# SCH_ReA4091_Rev3_20220620.net
KiCad netlist of a schematic drawn in EasyEDA
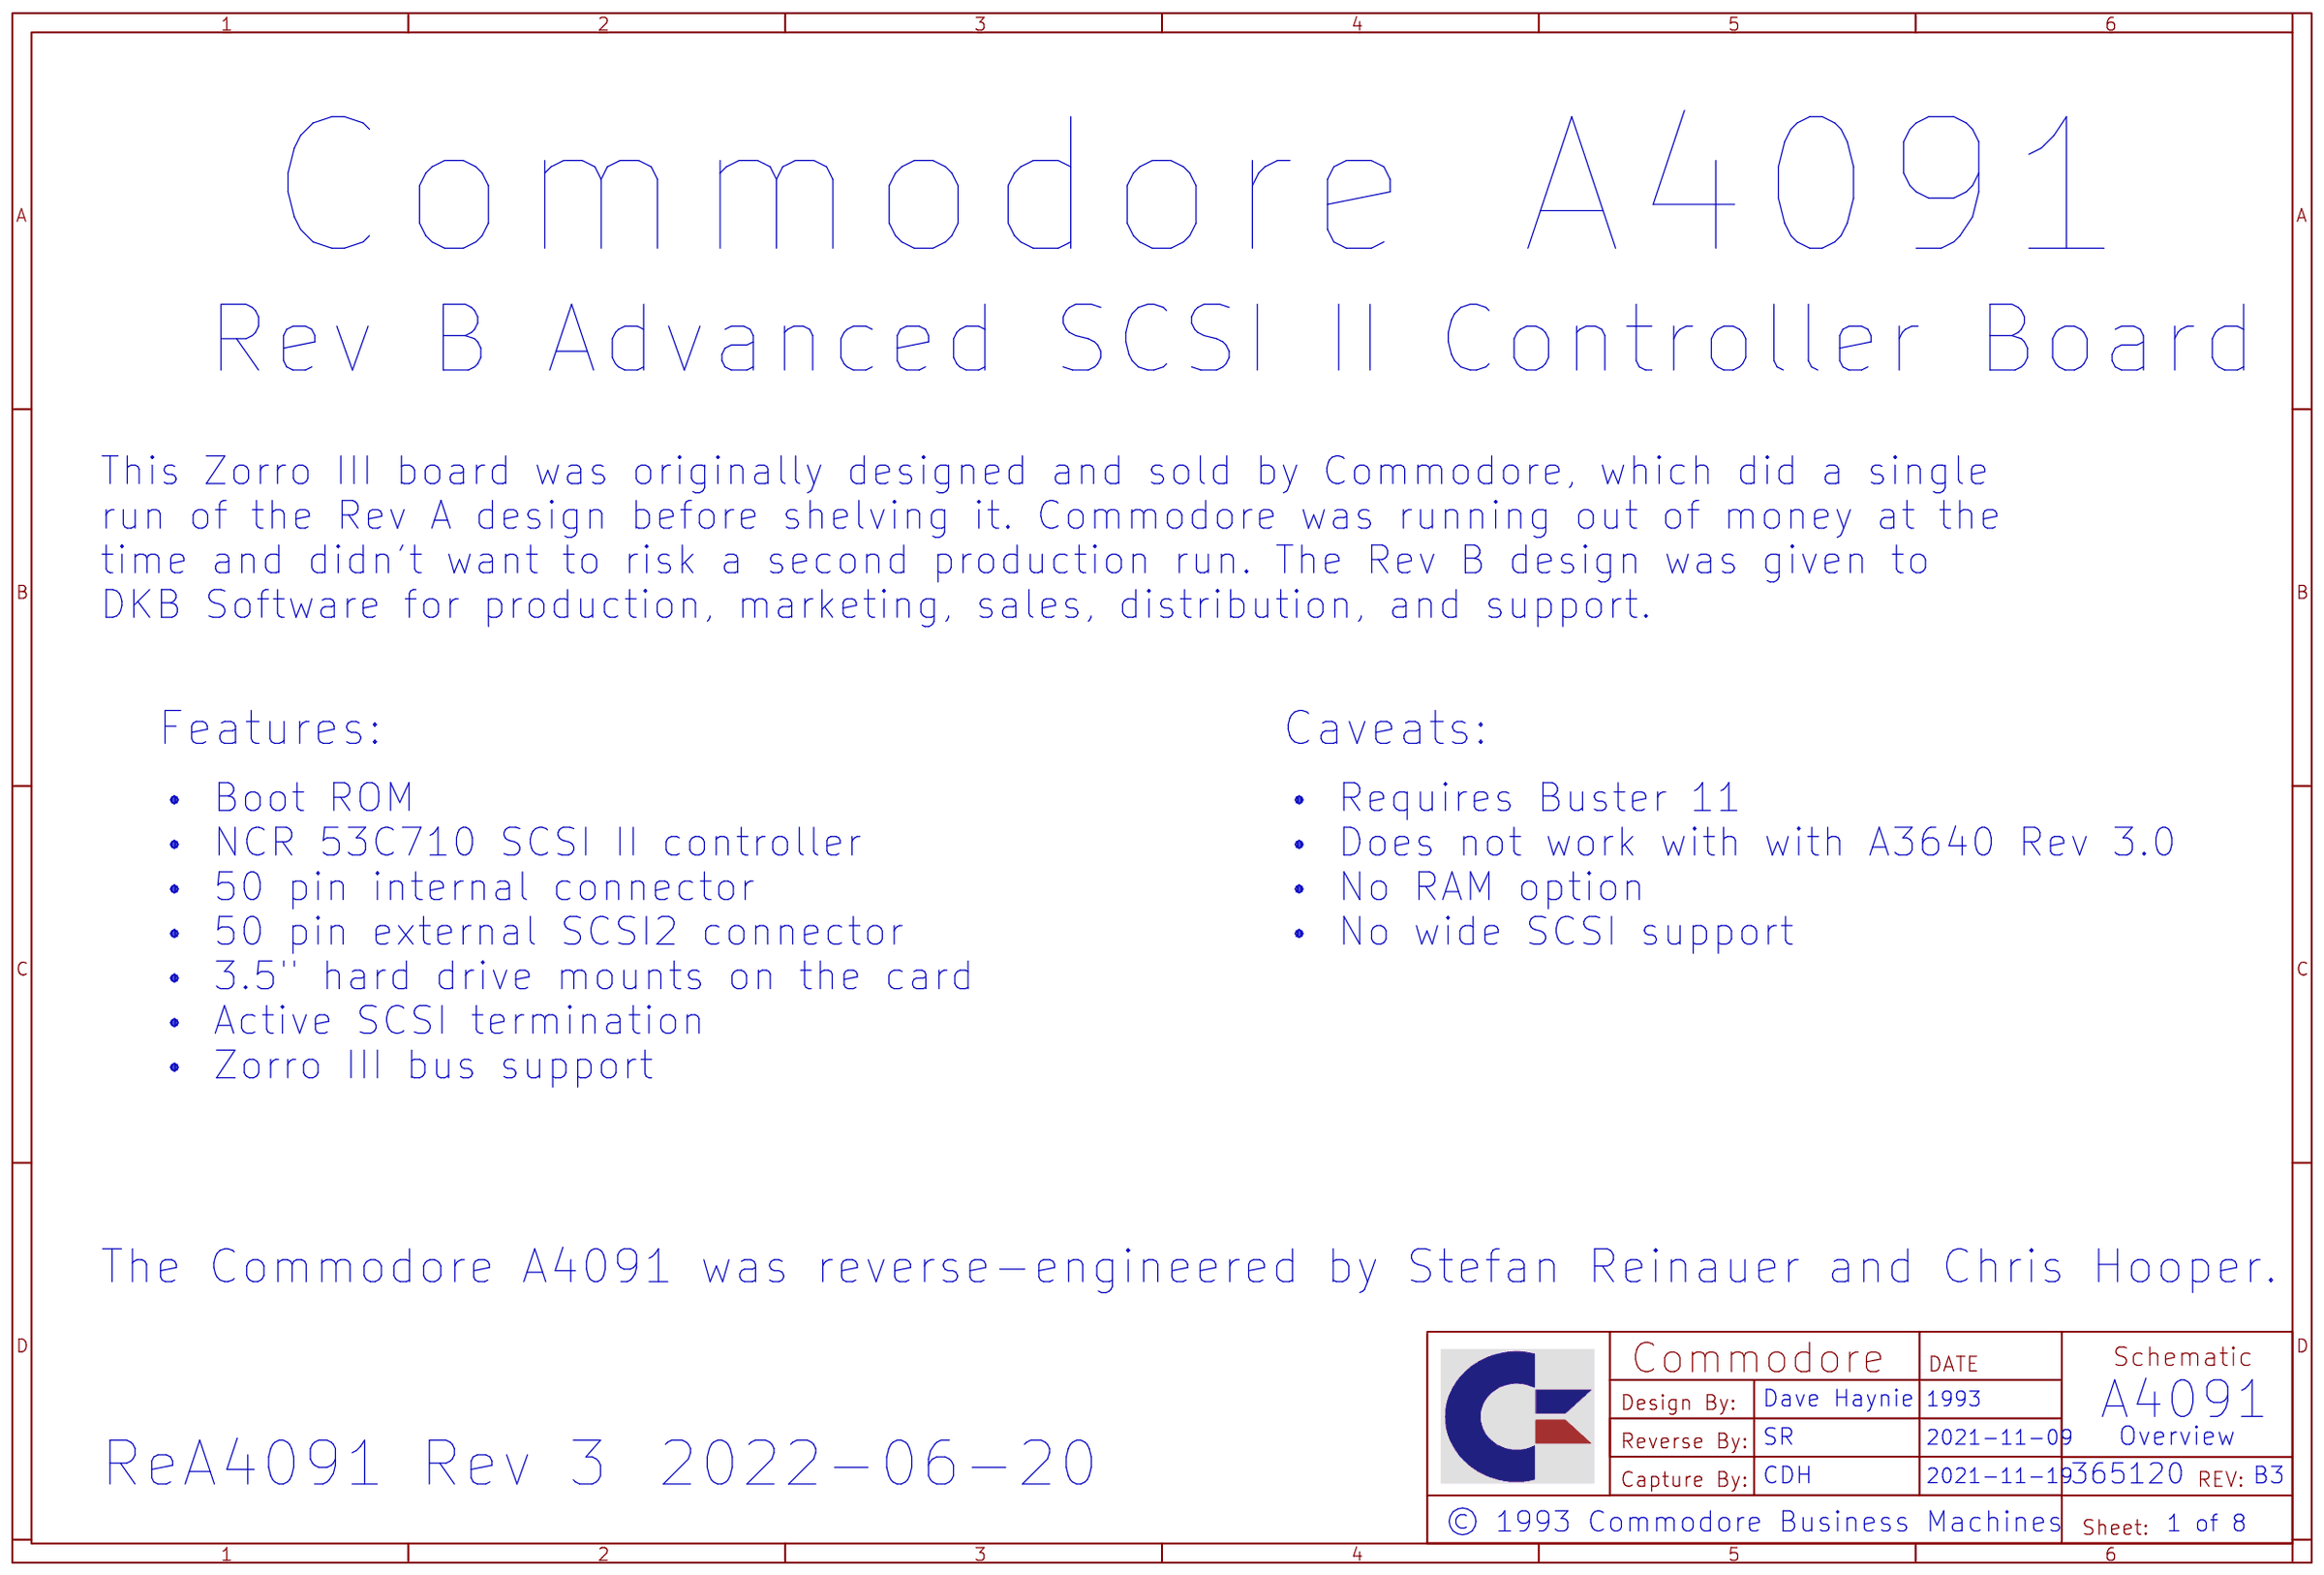
[diagram p0: Overview]
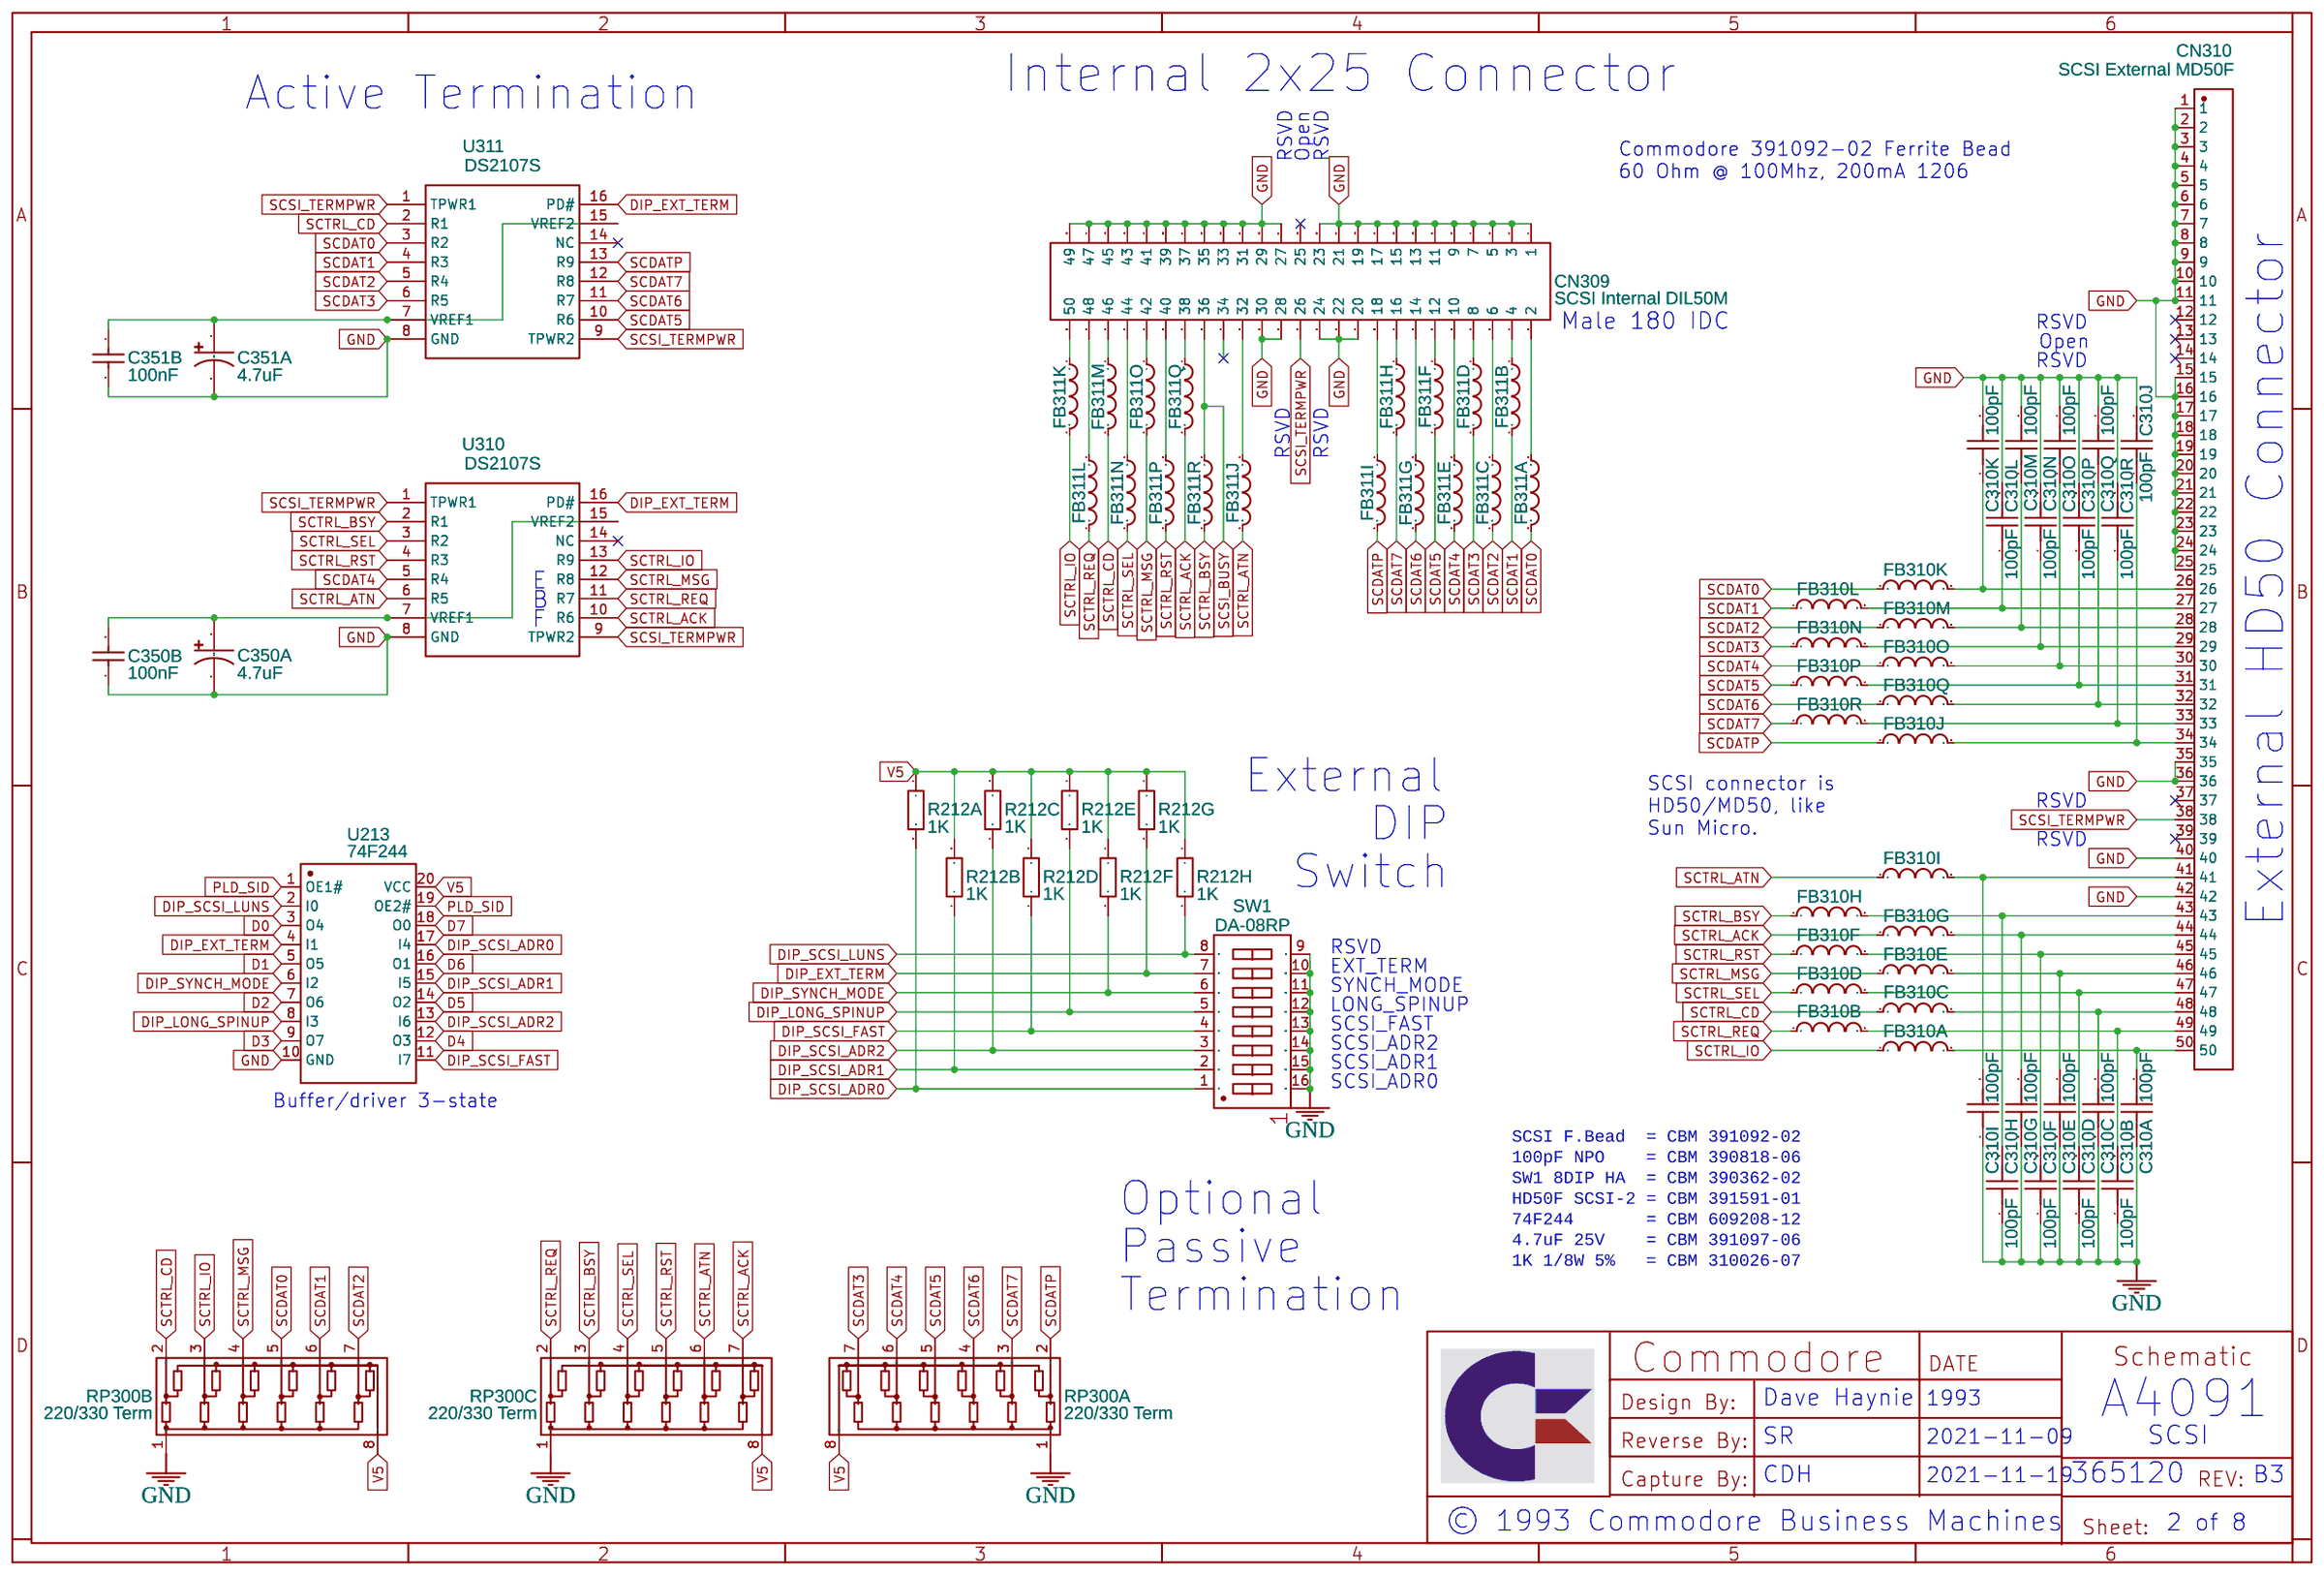
[diagram p1: SCSI]
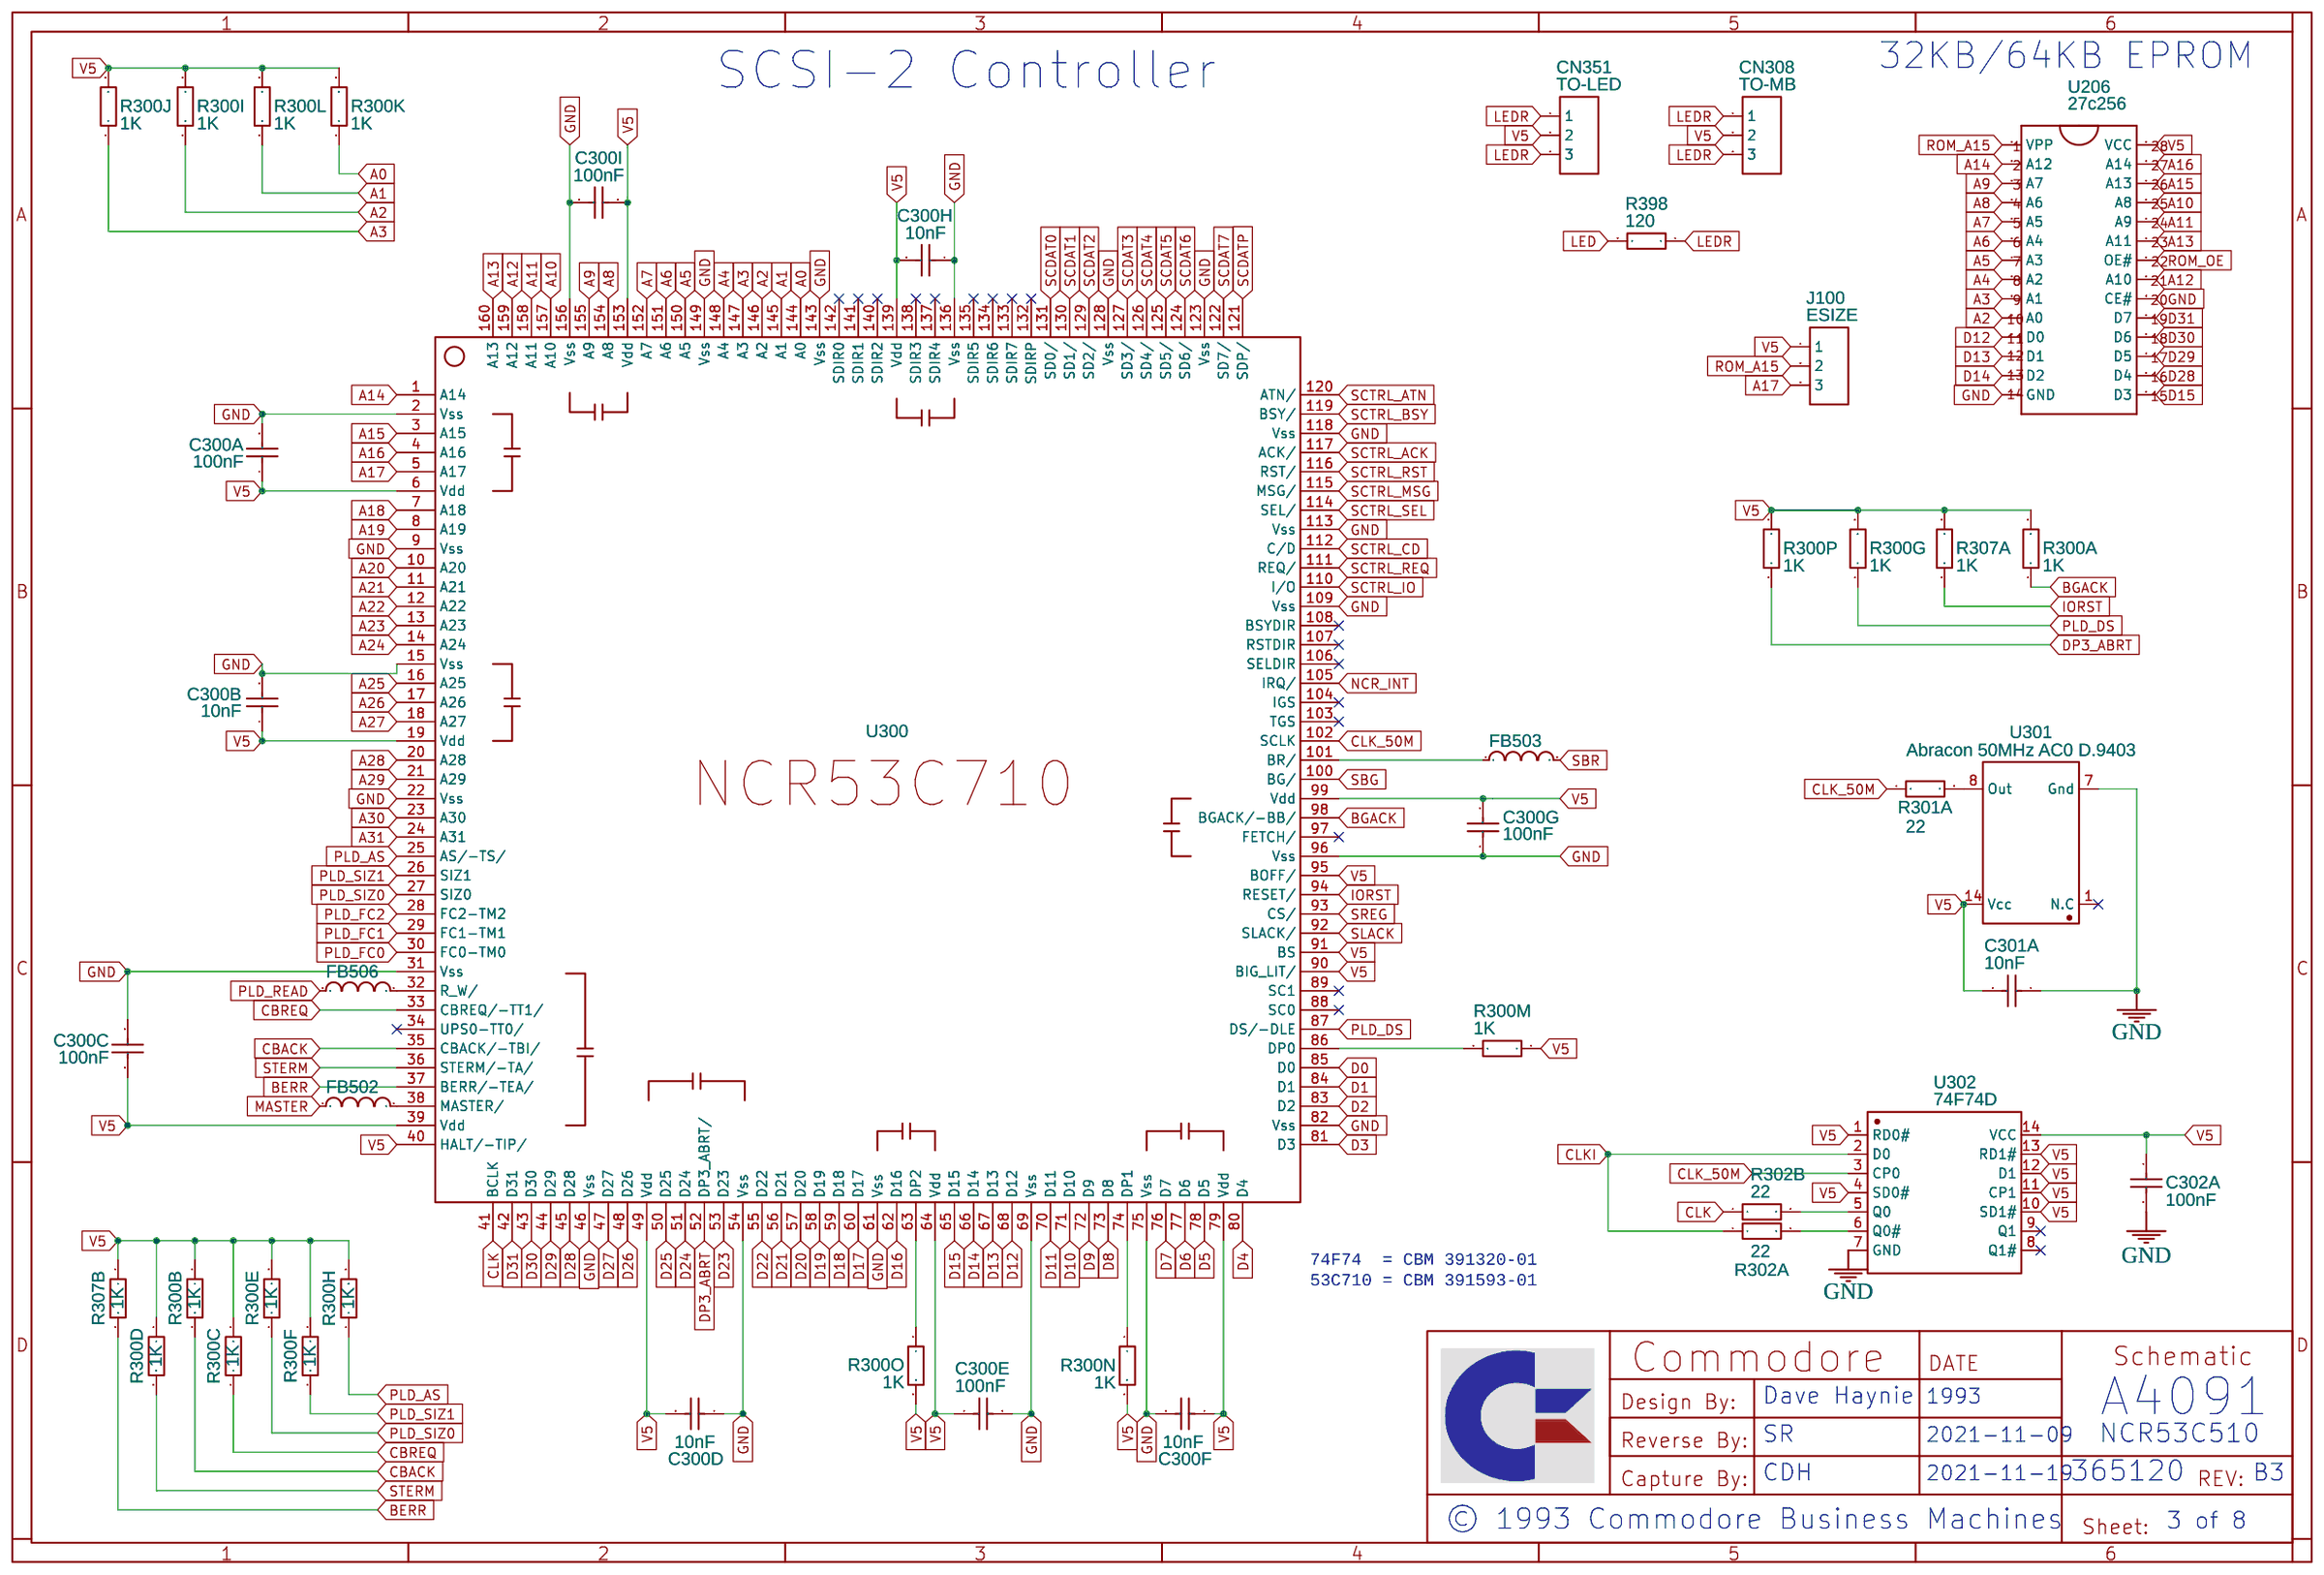
[diagram p2: NCR53C710]
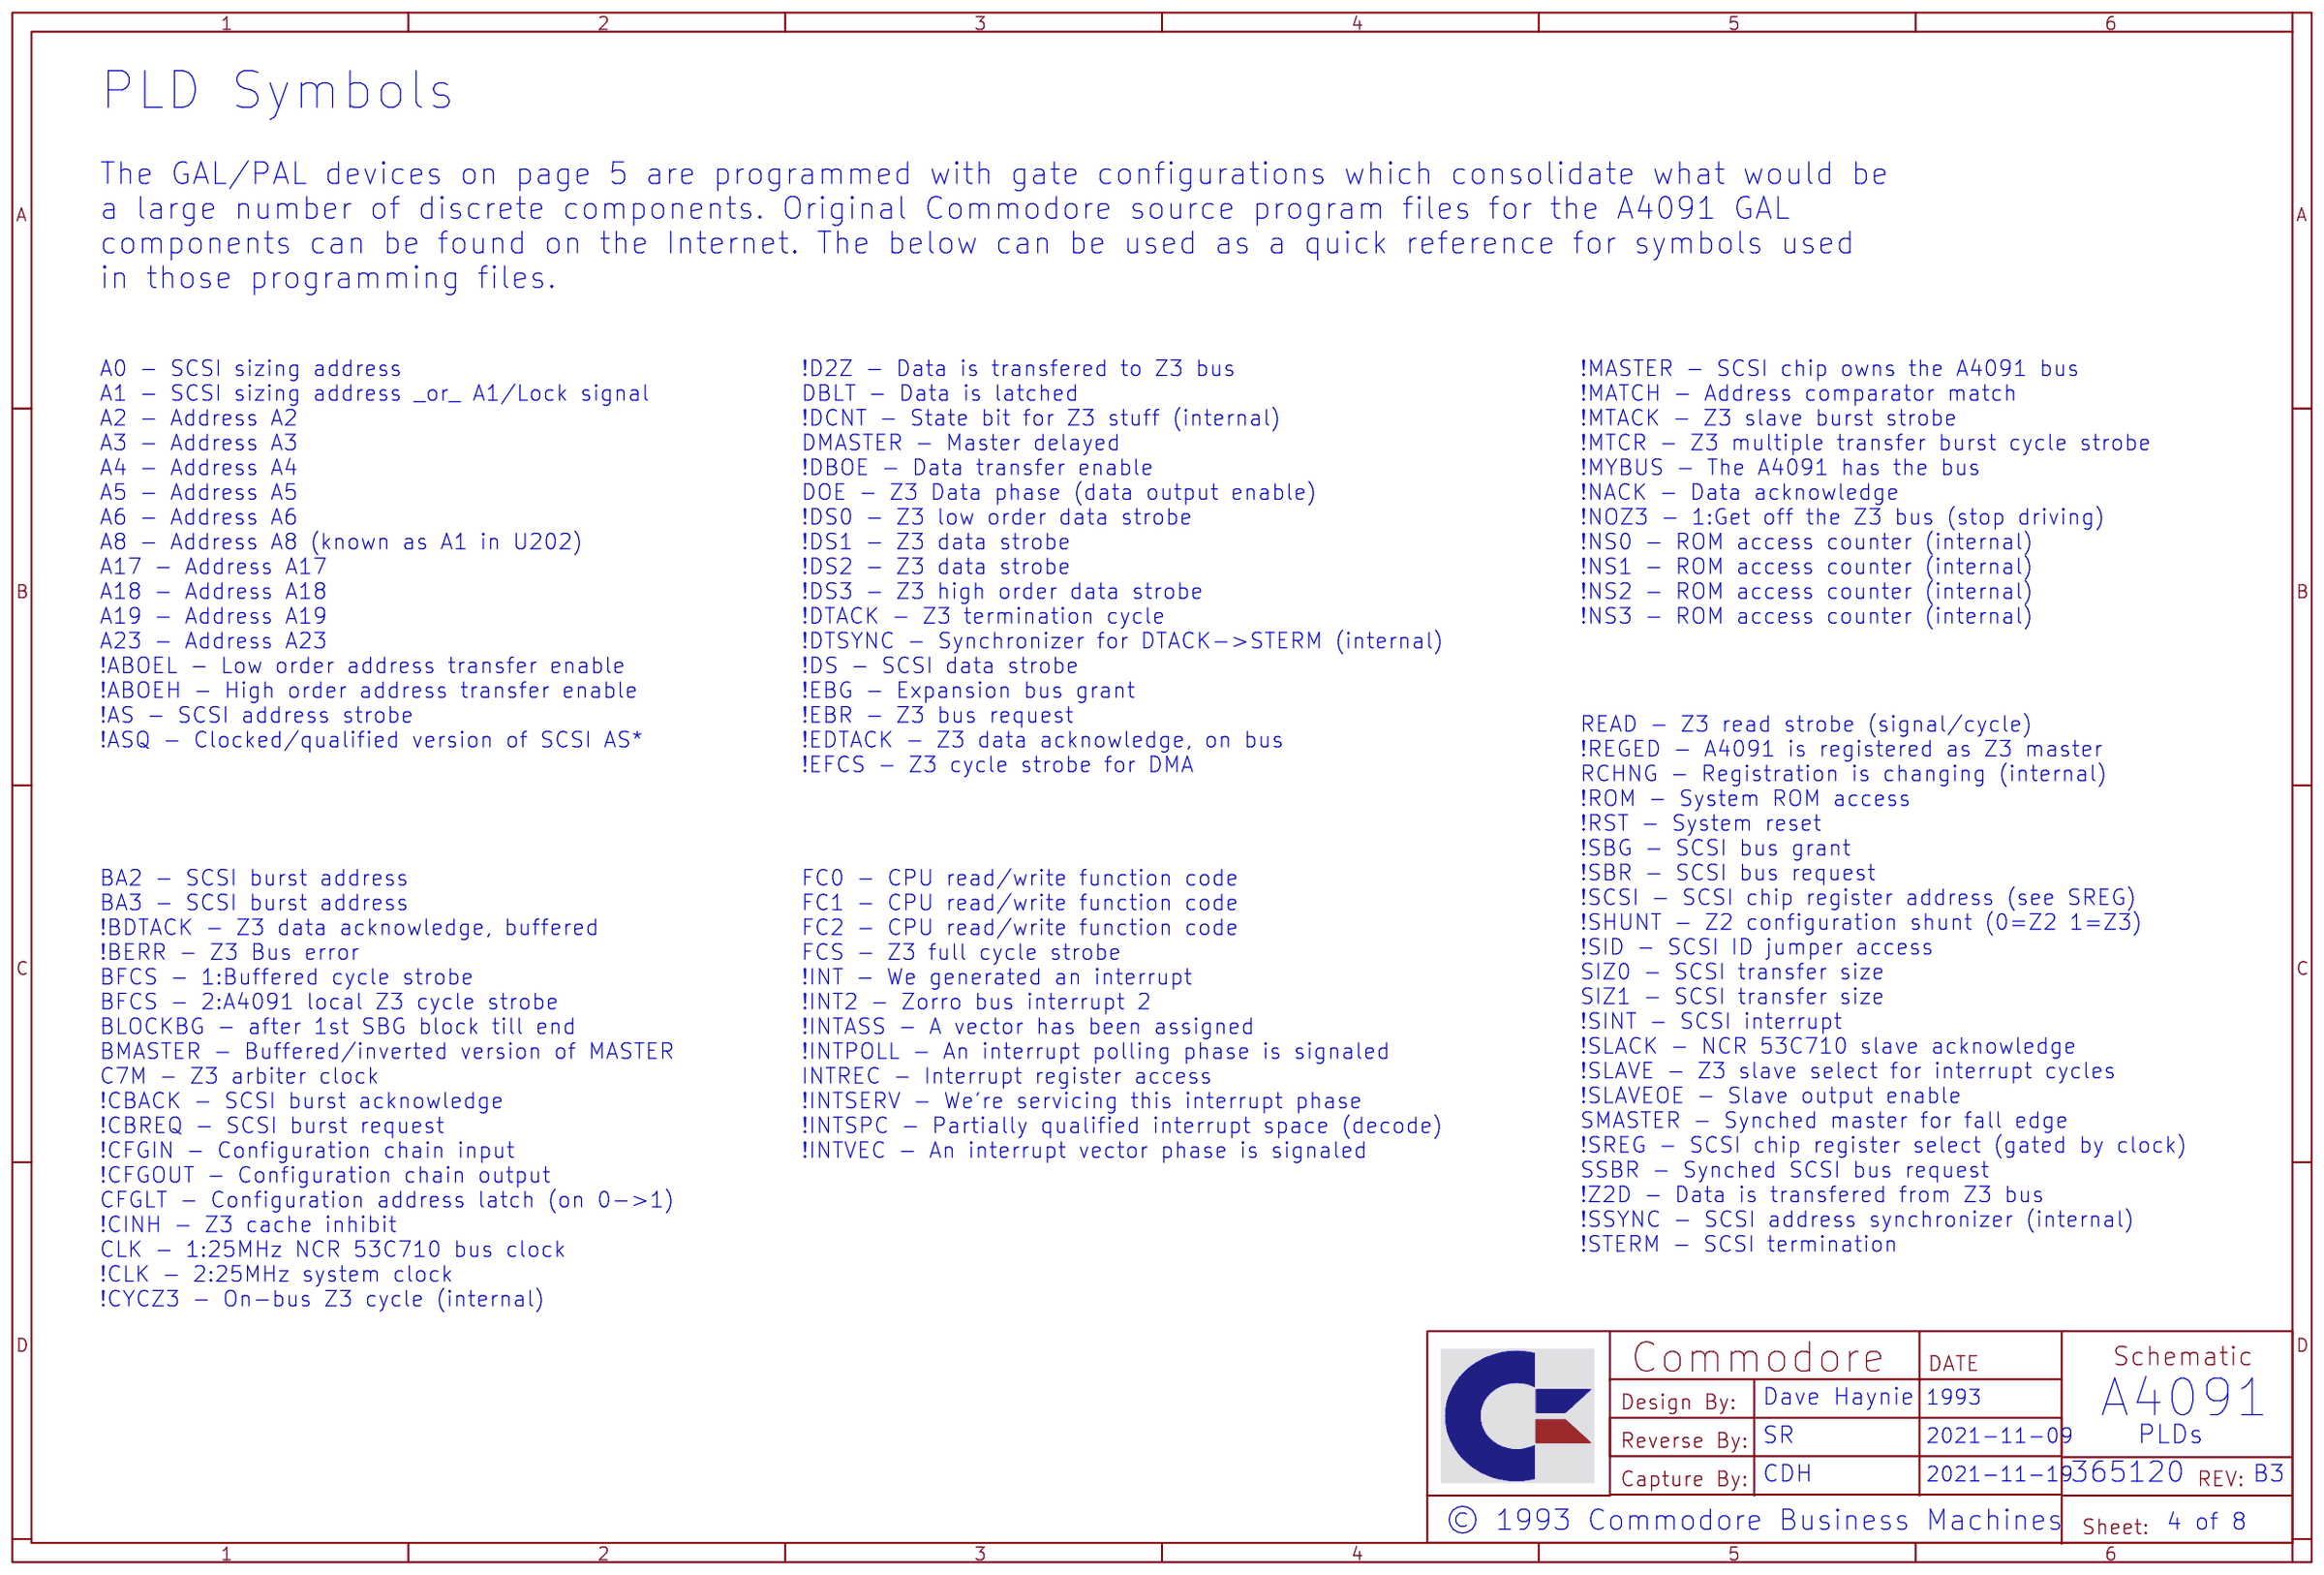
[diagram p3: PLD Symbols]
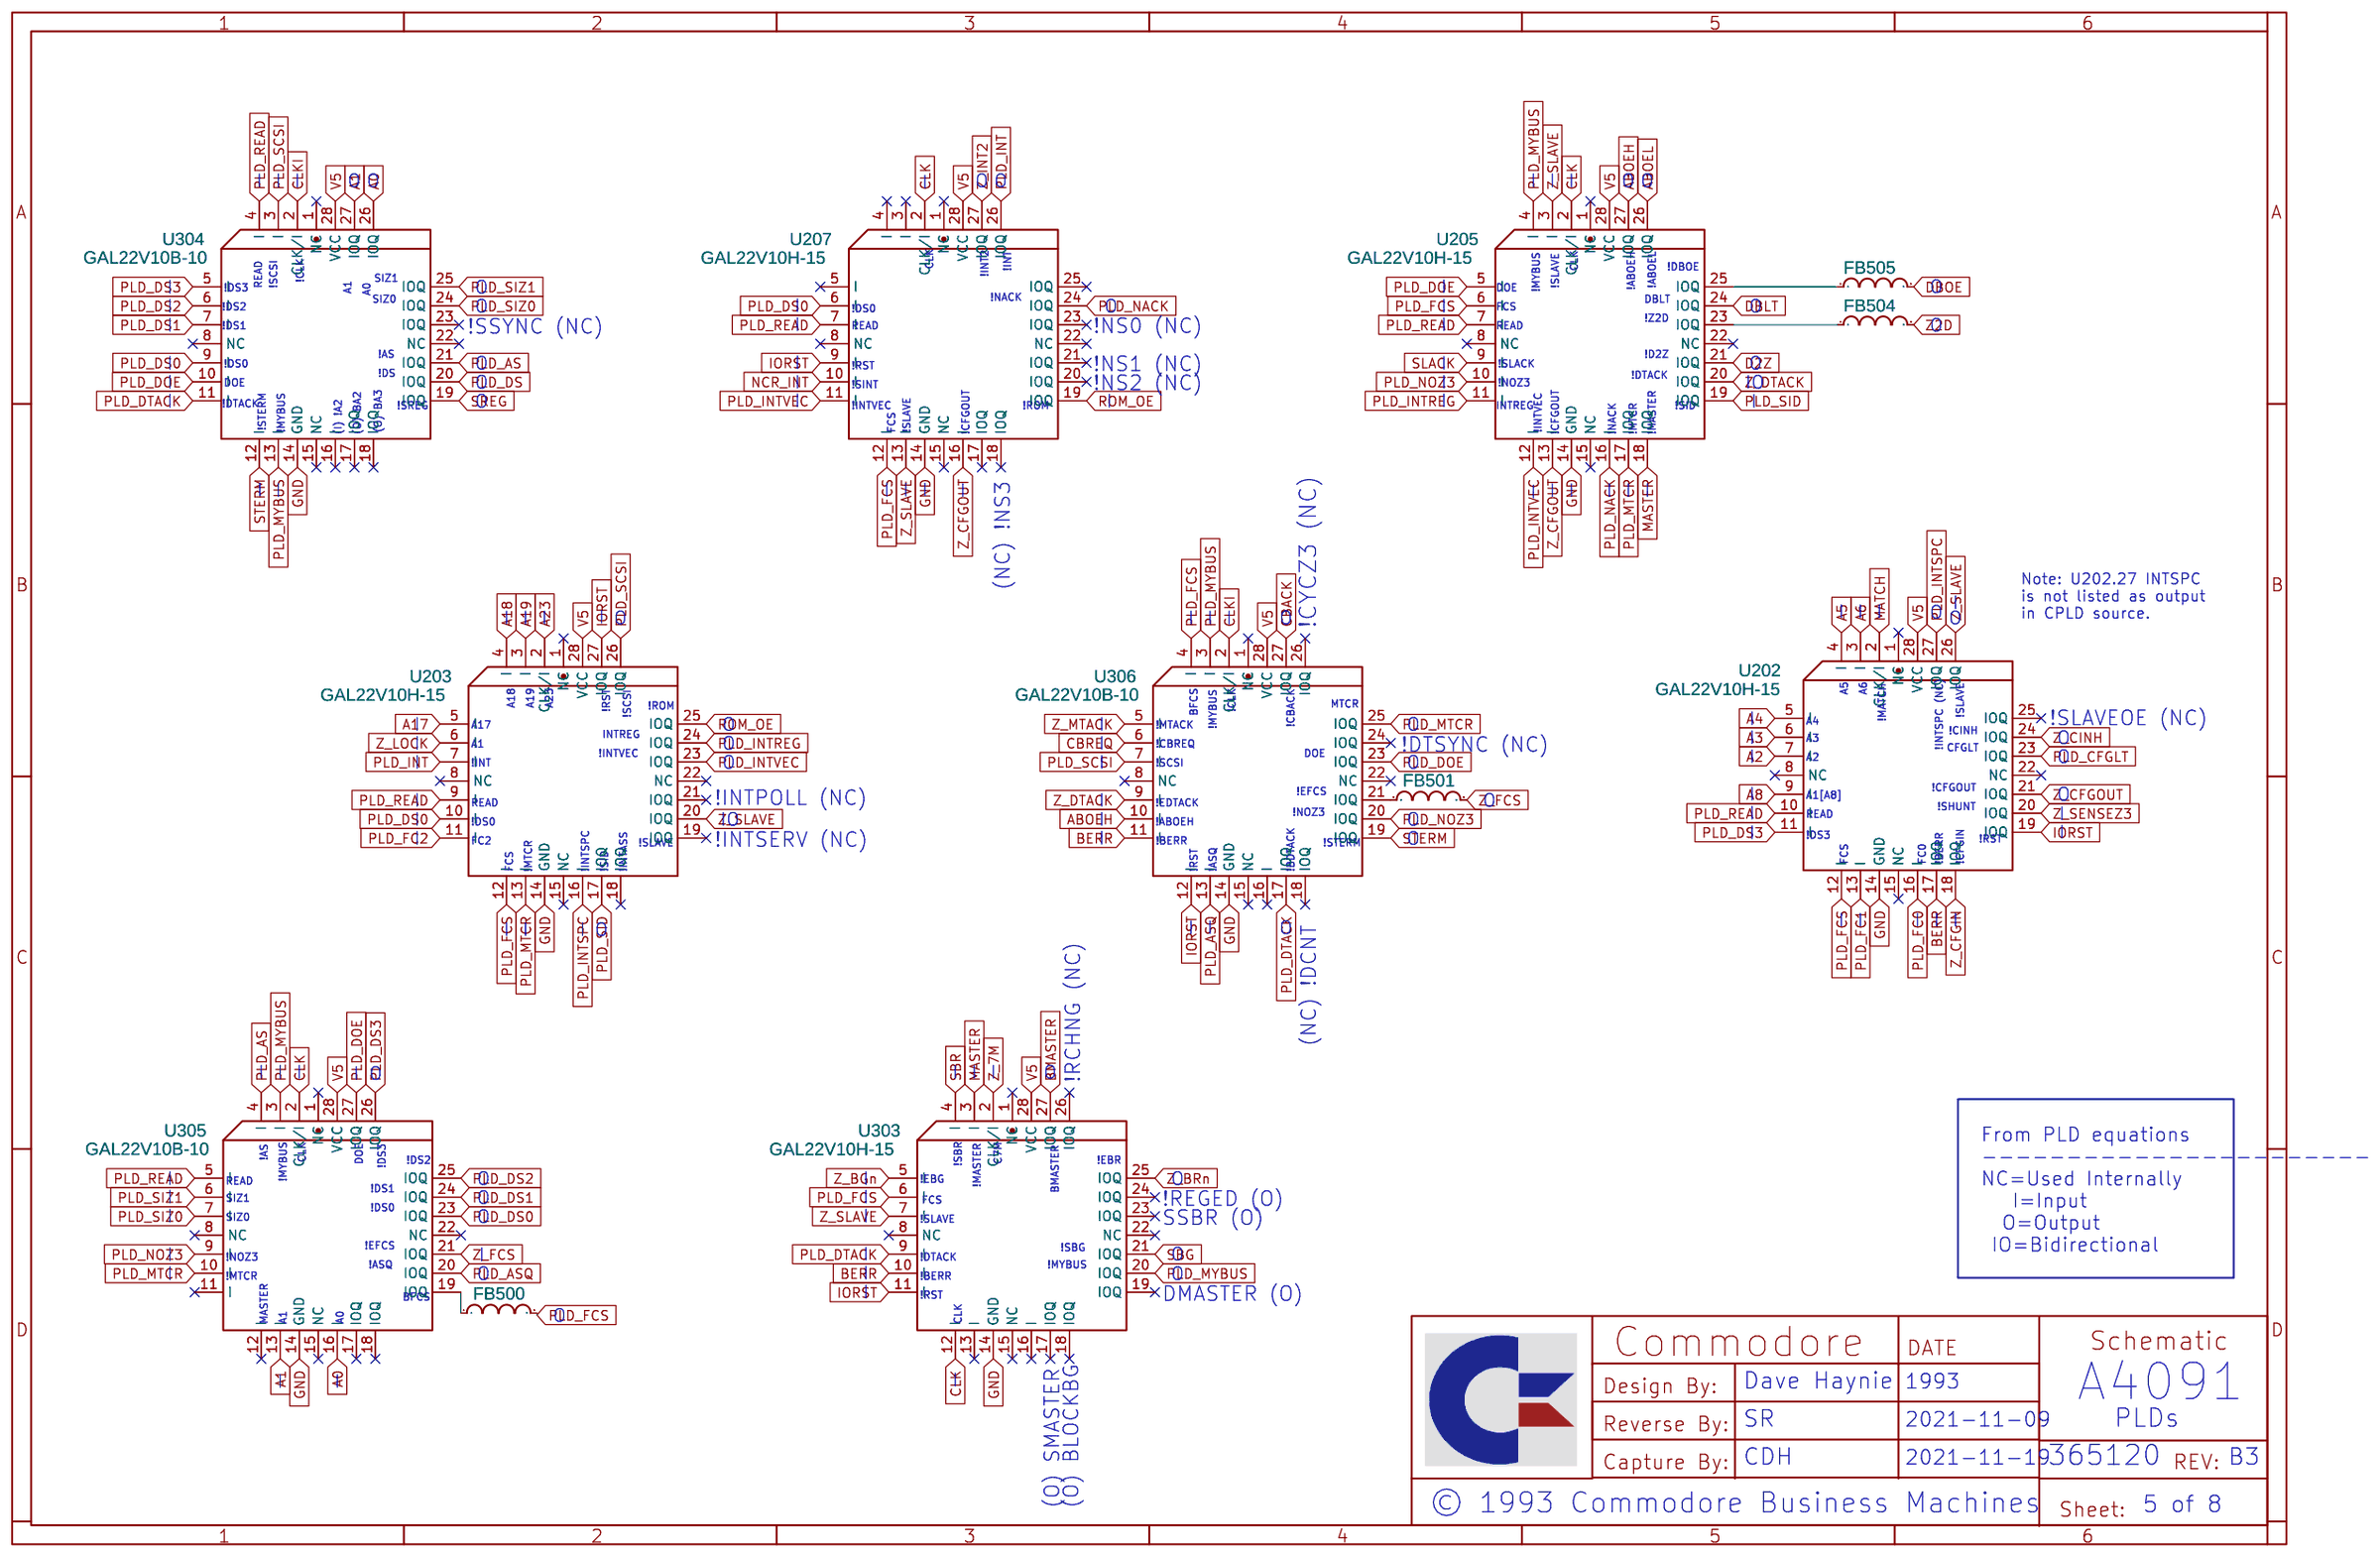
[diagram p4: PLDs]
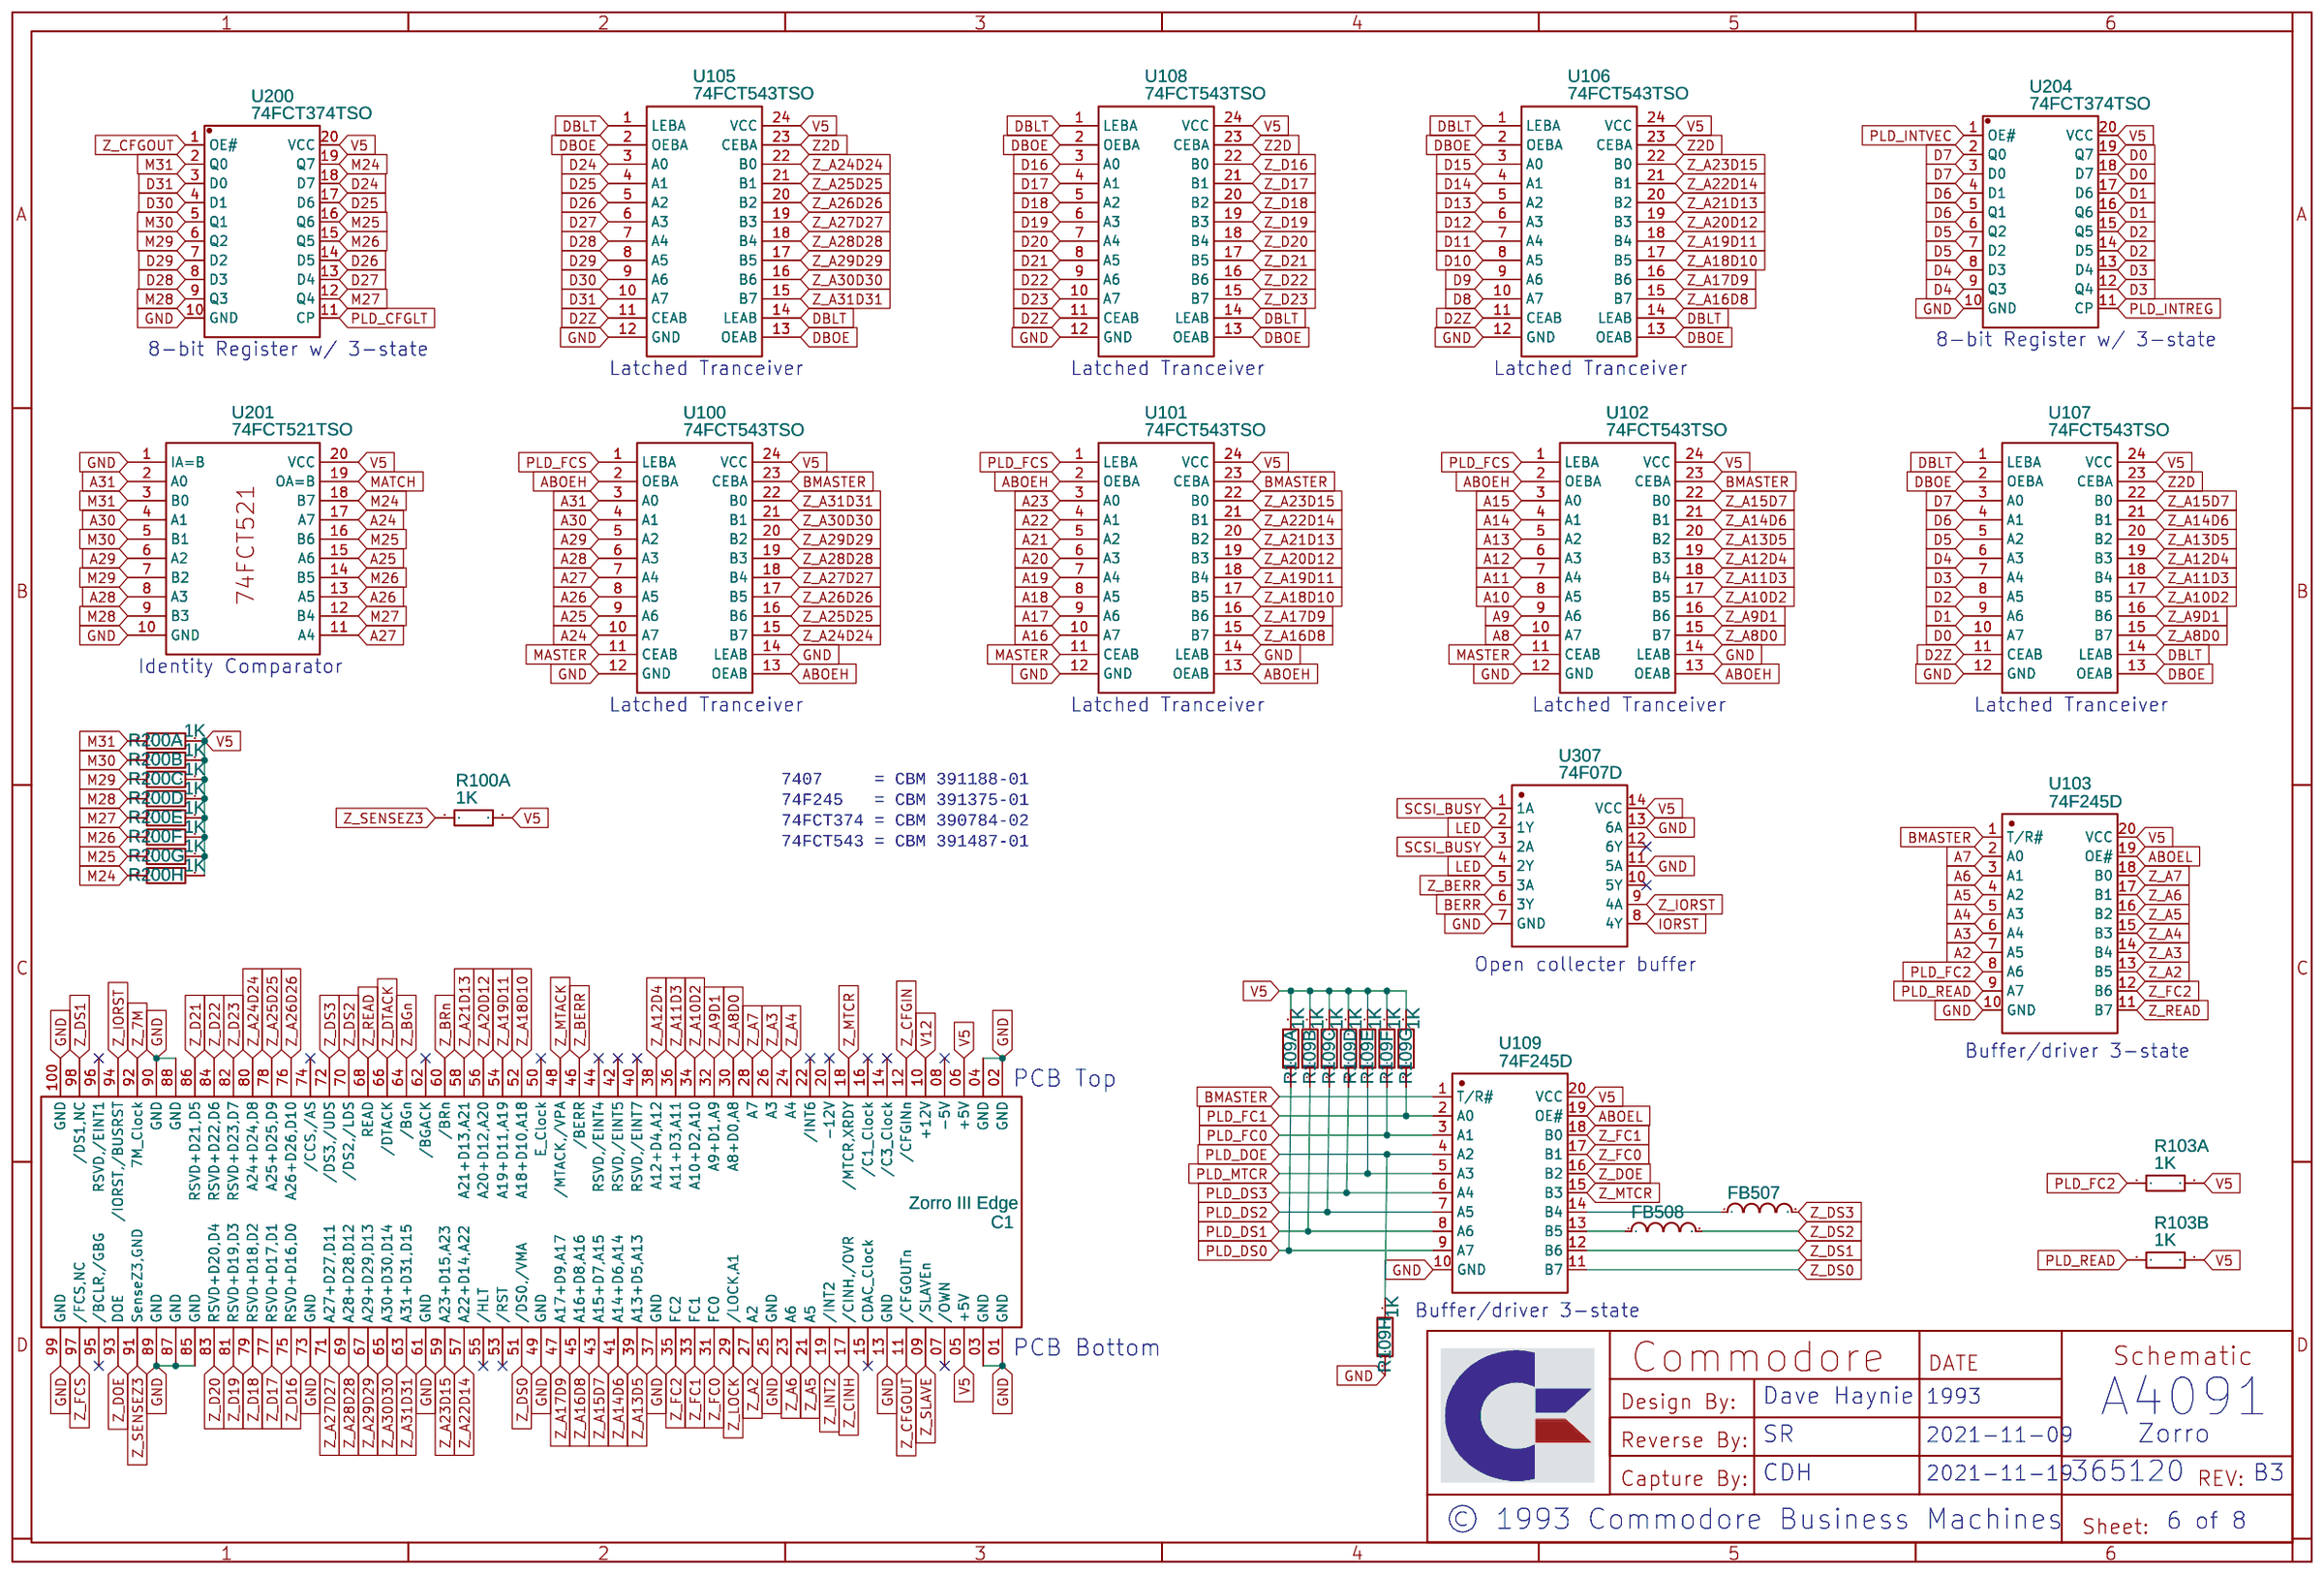
[diagram p5: Zorro]
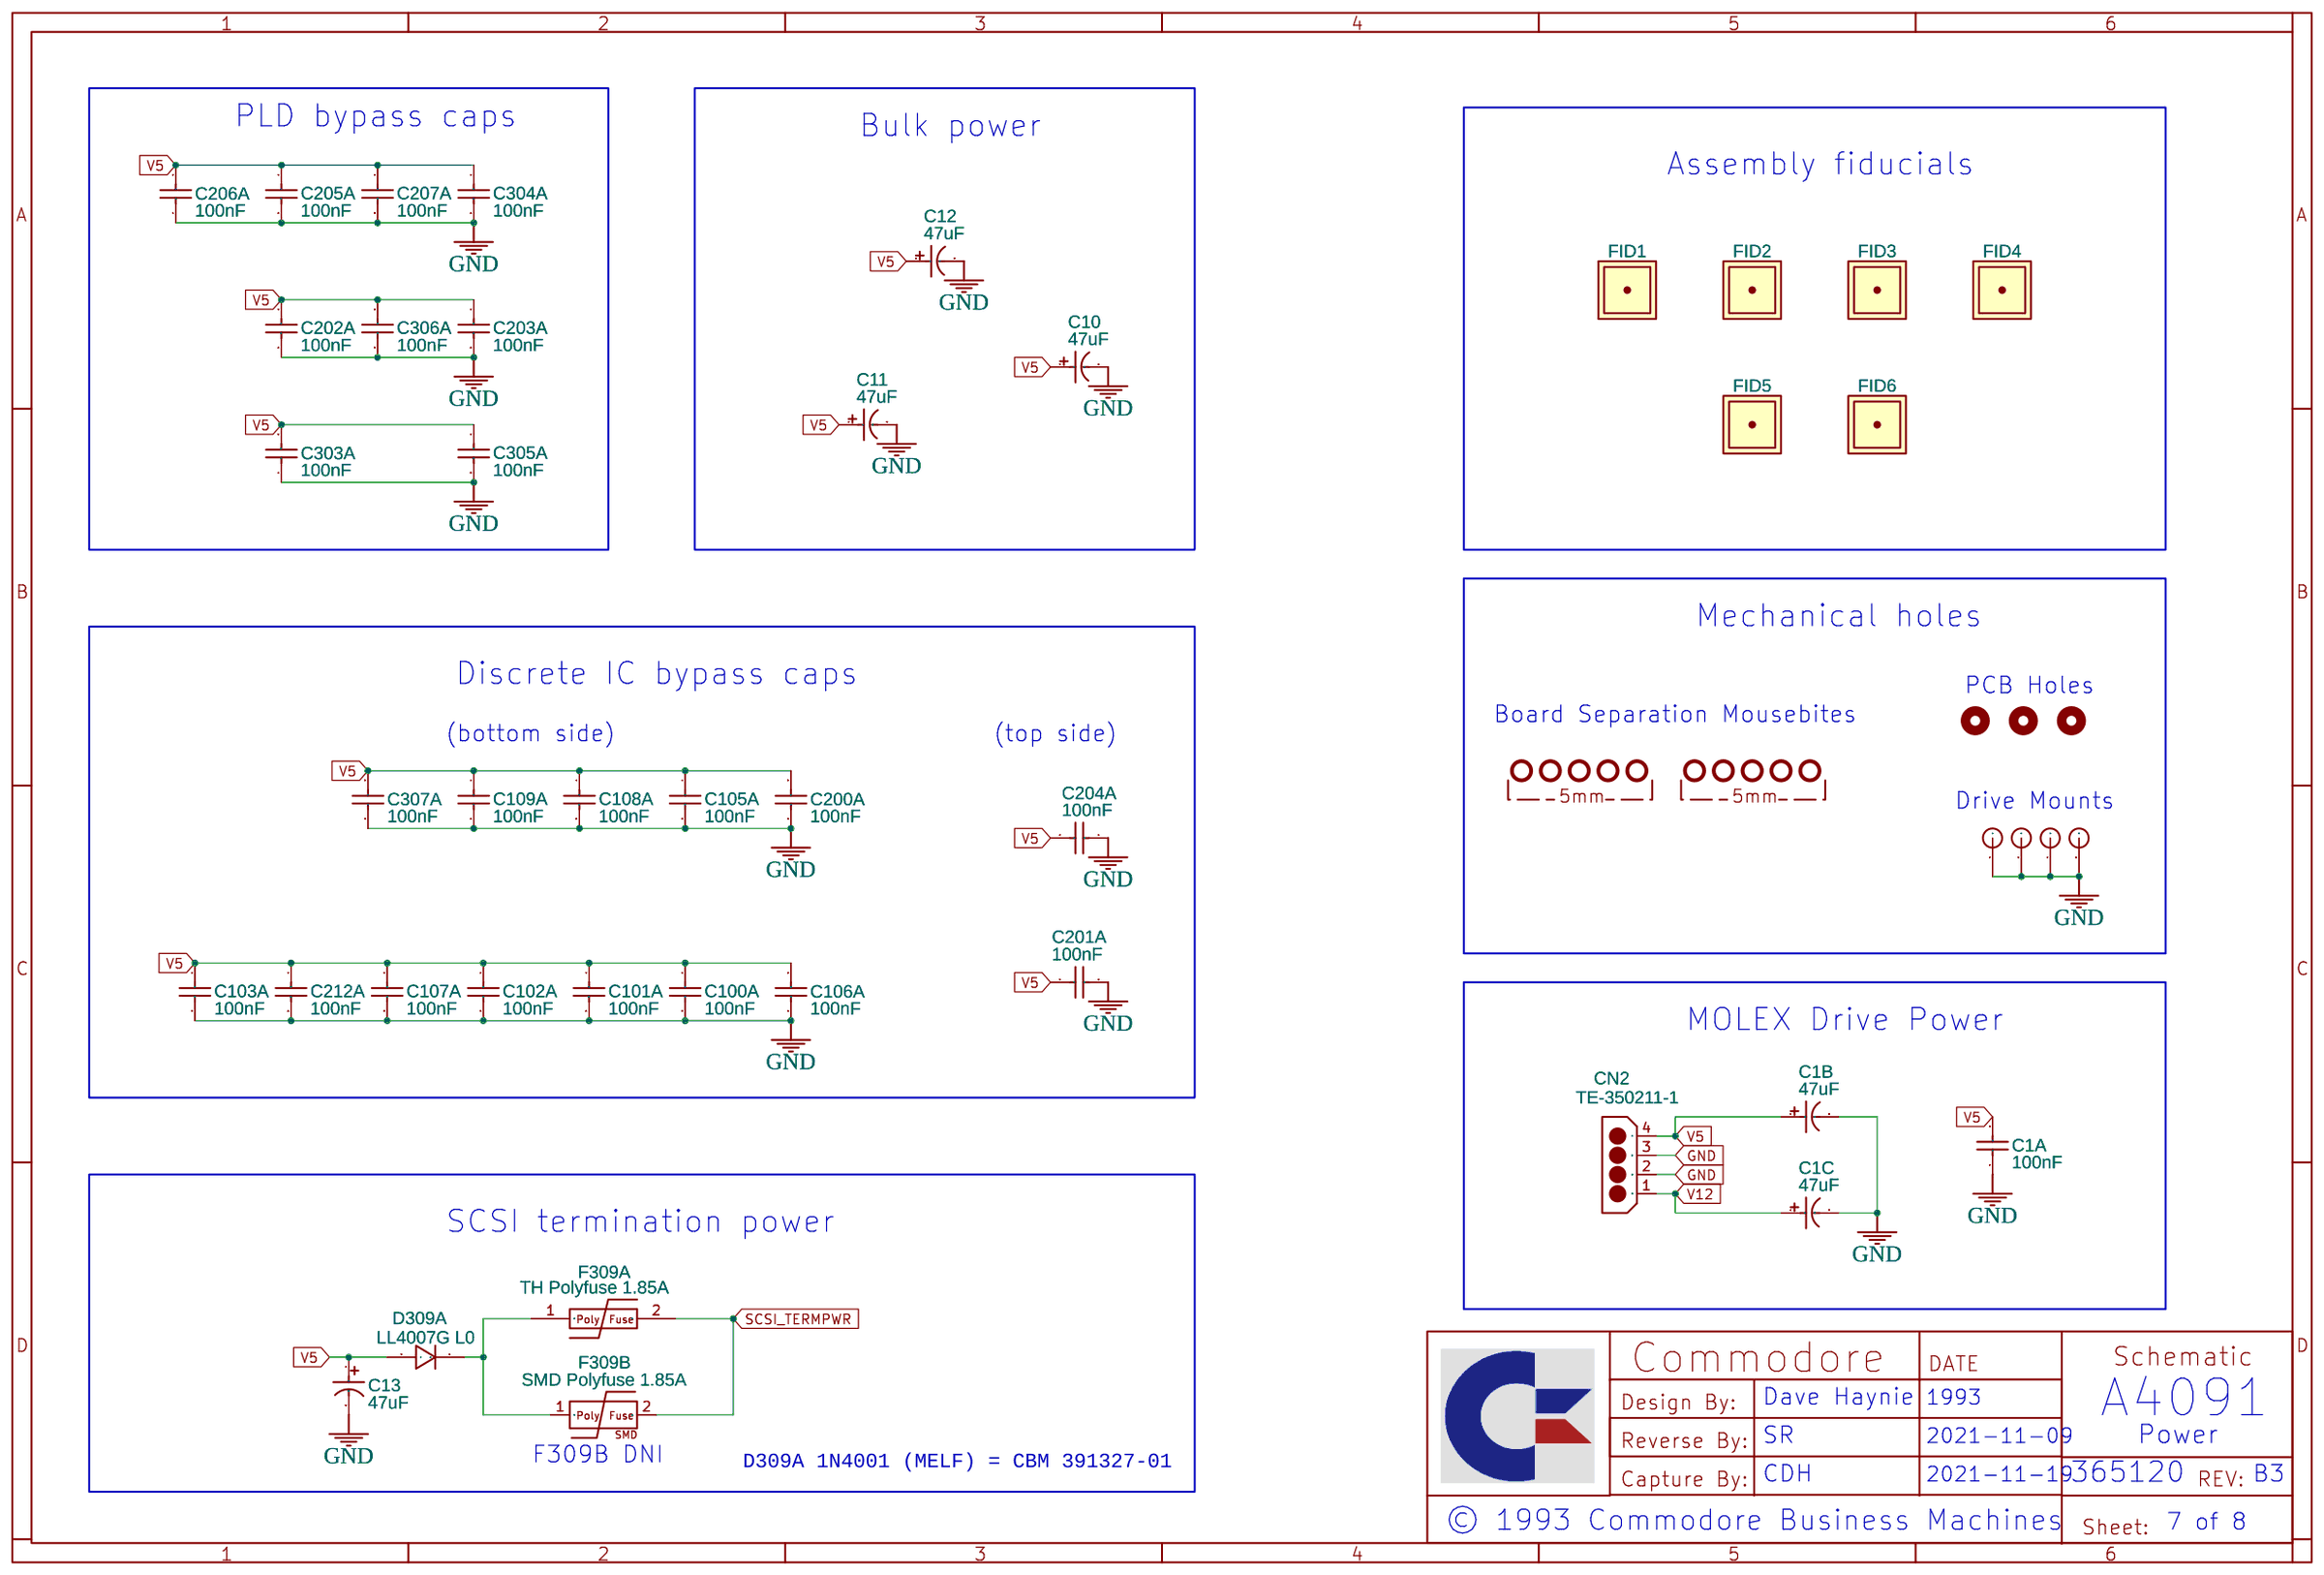
[diagram p6: Power]
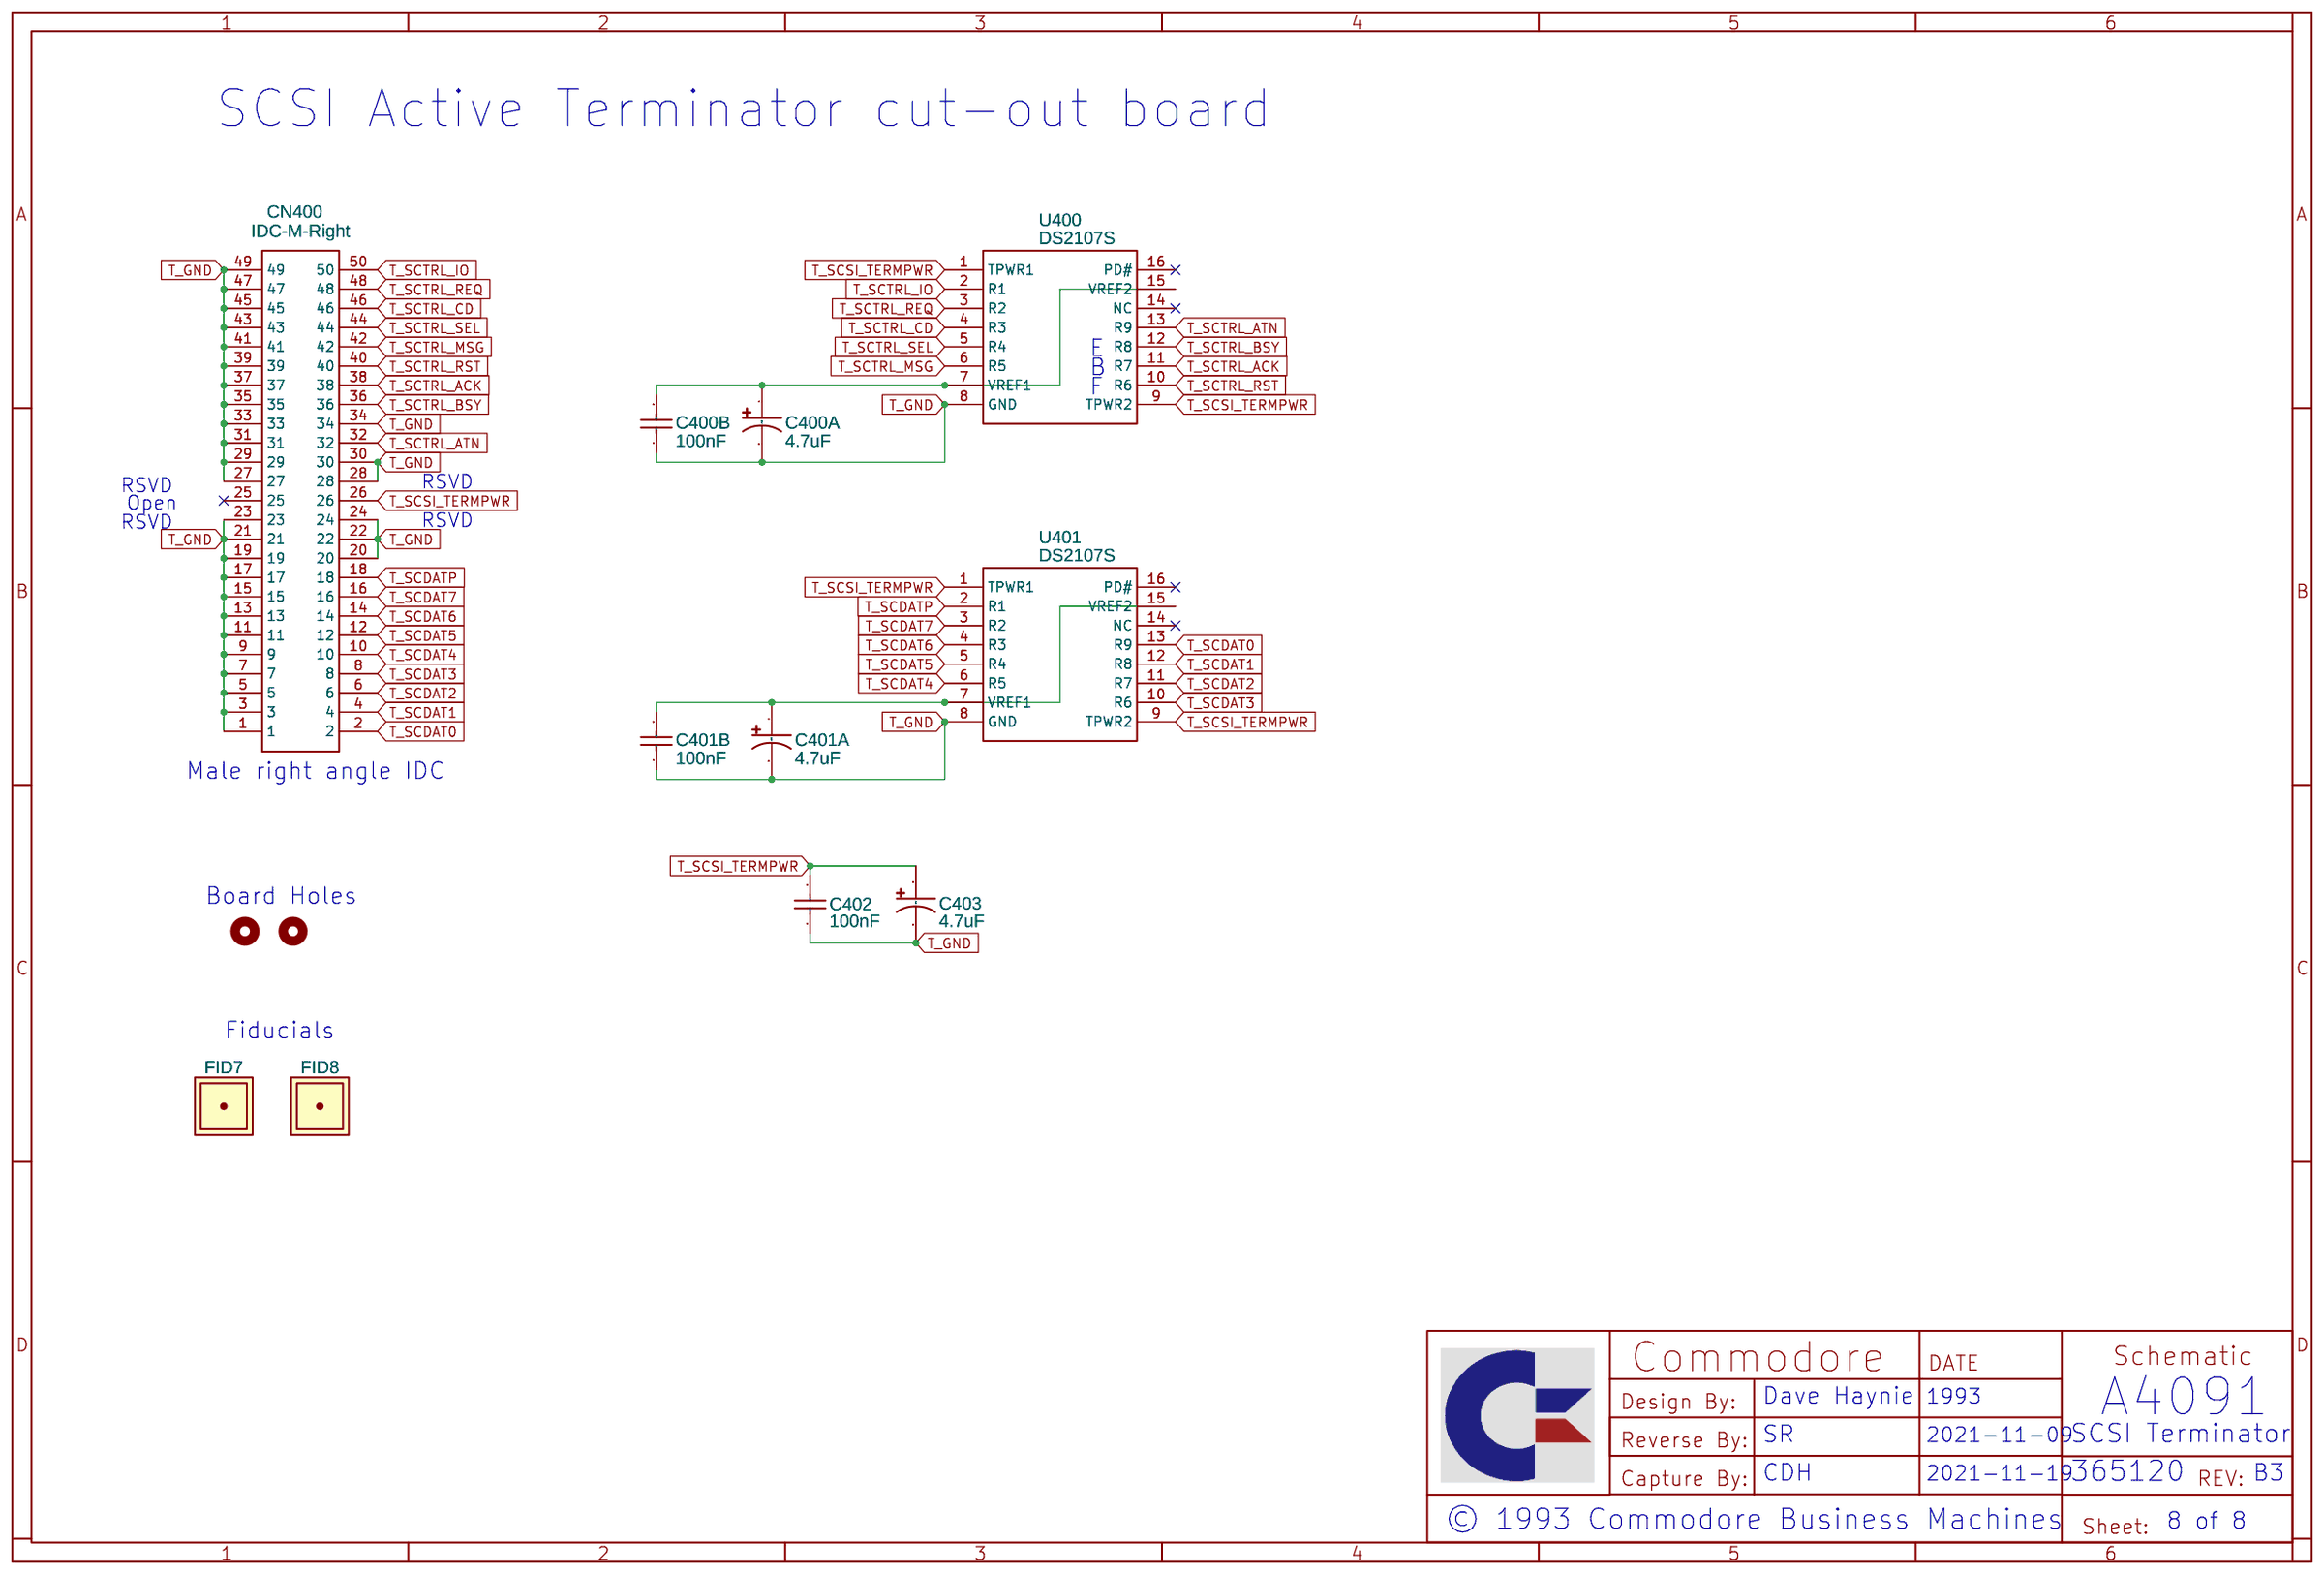
[diagram p7: SCSI Term]

(export (version "E")
  (design (tool "Eeschema 10.0.6"))
  (components
    (comp (ref "C310A")
      (value "100pF")
      (fields
        (field (name "BOM_Manufacturer Part") "CL31C101JHFNNNE")
        (field (name "BOM_Supplier Part") "C307580")
      )
      (libsource (lib "") (part "CL31C101JHFNNNE_2"))
    )
    (comp (ref "C310B")
      (value "100pF")
      (fields
        (field (name "BOM_Manufacturer Part") "CL31C101JHFNNNE")
        (field (name "BOM_Supplier Part") "C307580")
      )
      (libsource (lib "") (part "CL31C101JHFNNNE_14"))
    )
    (comp (ref "C310C")
      (value "100pF")
      (fields
        (field (name "BOM_Manufacturer Part") "CL31C101JHFNNNE")
        (field (name "BOM_Supplier Part") "C307580")
      )
      (libsource (lib "") (part "CL31C101JHFNNNE_6"))
    )
    (comp (ref "C310D")
      (value "100pF")
      (fields
        (field (name "BOM_Manufacturer Part") "CL31C101JHFNNNE")
        (field (name "BOM_Supplier Part") "C307580")
      )
      (libsource (lib "") (part "CL31C101JHFNNNE_7"))
    )
    (comp (ref "C310E")
      (value "100pF")
      (fields
        (field (name "BOM_Manufacturer Part") "CL31C101JHFNNNE")
        (field (name "BOM_Supplier Part") "C307580")
      )
      (libsource (lib "") (part "CL31C101JHFNNNE_11"))
    )
    (comp (ref "C310F")
      (value "100pF")
      (fields
        (field (name "BOM_Manufacturer Part") "CL31C101JHFNNNE")
        (field (name "BOM_Supplier Part") "C307580")
      )
      (libsource (lib "") (part "CL31C101JHFNNNE"))
    )
    (comp (ref "C310G")
      (value "100pF")
      (fields
        (field (name "BOM_Manufacturer Part") "CL31C101JHFNNNE")
        (field (name "BOM_Supplier Part") "C307580")
      )
      (libsource (lib "") (part "CL31C101JHFNNNE_4"))
    )
    (comp (ref "C310H")
      (value "100pF")
      (fields
        (field (name "BOM_Manufacturer Part") "CL31C101JHFNNNE")
        (field (name "BOM_Supplier Part") "C307580")
      )
      (libsource (lib "") (part "CL31C101JHFNNNE_12"))
    )
    (comp (ref "C310I")
      (value "100pF")
      (fields
        (field (name "BOM_Manufacturer Part") "CL31C101JHFNNNE")
        (field (name "BOM_Supplier Part") "C307580")
      )
      (libsource (lib "") (part "CL31C101JHFNNNE_13"))
    )
    (comp (ref "C310J")
      (value "100pF")
      (fields
        (field (name "BOM_Manufacturer Part") "CL31C101JHFNNNE")
        (field (name "BOM_Supplier Part") "C307580")
      )
      (libsource (lib "") (part "CL31C101JHFNNNE_3"))
    )
    (comp (ref "C310K")
      (value "100pF")
      (fields
        (field (name "BOM_Manufacturer Part") "CL31C101JHFNNNE")
        (field (name "BOM_Supplier Part") "C307580")
      )
      (libsource (lib "") (part "CL31C101JHFNNNE_9"))
    )
    (comp (ref "C310L")
      (value "100pF")
      (fields
        (field (name "BOM_Manufacturer Part") "CL31C101JHFNNNE")
        (field (name "BOM_Supplier Part") "C307580")
      )
      (libsource (lib "") (part "CL31C101JHFNNNE_16"))
    )
    (comp (ref "C310M")
      (value "100pF")
      (fields
        (field (name "BOM_Manufacturer Part") "CL31C101JHFNNNE")
        (field (name "BOM_Supplier Part") "C307580")
      )
      (libsource (lib "") (part "CL31C101JHFNNNE_10"))
    )
    (comp (ref "C310N")
      (value "100pF")
      (fields
        (field (name "BOM_Manufacturer Part") "CL31C101JHFNNNE")
        (field (name "BOM_Supplier Part") "C307580")
      )
      (libsource (lib "") (part "CL31C101JHFNNNE_15"))
    )
    (comp (ref "C310O")
      (value "100pF")
      (fields
        (field (name "BOM_Manufacturer Part") "CL31C101JHFNNNE")
        (field (name "BOM_Supplier Part") "C307580")
      )
      (libsource (lib "") (part "CL31C101JHFNNNE_17"))
    )
    (comp (ref "C310P")
      (value "100pF")
      (fields
        (field (name "BOM_Manufacturer Part") "CL31C101JHFNNNE")
        (field (name "BOM_Supplier Part") "C307580")
      )
      (libsource (lib "") (part "CL31C101JHFNNNE_5"))
    )
    (comp (ref "C310Q")
      (value "100pF")
      (fields
        (field (name "BOM_Manufacturer Part") "CL31C101JHFNNNE")
        (field (name "BOM_Supplier Part") "C307580")
      )
      (libsource (lib "") (part "CL31C101JHFNNNE_8"))
    )
    (comp (ref "C310R")
      (value "100pF")
      (fields
        (field (name "BOM_Manufacturer Part") "CL31C101JHFNNNE")
        (field (name "BOM_Supplier Part") "C307580")
      )
      (libsource (lib "") (part "CL31C101JHFNNNE_1"))
    )
    (comp (ref "C350A")
      (value "4.7uF")
      (fields
        (field (name "BOM_Manufacturer Part") "VZH4R7M1HTR-0406")
        (field (name "BOM_Supplier Part") "C164079")
      )
      (libsource (lib "") (part "VZH4R7M1HTR-0406_1"))
    )
    (comp (ref "C350B")
      (value "100nF")
      (fields
        (field (name "BOM_Manufacturer Part") "CL31B104KBCNNNC")
        (field (name "BOM_Supplier Part") "C24497")
      )
      (libsource (lib "") (part "CL31B104KBCNNNC_1"))
    )
    (comp (ref "C351A")
      (value "4.7uF")
      (fields
        (field (name "BOM_Manufacturer Part") "VZH4R7M1HTR-0406")
        (field (name "BOM_Supplier Part") "C164079")
      )
      (libsource (lib "") (part "VZH4R7M1HTR-0406"))
    )
    (comp (ref "C351B")
      (value "100nF")
      (fields
        (field (name "BOM_Manufacturer Part") "CL31B104KBCNNNC")
        (field (name "BOM_Supplier Part") "C24497")
      )
      (libsource (lib "") (part "CL31B104KBCNNNC"))
    )
    (comp (ref "CN309")
      (value "SCSI Internal DIL50M")
      (fields
        (field (name "BOM_Manufacturer Part") "Header-Male-2.54_2x20")
        (field (name "BOM_Supplier Part") "C50980")
      )
      (libsource (lib "") (part "HEADER-MALE-2.54_2X25"))
    )
    (comp (ref "CN310") (value "SCSI External MD50F") (libsource (lib "") (part "MD50R")))
    (comp (ref "FB310A")
      (value "60Ω")
      (fields
        (field (name "BOM_Manufacturer Part") "CBG321609U600T")
        (field (name "BOM_Supplier Part") "C1020")
      )
      (libsource (lib "") (part "MLB3216-601(f)_11"))
    )
    (comp (ref "FB310B")
      (value "60Ω")
      (fields
        (field (name "BOM_Manufacturer Part") "CBG321609U600T")
        (field (name "BOM_Supplier Part") "C1020")
      )
      (libsource (lib "") (part "MLB3216-601(f)_7"))
    )
    (comp (ref "FB310C")
      (value "60Ω")
      (fields
        (field (name "BOM_Manufacturer Part") "CBG321609U600T")
        (field (name "BOM_Supplier Part") "C1020")
      )
      (libsource (lib "") (part "MLB3216-601(f)_29"))
    )
    (comp (ref "FB310D")
      (value "60Ω")
      (fields
        (field (name "BOM_Manufacturer Part") "CBG321609U600T")
        (field (name "BOM_Supplier Part") "C1020")
      )
      (libsource (lib "") (part "MLB3216-601(f)_9"))
    )
    (comp (ref "FB310E")
      (value "60Ω")
      (fields
        (field (name "BOM_Manufacturer Part") "CBG321609U600T")
        (field (name "BOM_Supplier Part") "C1020")
      )
      (libsource (lib "") (part "MLB3216-601(f)_17"))
    )
    (comp (ref "FB310F")
      (value "60Ω")
      (fields
        (field (name "BOM_Manufacturer Part") "CBG321609U600T")
        (field (name "BOM_Supplier Part") "C1020")
      )
      (libsource (lib "") (part "MLB3216-601(f)_25"))
    )
    (comp (ref "FB310G")
      (value "60Ω")
      (fields
        (field (name "BOM_Manufacturer Part") "CBG321609U600T")
        (field (name "BOM_Supplier Part") "C1020")
      )
      (libsource (lib "") (part "MLB3216-601(f)_22"))
    )
    (comp (ref "FB310H")
      (value "60Ω")
      (fields
        (field (name "BOM_Manufacturer Part") "CBG321609U600T")
        (field (name "BOM_Supplier Part") "C1020")
      )
      (libsource (lib "") (part "MLB3216-601(f)_5"))
    )
    (comp (ref "FB310I")
      (value "60Ω")
      (fields
        (field (name "BOM_Manufacturer Part") "CBG321609U600T")
        (field (name "BOM_Supplier Part") "C1020")
      )
      (libsource (lib "") (part "MLB3216-601(f)_34"))
    )
    (comp (ref "FB310J")
      (value "60Ω")
      (fields
        (field (name "BOM_Manufacturer Part") "CBG321609U600T")
        (field (name "BOM_Supplier Part") "C1020")
      )
      (libsource (lib "") (part "MLB3216-601(f)_15"))
    )
    (comp (ref "FB310K")
      (value "60Ω")
      (fields
        (field (name "BOM_Manufacturer Part") "CBG321609U600T")
        (field (name "BOM_Supplier Part") "C1020")
      )
      (libsource (lib "") (part "MLB3216-601(f)_27"))
    )
    (comp (ref "FB310L")
      (value "60Ω")
      (fields
        (field (name "BOM_Manufacturer Part") "CBG321609U600T")
        (field (name "BOM_Supplier Part") "C1020")
      )
      (libsource (lib "") (part "MLB3216-601(f)_31"))
    )
    (comp (ref "FB310M")
      (value "60Ω")
      (fields
        (field (name "BOM_Manufacturer Part") "CBG321609U600T")
        (field (name "BOM_Supplier Part") "C1020")
      )
      (libsource (lib "") (part "MLB3216-601(f)_18"))
    )
    (comp (ref "FB310N")
      (value "60Ω")
      (fields
        (field (name "BOM_Manufacturer Part") "CBG321609U600T")
        (field (name "BOM_Supplier Part") "C1020")
      )
      (libsource (lib "") (part "MLB3216-601(f)_3"))
    )
    (comp (ref "FB310O")
      (value "60Ω")
      (fields
        (field (name "BOM_Manufacturer Part") "CBG321609U600T")
        (field (name "BOM_Supplier Part") "C1020")
      )
      (libsource (lib "") (part "MLB3216-601(f)_12"))
    )
    (comp (ref "FB310P")
      (value "60Ω")
      (fields
        (field (name "BOM_Manufacturer Part") "CBG321609U600T")
        (field (name "BOM_Supplier Part") "C1020")
      )
      (libsource (lib "") (part "MLB3216-601(f)_14"))
    )
    (comp (ref "FB310Q")
      (value "60Ω")
      (fields
        (field (name "BOM_Manufacturer Part") "CBG321609U600T")
        (field (name "BOM_Supplier Part") "C1020")
      )
      (libsource (lib "") (part "MLB3216-601(f)_32"))
    )
    (comp (ref "FB310R")
      (value "60Ω")
      (fields
        (field (name "BOM_Manufacturer Part") "CBG321609U600T")
        (field (name "BOM_Supplier Part") "C1020")
      )
      (libsource (lib "") (part "MLB3216-601(f)_6"))
    )
    (comp (ref "FB311A")
      (value "60Ω")
      (fields
        (field (name "BOM_Manufacturer Part") "CBG321609U600T")
        (field (name "BOM_Supplier Part") "C1020")
      )
      (libsource (lib "") (part "MLB3216-601(f)_19"))
    )
    (comp (ref "FB311B")
      (value "60Ω")
      (fields
        (field (name "BOM_Manufacturer Part") "CBG321609U600T")
        (field (name "BOM_Supplier Part") "C1020")
      )
      (libsource (lib "") (part "MLB3216-601(f)_33"))
    )
    (comp (ref "FB311C")
      (value "60Ω")
      (fields
        (field (name "BOM_Manufacturer Part") "CBG321609U600T")
        (field (name "BOM_Supplier Part") "C1020")
      )
      (libsource (lib "") (part "MLB3216-601(f)_35"))
    )
    (comp (ref "FB311D")
      (value "60Ω")
      (fields
        (field (name "BOM_Manufacturer Part") "CBG321609U600T")
        (field (name "BOM_Supplier Part") "C1020")
      )
      (libsource (lib "") (part "MLB3216-601(f)_21"))
    )
    (comp (ref "FB311E")
      (value "60Ω")
      (fields
        (field (name "BOM_Manufacturer Part") "CBG321609U600T")
        (field (name "BOM_Supplier Part") "C1020")
      )
      (libsource (lib "") (part "MLB3216-601(f)_10"))
    )
    (comp (ref "FB311F")
      (value "60Ω")
      (fields
        (field (name "BOM_Manufacturer Part") "CBG321609U600T")
        (field (name "BOM_Supplier Part") "C1020")
      )
      (libsource (lib "") (part "MLB3216-601(f)_26"))
    )
    (comp (ref "FB311G")
      (value "60Ω")
      (fields
        (field (name "BOM_Manufacturer Part") "CBG321609U600T")
        (field (name "BOM_Supplier Part") "C1020")
      )
      (libsource (lib "") (part "MLB3216-601(f)_30"))
    )
    (comp (ref "FB311H")
      (value "60Ω")
      (fields
        (field (name "BOM_Manufacturer Part") "CBG321609U600T")
        (field (name "BOM_Supplier Part") "C1020")
      )
      (libsource (lib "") (part "MLB3216-601(f)_24"))
    )
    (comp (ref "FB311I")
      (value "60Ω")
      (fields
        (field (name "BOM_Manufacturer Part") "CBG321609U600T")
        (field (name "BOM_Supplier Part") "C1020")
      )
      (libsource (lib "") (part "MLB3216-601(f)_2"))
    )
    (comp (ref "FB311J")
      (value "60Ω")
      (fields
        (field (name "BOM_Manufacturer Part") "CBG321609U600T")
        (field (name "BOM_Supplier Part") "C1020")
      )
      (libsource (lib "") (part "MLB3216-601(f)"))
    )
    (comp (ref "FB311K")
      (value "60Ω")
      (fields
        (field (name "BOM_Manufacturer Part") "CBG321609U600T")
        (field (name "BOM_Supplier Part") "C1020")
      )
      (libsource (lib "") (part "MLB3216-601(f)_1"))
    )
    (comp (ref "FB311L")
      (value "60Ω")
      (fields
        (field (name "BOM_Manufacturer Part") "CBG321609U600T")
        (field (name "BOM_Supplier Part") "C1020")
      )
      (libsource (lib "") (part "MLB3216-601(f)_16"))
    )
    (comp (ref "FB311M")
      (value "60Ω")
      (fields
        (field (name "BOM_Manufacturer Part") "CBG321609U600T")
        (field (name "BOM_Supplier Part") "C1020")
      )
      (libsource (lib "") (part "MLB3216-601(f)_20"))
    )
    (comp (ref "FB311N")
      (value "60Ω")
      (fields
        (field (name "BOM_Manufacturer Part") "CBG321609U600T")
        (field (name "BOM_Supplier Part") "C1020")
      )
      (libsource (lib "") (part "MLB3216-601(f)_13"))
    )
    (comp (ref "FB311O")
      (value "60Ω")
      (fields
        (field (name "BOM_Manufacturer Part") "CBG321609U600T")
        (field (name "BOM_Supplier Part") "C1020")
      )
      (libsource (lib "") (part "MLB3216-601(f)_23"))
    )
    (comp (ref "FB311P")
      (value "60Ω")
      (fields
        (field (name "BOM_Manufacturer Part") "CBG321609U600T")
        (field (name "BOM_Supplier Part") "C1020")
      )
      (libsource (lib "") (part "MLB3216-601(f)_8"))
    )
    (comp (ref "FB311Q")
      (value "60Ω")
      (fields
        (field (name "BOM_Manufacturer Part") "CBG321609U600T")
        (field (name "BOM_Supplier Part") "C1020")
      )
      (libsource (lib "") (part "MLB3216-601(f)_4"))
    )
    (comp (ref "FB311R")
      (value "60Ω")
      (fields
        (field (name "BOM_Manufacturer Part") "CBG321609U600T")
        (field (name "BOM_Supplier Part") "C1020")
      )
      (libsource (lib "") (part "MLB3216-601(f)_28"))
    )
    (comp (ref "R212A")
      (value "1K")
      (fields
        (field (name "BOM_Manufacturer Part") "1206W4F1001T5E")
        (field (name "BOM_Supplier Part") "C4410")
      )
      (libsource (lib "") (part "1206W4F1001T5E_4"))
    )
    (comp (ref "R212B")
      (value "1K")
      (fields
        (field (name "BOM_Manufacturer Part") "1206W4F1001T5E")
        (field (name "BOM_Supplier Part") "C4410")
      )
      (libsource (lib "") (part "1206W4F1001T5E_2"))
    )
    (comp (ref "R212C")
      (value "1K")
      (fields
        (field (name "BOM_Manufacturer Part") "1206W4F1001T5E")
        (field (name "BOM_Supplier Part") "C4410")
      )
      (libsource (lib "") (part "1206W4F1001T5E_6"))
    )
    (comp (ref "R212D")
      (value "1K")
      (fields
        (field (name "BOM_Manufacturer Part") "1206W4F1001T5E")
        (field (name "BOM_Supplier Part") "C4410")
      )
      (libsource (lib "") (part "1206W4F1001T5E_1"))
    )
    (comp (ref "R212E")
      (value "1K")
      (fields
        (field (name "BOM_Manufacturer Part") "1206W4F1001T5E")
        (field (name "BOM_Supplier Part") "C4410")
      )
      (libsource (lib "") (part "1206W4F1001T5E_5"))
    )
    (comp (ref "R212F")
      (value "1K")
      (fields
        (field (name "BOM_Manufacturer Part") "1206W4F1001T5E")
        (field (name "BOM_Supplier Part") "C4410")
      )
      (libsource (lib "") (part "1206W4F1001T5E_7"))
    )
    (comp (ref "R212G")
      (value "1K")
      (fields
        (field (name "BOM_Manufacturer Part") "1206W4F1001T5E")
        (field (name "BOM_Supplier Part") "C4410")
      )
      (libsource (lib "") (part "1206W4F1001T5E"))
    )
    (comp (ref "R212H")
      (value "1K")
      (fields
        (field (name "BOM_Manufacturer Part") "1206W4F1001T5E")
        (field (name "BOM_Supplier Part") "C4410")
      )
      (libsource (lib "") (part "1206W4F1001T5E_3"))
    )
    (comp (ref "RP300A")
      (value "220/330 Term")
      (fields
        (field (name "BOM_Manufacturer Part") "4608X-104-331/221L")
        (field (name "BOM_Supplier Part") "652-4608X104331/221L")
      )
      (libsource (lib "") (part "SCSI Terminator sip-8_1"))
    )
    (comp (ref "RP300B")
      (value "220/330 Term")
      (fields
        (field (name "BOM_Manufacturer Part") "4608X-104-331/221L")
        (field (name "BOM_Supplier Part") "652-4608X104331/221L")
      )
      (libsource (lib "") (part "SCSI Terminator sip-8_2"))
    )
    (comp (ref "RP300C")
      (value "220/330 Term")
      (fields
        (field (name "BOM_Manufacturer Part") "4608X-104-331/221L")
        (field (name "BOM_Supplier Part") "652-4608X104331/221L")
      )
      (libsource (lib "") (part "SCSI Terminator sip-8"))
    )
    (comp (ref "SW1")
      (value "DA-08RP")
      (fields (field (name "BOM_Supplier Part") "C129027"))
      (libsource (lib "") (part "DA-08RP"))
    )
    (comp (ref "U213")
      (value "74F244")
      (fields (field (name "BOM_Manufacturer Part") "74F244SCX") (field (name "BOM_Supplier Part") "C5555"))
      (libsource (lib "") (part "74F244SCX"))
    )
    (comp (ref "U310") (value "DS2107S") (libsource (lib "") (part "DS2107S")))
    (comp (ref "U311") (value "DS2107S") (libsource (lib "") (part "DS2107S")))
    (comp (ref "C300A")
      (value "100nF")
      (fields
        (field (name "BOM_Manufacturer Part") "CL31B104KBCNNNC")
        (field (name "BOM_Supplier Part") "C24497")
      )
      (libsource (lib "") (part "CL31B104KBCNNNC_3"))
    )
    (comp (ref "C300B")
      (value "10nF")
      (fields
        (field (name "BOM_Manufacturer Part") "1206B103K500NT")
        (field (name "BOM_Supplier Part") "C1846")
      )
      (libsource (lib "") (part "1206B103K500NT_2"))
    )
    (comp (ref "C300C")
      (value "100nF")
      (fields
        (field (name "BOM_Manufacturer Part") "CL31B104KBCNNNC")
        (field (name "BOM_Supplier Part") "C24497")
      )
      (libsource (lib "") (part "CL31B104KBCNNNC"))
    )
    (comp (ref "C300D")
      (value "10nF")
      (fields
        (field (name "BOM_Manufacturer Part") "1206B103K500NT")
        (field (name "BOM_Supplier Part") "C1846")
      )
      (libsource (lib "") (part "1206B103K500NT_1"))
    )
    (comp (ref "C300E")
      (value "100nF")
      (fields
        (field (name "BOM_Manufacturer Part") "CL31B104KBCNNNC")
        (field (name "BOM_Supplier Part") "C24497")
      )
      (libsource (lib "") (part "CL31B104KBCNNNC_5"))
    )
    (comp (ref "C300F")
      (value "10nF")
      (fields
        (field (name "BOM_Manufacturer Part") "1206B103K500NT")
        (field (name "BOM_Supplier Part") "C1846")
      )
      (libsource (lib "") (part "1206B103K500NT"))
    )
    (comp (ref "C300G")
      (value "100nF")
      (fields
        (field (name "BOM_Manufacturer Part") "CL31B104KBCNNNC")
        (field (name "BOM_Supplier Part") "C24497")
      )
      (libsource (lib "") (part "CL31B104KBCNNNC_4"))
    )
    (comp (ref "C300H")
      (value "10nF")
      (fields
        (field (name "BOM_Manufacturer Part") "1206B103K500NT")
        (field (name "BOM_Supplier Part") "C1846")
      )
      (libsource (lib "") (part "1206B103K500NT_3"))
    )
    (comp (ref "C300I")
      (value "100nF")
      (fields
        (field (name "BOM_Manufacturer Part") "CL31B104KBCNNNC")
        (field (name "BOM_Supplier Part") "C24497")
      )
      (libsource (lib "") (part "CL31B104KBCNNNC_1"))
    )
    (comp (ref "C301A")
      (value "10nF")
      (fields
        (field (name "BOM_Manufacturer Part") "1206B103K500NT")
        (field (name "BOM_Supplier Part") "C1846")
      )
      (libsource (lib "") (part "1206B103K500NT_4"))
    )
    (comp (ref "C302A")
      (value "100nF")
      (fields
        (field (name "BOM_Manufacturer Part") "CL31B104KBCNNNC")
        (field (name "BOM_Supplier Part") "C24497")
      )
      (libsource (lib "") (part "CL31B104KBCNNNC_2"))
    )
    (comp (ref "CN308")
      (value "TO-MB")
      (fields
        (field (name "BOM_Manufacturer Part") "Header2.54mm 1*3P")
        (field (name "BOM_Supplier Part") "C49257")
      )
      (libsource (lib "") (part "Header-Male-2.54_1x3"))
    )
    (comp (ref "CN351")
      (value "TO-LED")
      (fields
        (field (name "BOM_Manufacturer Part") "Header2.54mm 1*3P")
        (field (name "BOM_Supplier Part") "C49257")
      )
      (libsource (lib "") (part "Header-Male-2.54_1x3"))
    )
    (comp (ref "FB502")
      (value "60Ω")
      (fields
        (field (name "BOM_Manufacturer Part") "CBG321609U600T")
        (field (name "BOM_Supplier Part") "C1020")
      )
      (libsource (lib "") (part "MLB3216-601(f)_1"))
    )
    (comp (ref "FB503")
      (value "60Ω")
      (fields
        (field (name "BOM_Manufacturer Part") "CBG321609U600T")
        (field (name "BOM_Supplier Part") "C1020")
      )
      (libsource (lib "") (part "MLB3216-601(f)"))
    )
    (comp (ref "FB506")
      (value "60Ω")
      (fields
        (field (name "BOM_Manufacturer Part") "CBG321609U600T")
        (field (name "BOM_Supplier Part") "C1020")
      )
      (libsource (lib "") (part "MLB3216-601(f)_1"))
    )
    (comp (ref "J100")
      (value "ESIZE")
      (fields
        (field (name "BOM_Manufacturer Part") "Header2.54mm 1*3P")
        (field (name "BOM_Supplier Part") "C49257")
      )
      (libsource (lib "") (part "Header-Male-2.54_1x3_1"))
    )
    (comp (ref "R300A")
      (value "1K")
      (fields
        (field (name "BOM_Manufacturer Part") "1206W4F1001T5E")
        (field (name "BOM_Supplier Part") "C4410")
      )
      (libsource (lib "") (part "1206W4F1001T5E_7"))
    )
    (comp (ref "R300B")
      (value "1K")
      (fields
        (field (name "BOM_Manufacturer Part") "1206W4F1001T5E")
        (field (name "BOM_Supplier Part") "C4410")
      )
      (libsource (lib "") (part "1206W4F1001T5E_6"))
    )
    (comp (ref "R300C")
      (value "1K")
      (fields
        (field (name "BOM_Manufacturer Part") "1206W4F1001T5E")
        (field (name "BOM_Supplier Part") "C4410")
      )
      (libsource (lib "") (part "1206W4F1001T5E"))
    )
    (comp (ref "R300D")
      (value "1K")
      (fields
        (field (name "BOM_Manufacturer Part") "1206W4F1001T5E")
        (field (name "BOM_Supplier Part") "C4410")
      )
      (libsource (lib "") (part "1206W4F1001T5E_13"))
    )
    (comp (ref "R300E")
      (value "1K")
      (fields
        (field (name "BOM_Manufacturer Part") "1206W4F1001T5E")
        (field (name "BOM_Supplier Part") "C4410")
      )
      (libsource (lib "") (part "1206W4F1001T5E_5"))
    )
    (comp (ref "R300F")
      (value "1K")
      (fields
        (field (name "BOM_Manufacturer Part") "1206W4F1001T5E")
        (field (name "BOM_Supplier Part") "C4410")
      )
      (libsource (lib "") (part "1206W4F1001T5E_14"))
    )
    (comp (ref "R300G")
      (value "1K")
      (fields
        (field (name "BOM_Manufacturer Part") "1206W4F1001T5E")
        (field (name "BOM_Supplier Part") "C4410")
      )
      (libsource (lib "") (part "1206W4F1001T5E_4"))
    )
    (comp (ref "R300H")
      (value "1K")
      (fields
        (field (name "BOM_Manufacturer Part") "1206W4F1001T5E")
        (field (name "BOM_Supplier Part") "C4410")
      )
      (libsource (lib "") (part "1206W4F1001T5E_3"))
    )
    (comp (ref "R300I")
      (value "1K")
      (fields
        (field (name "BOM_Manufacturer Part") "1206W4F1001T5E")
        (field (name "BOM_Supplier Part") "C4410")
      )
      (libsource (lib "") (part "1206W4F1001T5E_11"))
    )
    (comp (ref "R300J")
      (value "1K")
      (fields
        (field (name "BOM_Manufacturer Part") "1206W4F1001T5E")
        (field (name "BOM_Supplier Part") "C4410")
      )
      (libsource (lib "") (part "1206W4F1001T5E_15"))
    )
    (comp (ref "R300K")
      (value "1K")
      (fields
        (field (name "BOM_Manufacturer Part") "1206W4F1001T5E")
        (field (name "BOM_Supplier Part") "C4410")
      )
      (libsource (lib "") (part "1206W4F1001T5E_10"))
    )
    (comp (ref "R300L")
      (value "1K")
      (fields
        (field (name "BOM_Manufacturer Part") "1206W4F1001T5E")
        (field (name "BOM_Supplier Part") "C4410")
      )
      (libsource (lib "") (part "1206W4F1001T5E_1"))
    )
    (comp (ref "R300M")
      (value "1K")
      (fields
        (field (name "BOM_Manufacturer Part") "1206W4F1001T5E")
        (field (name "BOM_Supplier Part") "C4410")
      )
      (libsource (lib "") (part "1206W4F1001T5E_8"))
    )
    (comp (ref "R300N")
      (value "1K")
      (fields
        (field (name "BOM_Manufacturer Part") "1206W4F1001T5E")
        (field (name "BOM_Supplier Part") "C4410")
      )
      (libsource (lib "") (part "1206W4F1001T5E_12"))
    )
    (comp (ref "R300O")
      (value "1K")
      (fields
        (field (name "BOM_Manufacturer Part") "1206W4F1001T5E")
        (field (name "BOM_Supplier Part") "C4410")
      )
      (libsource (lib "") (part "1206W4F1001T5E_2"))
    )
    (comp (ref "R300P")
      (value "1K")
      (fields
        (field (name "BOM_Manufacturer Part") "1206W4F1001T5E")
        (field (name "BOM_Supplier Part") "C4410")
      )
      (libsource (lib "") (part "1206W4F1001T5E_17"))
    )
    (comp (ref "R301A")
      (value "22")
      (fields
        (field (name "BOM_Manufacturer Part") "RS-06K22R0FT")
        (field (name "BOM_Supplier Part") "C140034")
      )
      (libsource (lib "") (part "RS-06K22R0FT_2"))
    )
    (comp (ref "R302A")
      (value "22")
      (fields
        (field (name "BOM_Manufacturer Part") "RS-06K22R0FT")
        (field (name "BOM_Supplier Part") "C140034")
      )
      (libsource (lib "") (part "RS-06K22R0FT"))
    )
    (comp (ref "R302B")
      (value "22")
      (fields
        (field (name "BOM_Manufacturer Part") "RS-06K22R0FT")
        (field (name "BOM_Supplier Part") "C140034")
      )
      (libsource (lib "") (part "RS-06K22R0FT_1"))
    )
    (comp (ref "R307A")
      (value "1K")
      (fields
        (field (name "BOM_Manufacturer Part") "1206W4F1001T5E")
        (field (name "BOM_Supplier Part") "C4410")
      )
      (libsource (lib "") (part "1206W4F1001T5E_9"))
    )
    (comp (ref "R307B")
      (value "1K")
      (fields
        (field (name "BOM_Manufacturer Part") "1206W4F1001T5E")
        (field (name "BOM_Supplier Part") "C4410")
      )
      (libsource (lib "") (part "1206W4F1001T5E_16"))
    )
    (comp (ref "R398")
      (value "120")
      (fields
        (field (name "BOM_Manufacturer Part") "RTT061200FTP")
        (field (name "BOM_Supplier Part") "C159715")
      )
      (libsource (lib "") (part "RTT061200FTP"))
    )
    (comp (ref "U206")
      (value "27c256")
      (fields (field (name "BOM_Manufacturer Part") "27C256"))
      (libsource (lib "") (part "27c256"))
    )
    (comp (ref "U300") (value "NCR53C710") (libsource (lib "") (part "NCR53C710")))
    (comp (ref "U301") (value "Abracon 50MHz AC0 D.9403") (libsource (lib "") (part "Osc")))
    (comp (ref "U302")
      (value "74F74D")
      (fields (field (name "BOM_Supplier Part") "C5573"))
      (libsource (lib "") (part "74F74D"))
    )
    (comp (ref "FB500")
      (value "60Ω")
      (fields
        (field (name "BOM_Manufacturer Part") "CBG321609U600T")
        (field (name "BOM_Supplier Part") "C1020")
      )
      (libsource (lib "") (part "MLB3216-601(f)"))
    )
    (comp (ref "FB501")
      (value "60Ω")
      (fields
        (field (name "BOM_Manufacturer Part") "CBG321609U600T")
        (field (name "BOM_Supplier Part") "C1020")
      )
      (libsource (lib "") (part "MLB3216-601(f)_1"))
    )
    (comp (ref "FB504")
      (value "60Ω")
      (fields
        (field (name "BOM_Manufacturer Part") "CBG321609U600T")
        (field (name "BOM_Supplier Part") "C1020")
      )
      (libsource (lib "") (part "MLB3216-601(f)_1"))
    )
    (comp (ref "FB505")
      (value "60Ω")
      (fields
        (field (name "BOM_Manufacturer Part") "CBG321609U600T")
        (field (name "BOM_Supplier Part") "C1020")
      )
      (libsource (lib "") (part "MLB3216-601(f)_1"))
    )
    (comp (ref "U202")
      (value "GAL22V10H-15")
      (fields (field (name "BOM_Manufacturer Part") "GAL220V10"))
      (libsource (lib "") (part "GAL22V10"))
    )
    (comp (ref "U203")
      (value "GAL22V10H-15")
      (fields (field (name "BOM_Manufacturer Part") "GAL220V10"))
      (libsource (lib "") (part "GAL22V10"))
    )
    (comp (ref "U205")
      (value "GAL22V10H-15")
      (fields (field (name "BOM_Manufacturer Part") "GAL220V10"))
      (libsource (lib "") (part "GAL22V10"))
    )
    (comp (ref "U207")
      (value "GAL22V10H-15")
      (fields (field (name "BOM_Manufacturer Part") "GAL220V10"))
      (libsource (lib "") (part "GAL22V10"))
    )
    (comp (ref "U303")
      (value "GAL22V10H-15")
      (fields (field (name "BOM_Manufacturer Part") "GAL220V10"))
      (libsource (lib "") (part "GAL22V10"))
    )
    (comp (ref "U304")
      (value "GAL22V10B-10")
      (fields (field (name "BOM_Manufacturer Part") "GAL220V10"))
      (libsource (lib "") (part "GAL22V10"))
    )
    (comp (ref "U305")
      (value "GAL22V10B-10")
      (fields (field (name "BOM_Manufacturer Part") "GAL220V10"))
      (libsource (lib "") (part "GAL22V10"))
    )
    (comp (ref "U306")
      (value "GAL22V10B-10")
      (fields (field (name "BOM_Manufacturer Part") "GAL220V10"))
      (libsource (lib "") (part "GAL22V10"))
    )
    (comp (ref "C1") (value "Zorro III Edge") (libsource (lib "") (part "Zorro III Edge")))
    (comp (ref "FB507")
      (value "60Ω")
      (fields
        (field (name "BOM_Manufacturer Part") "CBG321609U600T")
        (field (name "BOM_Supplier Part") "C1020")
      )
      (libsource (lib "") (part "MLB3216-601(f)"))
    )
    (comp (ref "FB508")
      (value "60Ω")
      (fields
        (field (name "BOM_Manufacturer Part") "CBG321609U600T")
        (field (name "BOM_Supplier Part") "C1020")
      )
      (libsource (lib "") (part "MLB3216-601(f)"))
    )
    (comp (ref "R100A")
      (value "1K")
      (fields
        (field (name "BOM_Manufacturer Part") "1206W4F1001T5E")
        (field (name "BOM_Supplier Part") "C4410")
      )
      (libsource (lib "") (part "1206W4F1001T5E_16"))
    )
    (comp (ref "R103A")
      (value "1K")
      (fields
        (field (name "BOM_Manufacturer Part") "1206W4F1001T5E")
        (field (name "BOM_Supplier Part") "C4410")
      )
      (libsource (lib "") (part "1206W4F1001T5E_13"))
    )
    (comp (ref "R103B")
      (value "1K")
      (fields
        (field (name "BOM_Manufacturer Part") "1206W4F1001T5E")
        (field (name "BOM_Supplier Part") "C4410")
      )
      (libsource (lib "") (part "1206W4F1001T5E_7"))
    )
    (comp (ref "R109A")
      (value "1K")
      (fields
        (field (name "BOM_Manufacturer Part") "1206W4F1001T5E")
        (field (name "BOM_Supplier Part") "C4410")
      )
      (libsource (lib "") (part "1206W4F1001T5E"))
    )
    (comp (ref "R109B")
      (value "1K")
      (fields
        (field (name "BOM_Manufacturer Part") "1206W4F1001T5E")
        (field (name "BOM_Supplier Part") "C4410")
      )
      (libsource (lib "") (part "1206W4F1001T5E_12"))
    )
    (comp (ref "R109C")
      (value "1K")
      (fields
        (field (name "BOM_Manufacturer Part") "1206W4F1001T5E")
        (field (name "BOM_Supplier Part") "C4410")
      )
      (libsource (lib "") (part "1206W4F1001T5E_4"))
    )
    (comp (ref "R109D")
      (value "1K")
      (fields
        (field (name "BOM_Manufacturer Part") "1206W4F1001T5E")
        (field (name "BOM_Supplier Part") "C4410")
      )
      (libsource (lib "") (part "1206W4F1001T5E_6"))
    )
    (comp (ref "R109E")
      (value "1K")
      (fields
        (field (name "BOM_Manufacturer Part") "1206W4F1001T5E")
        (field (name "BOM_Supplier Part") "C4410")
      )
      (libsource (lib "") (part "1206W4F1001T5E_10"))
    )
    (comp (ref "R109F")
      (value "1K")
      (fields
        (field (name "BOM_Manufacturer Part") "1206W4F1001T5E")
        (field (name "BOM_Supplier Part") "C4410")
      )
      (libsource (lib "") (part "1206W4F1001T5E_9"))
    )
    (comp (ref "R109G")
      (value "1K")
      (fields
        (field (name "BOM_Manufacturer Part") "1206W4F1001T5E")
        (field (name "BOM_Supplier Part") "C4410")
      )
      (libsource (lib "") (part "1206W4F1001T5E_17"))
    )
    (comp (ref "R109H")
      (value "1K")
      (fields
        (field (name "BOM_Manufacturer Part") "1206W4F1001T5E")
        (field (name "BOM_Supplier Part") "C4410")
      )
      (libsource (lib "") (part "1206W4F1001T5E_11"))
    )
    (comp (ref "R200A")
      (value "1K")
      (fields
        (field (name "BOM_Manufacturer Part") "1206W4F1001T5E")
        (field (name "BOM_Supplier Part") "C4410")
      )
      (libsource (lib "") (part "1206W4F1001T5E_2"))
    )
    (comp (ref "R200B")
      (value "1K")
      (fields
        (field (name "BOM_Manufacturer Part") "1206W4F1001T5E")
        (field (name "BOM_Supplier Part") "C4410")
      )
      (libsource (lib "") (part "1206W4F1001T5E_15"))
    )
    (comp (ref "R200C")
      (value "1K")
      (fields
        (field (name "BOM_Manufacturer Part") "1206W4F1001T5E")
        (field (name "BOM_Supplier Part") "C4410")
      )
      (libsource (lib "") (part "1206W4F1001T5E_14"))
    )
    (comp (ref "R200D")
      (value "1K")
      (fields
        (field (name "BOM_Manufacturer Part") "1206W4F1001T5E")
        (field (name "BOM_Supplier Part") "C4410")
      )
      (libsource (lib "") (part "1206W4F1001T5E_18"))
    )
    (comp (ref "R200E")
      (value "1K")
      (fields
        (field (name "BOM_Manufacturer Part") "1206W4F1001T5E")
        (field (name "BOM_Supplier Part") "C4410")
      )
      (libsource (lib "") (part "1206W4F1001T5E_1"))
    )
    (comp (ref "R200F")
      (value "1K")
      (fields
        (field (name "BOM_Manufacturer Part") "1206W4F1001T5E")
        (field (name "BOM_Supplier Part") "C4410")
      )
      (libsource (lib "") (part "1206W4F1001T5E_8"))
    )
    (comp (ref "R200G")
      (value "1K")
      (fields
        (field (name "BOM_Manufacturer Part") "1206W4F1001T5E")
        (field (name "BOM_Supplier Part") "C4410")
      )
      (libsource (lib "") (part "1206W4F1001T5E_3"))
    )
    (comp (ref "R200H")
      (value "1K")
      (fields
        (field (name "BOM_Manufacturer Part") "1206W4F1001T5E")
        (field (name "BOM_Supplier Part") "C4410")
      )
      (libsource (lib "") (part "1206W4F1001T5E_5"))
    )
    (comp (ref "U100")
      (value "74FCT543TSO")
      (fields (field (name "BOM_Manufacturer Part") "CY74FCT543TSOC"))
      (libsource (lib "") (part "74FCT543TSO"))
    )
    (comp (ref "U101")
      (value "74FCT543TSO")
      (fields (field (name "BOM_Manufacturer Part") "CY74FCT543TSOC"))
      (libsource (lib "") (part "74FCT543TSO"))
    )
    (comp (ref "U102")
      (value "74FCT543TSO")
      (fields (field (name "BOM_Manufacturer Part") "CY74FCT543TSOC"))
      (libsource (lib "") (part "74FCT543TSO"))
    )
    (comp (ref "U103")
      (value "74F245D")
      (fields (field (name "BOM_Supplier Part") "C5557"))
      (libsource (lib "") (part "74F245D"))
    )
    (comp (ref "U105")
      (value "74FCT543TSO")
      (fields (field (name "BOM_Manufacturer Part") "CY74FCT543TSOC"))
      (libsource (lib "") (part "74FCT543TSO"))
    )
    (comp (ref "U106")
      (value "74FCT543TSO")
      (fields (field (name "BOM_Manufacturer Part") "CY74FCT543TSOC"))
      (libsource (lib "") (part "74FCT543TSO"))
    )
    (comp (ref "U107")
      (value "74FCT543TSO")
      (fields (field (name "BOM_Manufacturer Part") "CY74FCT543TSOC"))
      (libsource (lib "") (part "74FCT543TSO"))
    )
    (comp (ref "U108")
      (value "74FCT543TSO")
      (fields (field (name "BOM_Manufacturer Part") "CY74FCT543TSOC"))
      (libsource (lib "") (part "74FCT543TSO"))
    )
    (comp (ref "U109")
      (value "74F245D")
      (fields (field (name "BOM_Supplier Part") "C5557"))
      (libsource (lib "") (part "74F245D"))
    )
    (comp (ref "U200")
      (value "74FCT374TSO")
      (fields (field (name "BOM_Manufacturer Part") "74F374D") (field (name "BOM_Supplier Part") "C5564"))
      (libsource (lib "") (part "74F374D"))
    )
    (comp (ref "U201")
      (value "74FCT521TSO")
      (fields
        (field (name "BOM_Manufacturer Part") "74FCT521CTSOG8")
        (field (name "BOM_Supplier Part") "972-74FCT521CTSOG8")
      )
      (libsource (lib "") (part "74FCT521TSO"))
    )
    (comp (ref "U204")
      (value "74FCT374TSO")
      (fields (field (name "BOM_Manufacturer Part") "74F374D") (field (name "BOM_Supplier Part") "C5564"))
      (libsource (lib "") (part "74F374D"))
    )
    (comp (ref "U307")
      (value "74F07D")
      (fields (field (name "BOM_Supplier Part") "C5540"))
      (libsource (lib "") (part "74F07D"))
    )
    (comp (ref "C1A")
      (value "100nF")
      (fields
        (field (name "BOM_Manufacturer Part") "CL31B104KBCNNNC")
        (field (name "BOM_Supplier Part") "C24497")
      )
      (libsource (lib "") (part "CL31B104KBCNNNC_21"))
    )
    (comp (ref "C1B")
      (value "47uF")
      (fields
        (field (name "BOM_Manufacturer Part") "RVT1V470M0605")
        (field (name "BOM_Supplier Part") "C3344")
      )
      (libsource (lib "") (part "RVT1V470M0605_2"))
    )
    (comp (ref "C1C")
      (value "47uF")
      (fields
        (field (name "BOM_Manufacturer Part") "RVT1V470M0605")
        (field (name "BOM_Supplier Part") "C3344")
      )
      (libsource (lib "") (part "RVT1V470M0605"))
    )
    (comp (ref "C10")
      (value "47uF")
      (fields
        (field (name "BOM_Manufacturer Part") "RVT1V470M0605")
        (field (name "BOM_Supplier Part") "C3344")
      )
      (libsource (lib "") (part "RVT1V470M0605_1"))
    )
    (comp (ref "C11")
      (value "47uF")
      (fields
        (field (name "BOM_Manufacturer Part") "RVT1V470M0605")
        (field (name "BOM_Supplier Part") "C3344")
      )
      (libsource (lib "") (part "RVT1V470M0605_1"))
    )
    (comp (ref "C12")
      (value "47uF")
      (fields
        (field (name "BOM_Manufacturer Part") "RVT1V470M0605")
        (field (name "BOM_Supplier Part") "C3344")
      )
      (libsource (lib "") (part "RVT1V470M0605_1"))
    )
    (comp (ref "C13")
      (value "47uF")
      (fields
        (field (name "BOM_Manufacturer Part") "RVT1V470M0605")
        (field (name "BOM_Supplier Part") "C3344")
      )
      (libsource (lib "") (part "RVT1V470M0605_3"))
    )
    (comp (ref "C100A")
      (value "100nF")
      (fields
        (field (name "BOM_Manufacturer Part") "CL31B104KBCNNNC")
        (field (name "BOM_Supplier Part") "C24497")
      )
      (libsource (lib "") (part "CL31B104KBCNNNC_22"))
    )
    (comp (ref "C101A")
      (value "100nF")
      (fields
        (field (name "BOM_Manufacturer Part") "CL31B104KBCNNNC")
        (field (name "BOM_Supplier Part") "C24497")
      )
      (libsource (lib "") (part "CL31B104KBCNNNC_3"))
    )
    (comp (ref "C102A")
      (value "100nF")
      (fields
        (field (name "BOM_Manufacturer Part") "CL31B104KBCNNNC")
        (field (name "BOM_Supplier Part") "C24497")
      )
      (libsource (lib "") (part "CL31B104KBCNNNC_17"))
    )
    (comp (ref "C103A")
      (value "100nF")
      (fields
        (field (name "BOM_Manufacturer Part") "CL31B104KBCNNNC")
        (field (name "BOM_Supplier Part") "C24497")
      )
      (libsource (lib "") (part "CL31B104KBCNNNC_15"))
    )
    (comp (ref "C105A")
      (value "100nF")
      (fields
        (field (name "BOM_Manufacturer Part") "CL31B104KBCNNNC")
        (field (name "BOM_Supplier Part") "C24497")
      )
      (libsource (lib "") (part "CL31B104KBCNNNC_8"))
    )
    (comp (ref "C106A")
      (value "100nF")
      (fields
        (field (name "BOM_Manufacturer Part") "CL31B104KBCNNNC")
        (field (name "BOM_Supplier Part") "C24497")
      )
      (libsource (lib "") (part "CL31B104KBCNNNC_10"))
    )
    (comp (ref "C107A")
      (value "100nF")
      (fields
        (field (name "BOM_Manufacturer Part") "CL31B104KBCNNNC")
        (field (name "BOM_Supplier Part") "C24497")
      )
      (libsource (lib "") (part "CL31B104KBCNNNC_9"))
    )
    (comp (ref "C108A")
      (value "100nF")
      (fields
        (field (name "BOM_Manufacturer Part") "CL31B104KBCNNNC")
        (field (name "BOM_Supplier Part") "C24497")
      )
      (libsource (lib "") (part "CL31B104KBCNNNC_13"))
    )
    (comp (ref "C109A")
      (value "100nF")
      (fields
        (field (name "BOM_Manufacturer Part") "CL31B104KBCNNNC")
        (field (name "BOM_Supplier Part") "C24497")
      )
      (libsource (lib "") (part "CL31B104KBCNNNC_18"))
    )
    (comp (ref "C200A")
      (value "100nF")
      (fields
        (field (name "BOM_Manufacturer Part") "CL31B104KBCNNNC")
        (field (name "BOM_Supplier Part") "C24497")
      )
      (libsource (lib "") (part "CL31B104KBCNNNC"))
    )
    (comp (ref "C201A")
      (value "100nF")
      (fields
        (field (name "BOM_Manufacturer Part") "CL31B104KBCNNNC")
        (field (name "BOM_Supplier Part") "C24497")
      )
      (libsource (lib "") (part "CL31B104KBCNNNC_11"))
    )
    (comp (ref "C202A")
      (value "100nF")
      (fields
        (field (name "BOM_Manufacturer Part") "CL31B104KBCNNNC")
        (field (name "BOM_Supplier Part") "C24497")
      )
      (libsource (lib "") (part "CL31B104KBCNNNC_7"))
    )
    (comp (ref "C203A")
      (value "100nF")
      (fields
        (field (name "BOM_Manufacturer Part") "CL31B104KBCNNNC")
        (field (name "BOM_Supplier Part") "C24497")
      )
      (libsource (lib "") (part "CL31B104KBCNNNC_2"))
    )
    (comp (ref "C204A")
      (value "100nF")
      (fields
        (field (name "BOM_Manufacturer Part") "CL31B104KBCNNNC")
        (field (name "BOM_Supplier Part") "C24497")
      )
      (libsource (lib "") (part "CL31B104KBCNNNC_12"))
    )
    (comp (ref "C205A")
      (value "100nF")
      (fields
        (field (name "BOM_Manufacturer Part") "CL31B104KBCNNNC")
        (field (name "BOM_Supplier Part") "C24497")
      )
      (libsource (lib "") (part "CL31B104KBCNNNC_23"))
    )
    (comp (ref "C206A")
      (value "100nF")
      (fields
        (field (name "BOM_Manufacturer Part") "CL31B104KBCNNNC")
        (field (name "BOM_Supplier Part") "C24497")
      )
      (libsource (lib "") (part "CL31B104KBCNNNC_1"))
    )
    (comp (ref "C207A")
      (value "100nF")
      (fields
        (field (name "BOM_Manufacturer Part") "CL31B104KBCNNNC")
        (field (name "BOM_Supplier Part") "C24497")
      )
      (libsource (lib "") (part "CL31B104KBCNNNC_6"))
    )
    (comp (ref "C212A")
      (value "100nF")
      (fields
        (field (name "BOM_Manufacturer Part") "CL31B104KBCNNNC")
        (field (name "BOM_Supplier Part") "C24497")
      )
      (libsource (lib "") (part "CL31B104KBCNNNC_20"))
    )
    (comp (ref "C303A")
      (value "100nF")
      (fields
        (field (name "BOM_Manufacturer Part") "CL31B104KBCNNNC")
        (field (name "BOM_Supplier Part") "C24497")
      )
      (libsource (lib "") (part "CL31B104KBCNNNC_19"))
    )
    (comp (ref "C304A")
      (value "100nF")
      (fields
        (field (name "BOM_Manufacturer Part") "CL31B104KBCNNNC")
        (field (name "BOM_Supplier Part") "C24497")
      )
      (libsource (lib "") (part "CL31B104KBCNNNC_14"))
    )
    (comp (ref "C305A")
      (value "100nF")
      (fields
        (field (name "BOM_Manufacturer Part") "CL31B104KBCNNNC")
        (field (name "BOM_Supplier Part") "C24497")
      )
      (libsource (lib "") (part "CL31B104KBCNNNC_4"))
    )
    (comp (ref "C306A")
      (value "100nF")
      (fields
        (field (name "BOM_Manufacturer Part") "CL31B104KBCNNNC")
        (field (name "BOM_Supplier Part") "C24497")
      )
      (libsource (lib "") (part "CL31B104KBCNNNC_5"))
    )
    (comp (ref "C307A")
      (value "100nF")
      (fields
        (field (name "BOM_Manufacturer Part") "CL31B104KBCNNNC")
        (field (name "BOM_Supplier Part") "C24497")
      )
      (libsource (lib "") (part "CL31B104KBCNNNC_16"))
    )
    (comp (ref "CN2")
      (value "TE-350211-1")
      (fields
        (field (name "BOM_Manufacturer Part") "350211-1")
        (field (name "BOM_Supplier Part") "AN1212-ND")
      )
      (libsource (lib "") (part "TE-350211-1-Simple"))
    )
    (comp (ref "D309A")
      (value "LL4007G L0")
      (fields (field (name "BOM_Supplier Part") "C483912"))
      (libsource (lib "") (part "LL4007G L0"))
    )
    (comp (ref "F309A")
      (value "TH Polyfuse 1.85A")
      (fields (field (name "BOM_Manufacturer Part") "A72-185") (field (name "BOM_Supplier Part") "C135432"))
      (libsource (lib "") (part "A72-185 POLYFUSE"))
    )
    (comp (ref "F309B")
      (value "SMD Polyfuse 1.85A")
      (fields (field (name "BOM_Manufacturer Part") "A72-185") (field (name "BOM_Supplier Part") "C135432"))
      (libsource (lib "") (part "A72-185-POLYFUSE-SMD"))
    )
    (comp (ref "FID1")
      (value "FIDUCIAL_SQUARE_DOT_128_100")
      (libsource (lib "") (part "FIDUCIAL_SQUARE_DOT_128_100"))
    )
    (comp (ref "FID2")
      (value "FIDUCIAL_SQUARE_DOT_128_100")
      (libsource (lib "") (part "FIDUCIAL_SQUARE_DOT_128_100"))
    )
    (comp (ref "FID3")
      (value "FIDUCIAL_SQUARE_DOT_128_100")
      (libsource (lib "") (part "FIDUCIAL_SQUARE_DOT_128_100"))
    )
    (comp (ref "FID4")
      (value "FIDUCIAL_SQUARE_DOT_128_100")
      (libsource (lib "") (part "FIDUCIAL_SQUARE_DOT_128_100"))
    )
    (comp (ref "FID5")
      (value "FIDUCIAL_SQUARE_DOT_128_100")
      (libsource (lib "") (part "FIDUCIAL_SQUARE_DOT_128_100"))
    )
    (comp (ref "FID6")
      (value "FIDUCIAL_SQUARE_DOT_128_100")
      (libsource (lib "") (part "FIDUCIAL_SQUARE_DOT_128_100"))
    )
    (comp (ref "MB1") (value "Mousebites") (libsource (lib "") (part "Mousebites")))
    (comp (ref "MB2") (value "Mousebites") (libsource (lib "") (part "Mousebites")))
    (comp (ref "MH1")
      (value "MOUNTINGHOLE_4MM")
      (fields (field (name "BOM_Manufacturer Part") "Mounting hole"))
      (libsource (lib "") (part "MOUNTINGHOLE_4MM"))
    )
    (comp (ref "MH2")
      (value "MOUNTINGHOLE_4MM")
      (fields (field (name "BOM_Manufacturer Part") "Mounting hole"))
      (libsource (lib "") (part "MOUNTINGHOLE_4MM"))
    )
    (comp (ref "MH3")
      (value "MOUNTINGHOLE_4MM")
      (fields (field (name "BOM_Manufacturer Part") "Mounting hole"))
      (libsource (lib "") (part "MOUNTINGHOLE_4MM"))
    )
    (comp (ref "MH4")
      (value "MOUNTINGHOLE_4MM")
      (fields (field (name "BOM_Manufacturer Part") "Mounting hole"))
      (libsource (lib "") (part "MOUNTINGHOLE_4MM"))
    )
    (comp (ref "MK5") (value "Mounting_Hole") (libsource (lib "") (part "Mounting_Hole")))
    (comp (ref "MK6") (value "Mounting_Hole") (libsource (lib "") (part "Mounting_Hole")))
    (comp (ref "MK7") (value "Mounting_Hole") (libsource (lib "") (part "Mounting_Hole")))
    (comp (ref "C400A")
      (value "4.7uF")
      (fields
        (field (name "BOM_Manufacturer Part") "VZH4R7M1HTR-0406")
        (field (name "BOM_Supplier Part") "C164079")
      )
      (libsource (lib "") (part "VZH4R7M1HTR-0406"))
    )
    (comp (ref "C400B")
      (value "100nF")
      (fields
        (field (name "BOM_Manufacturer Part") "CL31B104KBCNNNC")
        (field (name "BOM_Supplier Part") "C24497")
      )
      (libsource (lib "") (part "CL31B104KBCNNNC_1"))
    )
    (comp (ref "C401A")
      (value "4.7uF")
      (fields
        (field (name "BOM_Manufacturer Part") "VZH4R7M1HTR-0406")
        (field (name "BOM_Supplier Part") "C164079")
      )
      (libsource (lib "") (part "VZH4R7M1HTR-0406_1"))
    )
    (comp (ref "C401B")
      (value "100nF")
      (fields
        (field (name "BOM_Manufacturer Part") "CL31B104KBCNNNC")
        (field (name "BOM_Supplier Part") "C24497")
      )
      (libsource (lib "") (part "CL31B104KBCNNNC_2"))
    )
    (comp (ref "C402")
      (value "100nF")
      (fields
        (field (name "BOM_Manufacturer Part") "CL31B104KBCNNNC")
        (field (name "BOM_Supplier Part") "C24497")
      )
      (libsource (lib "") (part "CL31B104KBCNNNC"))
    )
    (comp (ref "C403")
      (value "4.7uF")
      (fields
        (field (name "BOM_Manufacturer Part") "VZH4R7M1HTR-0406")
        (field (name "BOM_Supplier Part") "C164079")
      )
      (libsource (lib "") (part "VZH4R7M1HTR-0406_2"))
    )
    (comp (ref "CN400")
      (value "IDC-M-Right")
      (fields
        (field (name "BOM_Manufacturer Part") "Z-231012050106")
        (field (name "BOM_Supplier Part") "C221060")
      )
      (libsource (lib "") (part "Z-231012050106"))
    )
    (comp (ref "FID7")
      (value "FIDUCIAL_SQUARE_DOT_128_100")
      (libsource (lib "") (part "FIDUCIAL_SQUARE_DOT_128_100"))
    )
    (comp (ref "FID8")
      (value "FIDUCIAL_SQUARE_DOT_128_100")
      (libsource (lib "") (part "FIDUCIAL_SQUARE_DOT_128_100"))
    )
    (comp (ref "MK1") (value "Mounting_Hole") (libsource (lib "") (part "Mounting_Hole")))
    (comp (ref "MK2") (value "Mounting_Hole") (libsource (lib "") (part "Mounting_Hole")))
    (comp (ref "U400") (value "DS2107S") (libsource (lib "") (part "DS2107S")))
    (comp (ref "U401") (value "DS2107S") (libsource (lib "") (part "DS2107S")))
  )
  (nets
    (net (code "1") (name "A0") (class "Default")
      (node (ref "R300K") (pin "1") (pinfunction "1_1") (pintype "input"))
      (node (ref "U300") (pin "144") (pinfunction "A0_144") (pintype "unspecified"))
      (node (ref "U304") (pin "26") (pinfunction "IOQ_26") (pintype "unspecified"))
      (node (ref "U305") (pin "16") (pinfunction "I_16") (pintype "unspecified"))
    )
    (net (code "2") (name "A1") (class "Default")
      (node (ref "R300L") (pin "1") (pinfunction "1_1") (pintype "input"))
      (node (ref "U300") (pin "145") (pinfunction "A1_145") (pintype "unspecified"))
      (node (ref "U304") (pin "27") (pinfunction "IOQ_27") (pintype "unspecified"))
      (node (ref "U305") (pin "13") (pinfunction "I_13") (pintype "unspecified"))
    )
    (net (code "3") (name "A2") (class "Default")
      (node (ref "R300I") (pin "1") (pinfunction "1_1") (pintype "input"))
      (node (ref "U103") (pin "7") (pinfunction "A5_7") (pintype "unspecified"))
      (node (ref "U202") (pin "7") (pinfunction "I_7") (pintype "unspecified"))
      (node (ref "U206") (pin "10") (pinfunction "A0_10") (pintype "input"))
      (node (ref "U300") (pin "146") (pinfunction "A2_146") (pintype "unspecified"))
    )
    (net (code "4") (name "A3") (class "Default")
      (node (ref "R300J") (pin "1") (pinfunction "1_1") (pintype "input"))
      (node (ref "U103") (pin "6") (pinfunction "A4_6") (pintype "unspecified"))
      (node (ref "U202") (pin "6") (pinfunction "I_6") (pintype "unspecified"))
      (node (ref "U206") (pin "9") (pinfunction "A1_9") (pintype "input"))
      (node (ref "U300") (pin "147") (pinfunction "A3_147") (pintype "unspecified"))
    )
    (net (code "5") (name "A4") (class "Default")
      (node (ref "U103") (pin "5") (pinfunction "A3_5") (pintype "unspecified"))
      (node (ref "U202") (pin "5") (pinfunction "I_5") (pintype "unspecified"))
      (node (ref "U206") (pin "8") (pinfunction "A2_8") (pintype "input"))
      (node (ref "U300") (pin "148") (pinfunction "A4_148") (pintype "unspecified"))
    )
    (net (code "6") (name "A5") (class "Default")
      (node (ref "U103") (pin "4") (pinfunction "A2_4") (pintype "unspecified"))
      (node (ref "U202") (pin "4") (pinfunction "I_4") (pintype "unspecified"))
      (node (ref "U206") (pin "7") (pinfunction "A3_7") (pintype "input"))
      (node (ref "U300") (pin "150") (pinfunction "A5_150") (pintype "unspecified"))
    )
    (net (code "7") (name "A6") (class "Default")
      (node (ref "U103") (pin "3") (pinfunction "A1_3") (pintype "unspecified"))
      (node (ref "U202") (pin "3") (pinfunction "I_3") (pintype "unspecified"))
      (node (ref "U206") (pin "6") (pinfunction "A4_6") (pintype "input"))
      (node (ref "U300") (pin "151") (pinfunction "A6_151") (pintype "unspecified"))
    )
    (net (code "8") (name "A7") (class "Default")
      (node (ref "U103") (pin "2") (pinfunction "A0_2") (pintype "unspecified"))
      (node (ref "U206") (pin "5") (pinfunction "A5_5") (pintype "input"))
      (node (ref "U300") (pin "152") (pinfunction "A7_152") (pintype "unspecified"))
    )
    (net (code "9") (name "A8") (class "Default")
      (node (ref "U102") (pin "10") (pinfunction "A7_10") (pintype "bidirectional"))
      (node (ref "U202") (pin "9") (pinfunction "I_9") (pintype "unspecified"))
      (node (ref "U206") (pin "4") (pinfunction "A6_4") (pintype "input"))
      (node (ref "U300") (pin "154") (pinfunction "A8_154") (pintype "unspecified"))
    )
    (net (code "10") (name "A9") (class "Default")
      (node (ref "U102") (pin "9") (pinfunction "A6_9") (pintype "bidirectional"))
      (node (ref "U206") (pin "3") (pinfunction "A7_3") (pintype "input"))
      (node (ref "U300") (pin "155") (pinfunction "A9_155") (pintype "unspecified"))
    )
    (net (code "11") (name "A10") (class "Default")
      (node (ref "U102") (pin "8") (pinfunction "A5_8") (pintype "bidirectional"))
      (node (ref "U206") (pin "25") (pinfunction "A8_25") (pintype "output"))
      (node (ref "U300") (pin "157") (pinfunction "A10_157") (pintype "unspecified"))
    )
    (net (code "12") (name "A11") (class "Default")
      (node (ref "U102") (pin "7") (pinfunction "A4_7") (pintype "bidirectional"))
      (node (ref "U206") (pin "24") (pinfunction "A9_24") (pintype "output"))
      (node (ref "U300") (pin "158") (pinfunction "A11_158") (pintype "unspecified"))
    )
    (net (code "13") (name "A12") (class "Default")
      (node (ref "U102") (pin "6") (pinfunction "A3_6") (pintype "bidirectional"))
      (node (ref "U206") (pin "21") (pinfunction "A10_21") (pintype "output"))
      (node (ref "U300") (pin "159") (pinfunction "A12_159") (pintype "unspecified"))
    )
    (net (code "14") (name "A13") (class "Default")
      (node (ref "U102") (pin "5") (pinfunction "A2_5") (pintype "bidirectional"))
      (node (ref "U206") (pin "23") (pinfunction "A11_23") (pintype "output"))
      (node (ref "U300") (pin "160") (pinfunction "A13_160") (pintype "unspecified"))
    )
    (net (code "15") (name "A14") (class "Default")
      (node (ref "U102") (pin "4") (pinfunction "A1_4") (pintype "bidirectional"))
      (node (ref "U206") (pin "2") (pinfunction "A12_2") (pintype "input"))
      (node (ref "U300") (pin "1") (pinfunction "A14_1") (pintype "unspecified"))
    )
    (net (code "16") (name "A15") (class "Default")
      (node (ref "U102") (pin "3") (pinfunction "A0_3") (pintype "bidirectional"))
      (node (ref "U206") (pin "26") (pinfunction "A13_26") (pintype "output"))
      (node (ref "U300") (pin "3") (pinfunction "A15_3") (pintype "unspecified"))
    )
    (net (code "17") (name "A16") (class "Default")
      (node (ref "U101") (pin "10") (pinfunction "A7_10") (pintype "bidirectional"))
      (node (ref "U206") (pin "27") (pinfunction "A14_27") (pintype "output"))
      (node (ref "U300") (pin "4") (pinfunction "A16_4") (pintype "unspecified"))
    )
    (net (code "18") (name "A17") (class "Default")
      (node (ref "J100") (pin "3") (pinfunction "3_3") (pintype "input"))
      (node (ref "U101") (pin "9") (pinfunction "A6_9") (pintype "bidirectional"))
      (node (ref "U203") (pin "5") (pinfunction "I_5") (pintype "unspecified"))
      (node (ref "U300") (pin "5") (pinfunction "A17_5") (pintype "unspecified"))
    )
    (net (code "19") (name "A18") (class "Default")
      (node (ref "U101") (pin "8") (pinfunction "A5_8") (pintype "bidirectional"))
      (node (ref "U203") (pin "4") (pinfunction "I_4") (pintype "unspecified"))
      (node (ref "U300") (pin "7") (pinfunction "A18_7") (pintype "unspecified"))
    )
    (net (code "20") (name "A19") (class "Default")
      (node (ref "U101") (pin "7") (pinfunction "A4_7") (pintype "bidirectional"))
      (node (ref "U203") (pin "3") (pinfunction "I_3") (pintype "unspecified"))
      (node (ref "U300") (pin "8") (pinfunction "A19_8") (pintype "unspecified"))
    )
    (net (code "21") (name "A20") (class "Default")
      (node (ref "U101") (pin "6") (pinfunction "A3_6") (pintype "bidirectional"))
      (node (ref "U300") (pin "10") (pinfunction "A20_10") (pintype "unspecified"))
    )
    (net (code "22") (name "A21") (class "Default")
      (node (ref "U101") (pin "5") (pinfunction "A2_5") (pintype "bidirectional"))
      (node (ref "U300") (pin "11") (pinfunction "A21_11") (pintype "unspecified"))
    )
    (net (code "23") (name "A22") (class "Default")
      (node (ref "U101") (pin "4") (pinfunction "A1_4") (pintype "bidirectional"))
      (node (ref "U300") (pin "12") (pinfunction "A22_12") (pintype "unspecified"))
    )
    (net (code "24") (name "A23") (class "Default")
      (node (ref "U101") (pin "3") (pinfunction "A0_3") (pintype "bidirectional"))
      (node (ref "U203") (pin "2") (pinfunction "CLK/I_2") (pintype "unspecified"))
      (node (ref "U300") (pin "13") (pinfunction "A23_13") (pintype "unspecified"))
    )
    (net (code "25") (name "A24") (class "Default")
      (node (ref "U100") (pin "10") (pinfunction "A7_10") (pintype "bidirectional"))
      (node (ref "U201") (pin "17") (pinfunction "A7_17") (pintype "unspecified"))
      (node (ref "U300") (pin "14") (pinfunction "A24_14") (pintype "unspecified"))
    )
    (net (code "26") (name "A25") (class "Default")
      (node (ref "U100") (pin "9") (pinfunction "A6_9") (pintype "bidirectional"))
      (node (ref "U201") (pin "15") (pinfunction "A6_15") (pintype "unspecified"))
      (node (ref "U300") (pin "16") (pinfunction "A25_16") (pintype "unspecified"))
    )
    (net (code "27") (name "A26") (class "Default")
      (node (ref "U100") (pin "8") (pinfunction "A5_8") (pintype "bidirectional"))
      (node (ref "U201") (pin "13") (pinfunction "A5_13") (pintype "unspecified"))
      (node (ref "U300") (pin "17") (pinfunction "A26_17") (pintype "unspecified"))
    )
    (net (code "28") (name "A27") (class "Default")
      (node (ref "U100") (pin "7") (pinfunction "A4_7") (pintype "bidirectional"))
      (node (ref "U201") (pin "11") (pinfunction "A4_11") (pintype "unspecified"))
      (node (ref "U300") (pin "18") (pinfunction "A27_18") (pintype "unspecified"))
    )
    (net (code "29") (name "A28") (class "Default")
      (node (ref "U100") (pin "6") (pinfunction "A3_6") (pintype "bidirectional"))
      (node (ref "U201") (pin "8") (pinfunction "A3_8") (pintype "unspecified"))
      (node (ref "U300") (pin "20") (pinfunction "A28_20") (pintype "unspecified"))
    )
    (net (code "30") (name "A29") (class "Default")
      (node (ref "U100") (pin "5") (pinfunction "A2_5") (pintype "bidirectional"))
      (node (ref "U201") (pin "6") (pinfunction "A2_6") (pintype "unspecified"))
      (node (ref "U300") (pin "21") (pinfunction "A29_21") (pintype "unspecified"))
    )
    (net (code "31") (name "A30") (class "Default")
      (node (ref "U100") (pin "4") (pinfunction "A1_4") (pintype "bidirectional"))
      (node (ref "U201") (pin "4") (pinfunction "A1_4") (pintype "unspecified"))
      (node (ref "U300") (pin "23") (pinfunction "A30_23") (pintype "unspecified"))
    )
    (net (code "32") (name "A31") (class "Default")
      (node (ref "U100") (pin "3") (pinfunction "A0_3") (pintype "bidirectional"))
      (node (ref "U201") (pin "2") (pinfunction "A0_2") (pintype "unspecified"))
      (node (ref "U300") (pin "24") (pinfunction "A31_24") (pintype "unspecified"))
    )
    (net (code "33") (name "ABOEH") (class "Default")
      (node (ref "U100") (pin "13") (pinfunction "OEAB_13") (pintype "unspecified"))
      (node (ref "U100") (pin "2") (pinfunction "OEBA_2") (pintype "unspecified"))
      (node (ref "U101") (pin "13") (pinfunction "OEAB_13") (pintype "unspecified"))
      (node (ref "U101") (pin "2") (pinfunction "OEBA_2") (pintype "unspecified"))
      (node (ref "U102") (pin "13") (pinfunction "OEAB_13") (pintype "unspecified"))
      (node (ref "U102") (pin "2") (pinfunction "OEBA_2") (pintype "unspecified"))
      (node (ref "U205") (pin "27") (pinfunction "IOQ_27") (pintype "unspecified"))
      (node (ref "U306") (pin "10") (pinfunction "I_10") (pintype "unspecified"))
    )
    (net (code "34") (name "ABOEL") (class "Default")
      (node (ref "U103") (pin "19") (pinfunction "OE#_19") (pintype "unspecified"))
      (node (ref "U109") (pin "19") (pinfunction "OE#_19") (pintype "unspecified"))
      (node (ref "U205") (pin "26") (pinfunction "IOQ_26") (pintype "unspecified"))
    )
    (net (code "35") (name "BERR") (class "Default")
      (node (ref "R307B") (pin "2") (pinfunction "2_2") (pintype "input"))
      (node (ref "U202") (pin "17") (pinfunction "IOQ_17") (pintype "unspecified"))
      (node (ref "U300") (pin "37") (pinfunction "BERR/-TEA/_37") (pintype "unspecified"))
      (node (ref "U303") (pin "10") (pinfunction "I_10") (pintype "unspecified"))
      (node (ref "U306") (pin "11") (pinfunction "I_11") (pintype "unspecified"))
      (node (ref "U307") (pin "6") (pinfunction "3Y_6") (pintype "unspecified"))
    )
    (net (code "36") (name "BGACK") (class "Default")
      (node (ref "R300A") (pin "1") (pinfunction "1_1") (pintype "input"))
      (node (ref "U300") (pin "98") (pinfunction "BGACK/-BB/_98") (pintype "unspecified"))
    )
    (net (code "37") (name "BMASTER") (class "Default")
      (node (ref "U100") (pin "23") (pinfunction "CEBA_23") (pintype "unspecified"))
      (node (ref "U101") (pin "23") (pinfunction "CEBA_23") (pintype "unspecified"))
      (node (ref "U102") (pin "23") (pinfunction "CEBA_23") (pintype "unspecified"))
      (node (ref "U103") (pin "1") (pinfunction "T/R#_1") (pintype "unspecified"))
      (node (ref "U109") (pin "1") (pinfunction "T/R#_1") (pintype "unspecified"))
      (node (ref "U303") (pin "27") (pinfunction "IOQ_27") (pintype "unspecified"))
    )
    (net (code "38") (name "CBACK") (class "Default")
      (node (ref "R300B") (pin "2") (pinfunction "2_2") (pintype "input"))
      (node (ref "U300") (pin "35") (pinfunction "CBACK/-TBI/_35") (pintype "unspecified"))
      (node (ref "U306") (pin "27") (pinfunction "IOQ_27") (pintype "unspecified"))
    )
    (net (code "39") (name "CBREQ") (class "Default")
      (node (ref "R300C") (pin "1") (pinfunction "1_1") (pintype "input"))
      (node (ref "U300") (pin "33") (pinfunction "CBREQ/-TT1/_33") (pintype "unspecified"))
      (node (ref "U306") (pin "6") (pinfunction "I_6") (pintype "unspecified"))
    )
    (net (code "40") (name "CLK") (class "Default")
      (node (ref "R302B") (pin "1") (pinfunction "1_1") (pintype "input"))
      (node (ref "U205") (pin "2") (pinfunction "CLK/I_2") (pintype "unspecified"))
      (node (ref "U207") (pin "2") (pinfunction "CLK/I_2") (pintype "unspecified"))
      (node (ref "U300") (pin "41") (pinfunction "BCLK_41") (pintype "unspecified"))
      (node (ref "U303") (pin "12") (pinfunction "I_12") (pintype "unspecified"))
      (node (ref "U305") (pin "2") (pinfunction "CLK/I_2") (pintype "unspecified"))
    )
    (net (code "41") (name "CLKI") (class "Default")
      (node (ref "R302A") (pin "1") (pinfunction "1_1") (pintype "input"))
      (node (ref "U302") (pin "2") (pinfunction "D0_2") (pintype "unspecified"))
      (node (ref "U304") (pin "2") (pinfunction "CLK/I_2") (pintype "unspecified"))
      (node (ref "U306") (pin "2") (pinfunction "CLK/I_2") (pintype "unspecified"))
    )
    (net (code "42") (name "CLK_50M") (class "Default")
      (node (ref "R301A") (pin "1") (pinfunction "1_1") (pintype "input"))
      (node (ref "U300") (pin "102") (pinfunction "SCLK_102") (pintype "unspecified"))
      (node (ref "U302") (pin "3") (pinfunction "CP0_3") (pintype "unspecified"))
    )
    (net (code "43") (name "D0") (class "Default")
      (node (ref "U107") (pin "10") (pinfunction "A7_10") (pintype "bidirectional"))
      (node (ref "U204") (pin "18") (pinfunction "D7_18") (pintype "unspecified"))
      (node (ref "U204") (pin "19") (pinfunction "Q7_19") (pintype "unspecified"))
      (node (ref "U213") (pin "3") (pinfunction "O4_3") (pintype "unspecified"))
      (node (ref "U300") (pin "85") (pinfunction "D0_85") (pintype "unspecified"))
    )
    (net (code "44") (name "D1") (class "Default")
      (node (ref "U107") (pin "9") (pinfunction "A6_9") (pintype "bidirectional"))
      (node (ref "U204") (pin "16") (pinfunction "Q6_16") (pintype "unspecified"))
      (node (ref "U204") (pin "17") (pinfunction "D6_17") (pintype "unspecified"))
      (node (ref "U213") (pin "5") (pinfunction "O5_5") (pintype "unspecified"))
      (node (ref "U300") (pin "84") (pinfunction "D1_84") (pintype "unspecified"))
    )
    (net (code "45") (name "D2") (class "Default")
      (node (ref "U107") (pin "8") (pinfunction "A5_8") (pintype "bidirectional"))
      (node (ref "U204") (pin "14") (pinfunction "D5_14") (pintype "unspecified"))
      (node (ref "U204") (pin "15") (pinfunction "Q5_15") (pintype "unspecified"))
      (node (ref "U213") (pin "7") (pinfunction "O6_7") (pintype "unspecified"))
      (node (ref "U300") (pin "83") (pinfunction "D2_83") (pintype "unspecified"))
    )
    (net (code "46") (name "D2Z") (class "Default")
      (node (ref "U105") (pin "11") (pinfunction "CEAB_11") (pintype "unspecified"))
      (node (ref "U106") (pin "11") (pinfunction "CEAB_11") (pintype "unspecified"))
      (node (ref "U107") (pin "11") (pinfunction "CEAB_11") (pintype "unspecified"))
      (node (ref "U108") (pin "11") (pinfunction "CEAB_11") (pintype "unspecified"))
      (node (ref "U205") (pin "21") (pinfunction "IOQ_21") (pintype "unspecified"))
    )
    (net (code "47") (name "D3") (class "Default")
      (node (ref "U107") (pin "7") (pinfunction "A4_7") (pintype "bidirectional"))
      (node (ref "U204") (pin "12") (pinfunction "Q4_12") (pintype "unspecified"))
      (node (ref "U204") (pin "13") (pinfunction "D4_13") (pintype "unspecified"))
      (node (ref "U213") (pin "9") (pinfunction "O7_9") (pintype "unspecified"))
      (node (ref "U300") (pin "81") (pinfunction "D3_81") (pintype "unspecified"))
    )
    (net (code "48") (name "D4") (class "Default")
      (node (ref "U107") (pin "6") (pinfunction "A3_6") (pintype "bidirectional"))
      (node (ref "U204") (pin "8") (pinfunction "D3_8") (pintype "unspecified"))
      (node (ref "U204") (pin "9") (pinfunction "Q3_9") (pintype "unspecified"))
      (node (ref "U213") (pin "12") (pinfunction "O3_12") (pintype "unspecified"))
      (node (ref "U300") (pin "80") (pinfunction "D4_80") (pintype "unspecified"))
    )
    (net (code "49") (name "D5") (class "Default")
      (node (ref "U107") (pin "5") (pinfunction "A2_5") (pintype "bidirectional"))
      (node (ref "U204") (pin "6") (pinfunction "Q2_6") (pintype "unspecified"))
      (node (ref "U204") (pin "7") (pinfunction "D2_7") (pintype "unspecified"))
      (node (ref "U213") (pin "14") (pinfunction "O2_14") (pintype "unspecified"))
      (node (ref "U300") (pin "78") (pinfunction "D5_78") (pintype "unspecified"))
    )
    (net (code "50") (name "D6") (class "Default")
      (node (ref "U107") (pin "4") (pinfunction "A1_4") (pintype "bidirectional"))
      (node (ref "U204") (pin "4") (pinfunction "D1_4") (pintype "unspecified"))
      (node (ref "U204") (pin "5") (pinfunction "Q1_5") (pintype "unspecified"))
      (node (ref "U213") (pin "16") (pinfunction "O1_16") (pintype "unspecified"))
      (node (ref "U300") (pin "77") (pinfunction "D6_77") (pintype "unspecified"))
    )
    (net (code "51") (name "D7") (class "Default")
      (node (ref "U107") (pin "3") (pinfunction "A0_3") (pintype "bidirectional"))
      (node (ref "U204") (pin "2") (pinfunction "Q0_2") (pintype "unspecified"))
      (node (ref "U204") (pin "3") (pinfunction "D0_3") (pintype "unspecified"))
      (node (ref "U213") (pin "18") (pinfunction "O0_18") (pintype "unspecified"))
      (node (ref "U300") (pin "76") (pinfunction "D7_76") (pintype "unspecified"))
    )
    (net (code "52") (name "D8") (class "Default")
      (node (ref "U106") (pin "10") (pinfunction "A7_10") (pintype "bidirectional"))
      (node (ref "U300") (pin "73") (pinfunction "D8_73") (pintype "unspecified"))
    )
    (net (code "53") (name "D9") (class "Default")
      (node (ref "U106") (pin "9") (pinfunction "A6_9") (pintype "bidirectional"))
      (node (ref "U300") (pin "72") (pinfunction "D9_72") (pintype "unspecified"))
    )
    (net (code "54") (name "D10") (class "Default")
      (node (ref "U106") (pin "8") (pinfunction "A5_8") (pintype "bidirectional"))
      (node (ref "U300") (pin "71") (pinfunction "D10_71") (pintype "unspecified"))
    )
    (net (code "55") (name "D11") (class "Default")
      (node (ref "U106") (pin "7") (pinfunction "A4_7") (pintype "bidirectional"))
      (node (ref "U300") (pin "70") (pinfunction "D11_70") (pintype "unspecified"))
    )
    (net (code "56") (name "D12") (class "Default")
      (node (ref "U106") (pin "6") (pinfunction "A3_6") (pintype "bidirectional"))
      (node (ref "U206") (pin "11") (pinfunction "D0_11") (pintype "input"))
      (node (ref "U300") (pin "68") (pinfunction "D12_68") (pintype "unspecified"))
    )
    (net (code "57") (name "D13") (class "Default")
      (node (ref "U106") (pin "5") (pinfunction "A2_5") (pintype "bidirectional"))
      (node (ref "U206") (pin "12") (pinfunction "D1_12") (pintype "passive"))
      (node (ref "U300") (pin "67") (pinfunction "D13_67") (pintype "unspecified"))
    )
    (net (code "58") (name "D14") (class "Default")
      (node (ref "U106") (pin "4") (pinfunction "A1_4") (pintype "bidirectional"))
      (node (ref "U206") (pin "13") (pinfunction "D2_13") (pintype "input"))
      (node (ref "U300") (pin "66") (pinfunction "D14_66") (pintype "unspecified"))
    )
    (net (code "59") (name "D15") (class "Default")
      (node (ref "U106") (pin "3") (pinfunction "A0_3") (pintype "bidirectional"))
      (node (ref "U206") (pin "15") (pinfunction "D3_15") (pintype "output"))
      (node (ref "U300") (pin "65") (pinfunction "D15_65") (pintype "unspecified"))
    )
    (net (code "60") (name "D16") (class "Default")
      (node (ref "U108") (pin "3") (pinfunction "A0_3") (pintype "bidirectional"))
      (node (ref "U300") (pin "62") (pinfunction "D16_62") (pintype "unspecified"))
    )
    (net (code "61") (name "D17") (class "Default")
      (node (ref "U108") (pin "4") (pinfunction "A1_4") (pintype "bidirectional"))
      (node (ref "U300") (pin "60") (pinfunction "D17_60") (pintype "unspecified"))
    )
    (net (code "62") (name "D18") (class "Default")
      (node (ref "U108") (pin "5") (pinfunction "A2_5") (pintype "bidirectional"))
      (node (ref "U300") (pin "59") (pinfunction "D18_59") (pintype "unspecified"))
    )
    (net (code "63") (name "D19") (class "Default")
      (node (ref "U108") (pin "6") (pinfunction "A3_6") (pintype "bidirectional"))
      (node (ref "U300") (pin "58") (pinfunction "D19_58") (pintype "unspecified"))
    )
    (net (code "64") (name "D20") (class "Default")
      (node (ref "U108") (pin "7") (pinfunction "A4_7") (pintype "bidirectional"))
      (node (ref "U300") (pin "57") (pinfunction "D20_57") (pintype "unspecified"))
    )
    (net (code "65") (name "D21") (class "Default")
      (node (ref "U108") (pin "8") (pinfunction "A5_8") (pintype "bidirectional"))
      (node (ref "U300") (pin "56") (pinfunction "D21_56") (pintype "unspecified"))
    )
    (net (code "66") (name "D22") (class "Default")
      (node (ref "U108") (pin "9") (pinfunction "A6_9") (pintype "bidirectional"))
      (node (ref "U300") (pin "55") (pinfunction "D22_55") (pintype "unspecified"))
    )
    (net (code "67") (name "D23") (class "Default")
      (node (ref "U108") (pin "10") (pinfunction "A7_10") (pintype "bidirectional"))
      (node (ref "U300") (pin "53") (pinfunction "D23_53") (pintype "unspecified"))
    )
    (net (code "68") (name "D24") (class "Default")
      (node (ref "U105") (pin "3") (pinfunction "A0_3") (pintype "bidirectional"))
      (node (ref "U200") (pin "18") (pinfunction "D7_18") (pintype "unspecified"))
      (node (ref "U300") (pin "51") (pinfunction "D24_51") (pintype "unspecified"))
    )
    (net (code "69") (name "D25") (class "Default")
      (node (ref "U105") (pin "4") (pinfunction "A1_4") (pintype "bidirectional"))
      (node (ref "U200") (pin "17") (pinfunction "D6_17") (pintype "unspecified"))
      (node (ref "U300") (pin "50") (pinfunction "D25_50") (pintype "unspecified"))
    )
    (net (code "70") (name "D26") (class "Default")
      (node (ref "U105") (pin "5") (pinfunction "A2_5") (pintype "bidirectional"))
      (node (ref "U200") (pin "14") (pinfunction "D5_14") (pintype "unspecified"))
      (node (ref "U300") (pin "48") (pinfunction "D26_48") (pintype "unspecified"))
    )
    (net (code "71") (name "D27") (class "Default")
      (node (ref "U105") (pin "6") (pinfunction "A3_6") (pintype "bidirectional"))
      (node (ref "U200") (pin "13") (pinfunction "D4_13") (pintype "unspecified"))
      (node (ref "U300") (pin "47") (pinfunction "D27_47") (pintype "unspecified"))
    )
    (net (code "72") (name "D28") (class "Default")
      (node (ref "U105") (pin "7") (pinfunction "A4_7") (pintype "bidirectional"))
      (node (ref "U200") (pin "8") (pinfunction "D3_8") (pintype "unspecified"))
      (node (ref "U206") (pin "16") (pinfunction "D4_16") (pintype "output"))
      (node (ref "U300") (pin "45") (pinfunction "D28_45") (pintype "unspecified"))
    )
    (net (code "73") (name "D29") (class "Default")
      (node (ref "U105") (pin "8") (pinfunction "A5_8") (pintype "bidirectional"))
      (node (ref "U200") (pin "7") (pinfunction "D2_7") (pintype "unspecified"))
      (node (ref "U206") (pin "17") (pinfunction "D5_17") (pintype "output"))
      (node (ref "U300") (pin "44") (pinfunction "D29_44") (pintype "unspecified"))
    )
    (net (code "74") (name "D30") (class "Default")
      (node (ref "U105") (pin "9") (pinfunction "A6_9") (pintype "bidirectional"))
      (node (ref "U200") (pin "4") (pinfunction "D1_4") (pintype "unspecified"))
      (node (ref "U206") (pin "18") (pinfunction "D6_18") (pintype "output"))
      (node (ref "U300") (pin "43") (pinfunction "D30_43") (pintype "unspecified"))
    )
    (net (code "75") (name "D31") (class "Default")
      (node (ref "U105") (pin "10") (pinfunction "A7_10") (pintype "bidirectional"))
      (node (ref "U200") (pin "3") (pinfunction "D0_3") (pintype "unspecified"))
      (node (ref "U206") (pin "19") (pinfunction "D7_19") (pintype "output"))
      (node (ref "U300") (pin "42") (pinfunction "D31_42") (pintype "unspecified"))
    )
    (net (code "76") (name "DBLT") (class "Default")
      (node (ref "U105") (pin "1") (pinfunction "LEBA_1") (pintype "unspecified"))
      (node (ref "U105") (pin "14") (pinfunction "LEAB_14") (pintype "unspecified"))
      (node (ref "U106") (pin "1") (pinfunction "LEBA_1") (pintype "unspecified"))
      (node (ref "U106") (pin "14") (pinfunction "LEAB_14") (pintype "unspecified"))
      (node (ref "U107") (pin "1") (pinfunction "LEBA_1") (pintype "unspecified"))
      (node (ref "U107") (pin "14") (pinfunction "LEAB_14") (pintype "unspecified"))
      (node (ref "U108") (pin "1") (pinfunction "LEBA_1") (pintype "unspecified"))
      (node (ref "U108") (pin "14") (pinfunction "LEAB_14") (pintype "unspecified"))
      (node (ref "U205") (pin "24") (pinfunction "IOQ_24") (pintype "unspecified"))
    )
    (net (code "77") (name "DBOE") (class "Default")
      (node (ref "FB505") (pin "2") (pinfunction "2_2") (pintype "unspecified"))
      (node (ref "U105") (pin "13") (pinfunction "OEAB_13") (pintype "unspecified"))
      (node (ref "U105") (pin "2") (pinfunction "OEBA_2") (pintype "unspecified"))
      (node (ref "U106") (pin "13") (pinfunction "OEAB_13") (pintype "unspecified"))
      (node (ref "U106") (pin "2") (pinfunction "OEBA_2") (pintype "unspecified"))
      (node (ref "U107") (pin "13") (pinfunction "OEAB_13") (pintype "unspecified"))
      (node (ref "U107") (pin "2") (pinfunction "OEBA_2") (pintype "unspecified"))
      (node (ref "U108") (pin "13") (pinfunction "OEAB_13") (pintype "unspecified"))
      (node (ref "U108") (pin "2") (pinfunction "OEBA_2") (pintype "unspecified"))
    )
    (net (code "78") (name "DIP_EXT_TERM") (class "Default")
      (node (ref "R212G") (pin "2") (pinfunction "2_2") (pintype "input"))
      (node (ref "SW1") (pin "7") (pinfunction "PIN7_7") (pintype "unspecified"))
      (node (ref "U213") (pin "4") (pinfunction "I1_4") (pintype "unspecified"))
      (node (ref "U310") (pin "16") (pinfunction "PD#_16") (pintype "unspecified"))
      (node (ref "U311") (pin "16") (pinfunction "PD#_16") (pintype "unspecified"))
    )
    (net (code "79") (name "DIP_LONG_SPINUP") (class "Default")
      (node (ref "R212E") (pin "2") (pinfunction "2_2") (pintype "input"))
      (node (ref "SW1") (pin "5") (pinfunction "PIN5_5") (pintype "unspecified"))
      (node (ref "U213") (pin "8") (pinfunction "I3_8") (pintype "unspecified"))
    )
    (net (code "80") (name "DIP_SCSI_ADR0") (class "Default")
      (node (ref "R212A") (pin "2") (pinfunction "2_2") (pintype "input"))
      (node (ref "SW1") (pin "1") (pinfunction "PIN1_1") (pintype "unspecified"))
      (node (ref "U213") (pin "17") (pinfunction "I4_17") (pintype "unspecified"))
    )
    (net (code "81") (name "DIP_SCSI_ADR1") (class "Default")
      (node (ref "R212B") (pin "1") (pinfunction "1_1") (pintype "input"))
      (node (ref "SW1") (pin "2") (pinfunction "PIN2_2") (pintype "unspecified"))
      (node (ref "U213") (pin "15") (pinfunction "I5_15") (pintype "unspecified"))
    )
    (net (code "82") (name "DIP_SCSI_ADR2") (class "Default")
      (node (ref "R212C") (pin "1") (pinfunction "1_1") (pintype "input"))
      (node (ref "SW1") (pin "3") (pinfunction "PIN3_3") (pintype "unspecified"))
      (node (ref "U213") (pin "13") (pinfunction "I6_13") (pintype "unspecified"))
    )
    (net (code "83") (name "DIP_SCSI_FAST") (class "Default")
      (node (ref "R212D") (pin "1") (pinfunction "1_1") (pintype "input"))
      (node (ref "SW1") (pin "4") (pinfunction "PIN4_4") (pintype "unspecified"))
      (node (ref "U213") (pin "11") (pinfunction "I7_11") (pintype "unspecified"))
    )
    (net (code "84") (name "DIP_SCSI_LUNS") (class "Default")
      (node (ref "R212H") (pin "2") (pinfunction "2_2") (pintype "input"))
      (node (ref "SW1") (pin "8") (pinfunction "PIN8_8") (pintype "unspecified"))
      (node (ref "U213") (pin "2") (pinfunction "I0_2") (pintype "unspecified"))
    )
    (net (code "85") (name "DIP_SYNCH_MODE") (class "Default")
      (node (ref "R212F") (pin "2") (pinfunction "2_2") (pintype "input"))
      (node (ref "SW1") (pin "6") (pinfunction "PIN6_6") (pintype "unspecified"))
      (node (ref "U213") (pin "6") (pinfunction "I2_6") (pintype "unspecified"))
    )
    (net (code "86") (name "DP3_ABRT") (class "Default")
      (node (ref "R300P") (pin "1") (pinfunction "1_1") (pintype "input"))
      (node (ref "U300") (pin "52") (pinfunction "DP3_ABRT/_52") (pintype "unspecified"))
    )
    (net (code "87") (name "GND") (class "Default")
      (node (ref "C1") (pin "01") (pinfunction "GND_01") (pintype "bidirectional"))
      (node (ref "C1") (pin "02") (pinfunction "GND_02") (pintype "unspecified"))
      (node (ref "C1") (pin "03") (pinfunction "GND_03") (pintype "output"))
      (node (ref "C1") (pin "04") (pinfunction "GND_04") (pintype "bidirectional"))
      (node (ref "C1") (pin "100") (pinfunction "GND_100") (pintype "bidirectional"))
      (node (ref "C1") (pin "13") (pinfunction "GND_13") (pintype "bidirectional"))
      (node (ref "C1") (pin "25") (pinfunction "GND_25") (pintype "output"))
      (node (ref "C1") (pin "37") (pinfunction "GND_37") (pintype "unspecified"))
      (node (ref "C1") (pin "49") (pinfunction "GND_49") (pintype "unspecified"))
      (node (ref "C1") (pin "61") (pinfunction "GND_61") (pintype "bidirectional"))
      (node (ref "C1") (pin "73") (pinfunction "GND_73") (pintype "unspecified"))
      (node (ref "C1") (pin "85") (pinfunction "GND_85") (pintype "unspecified"))
      (node (ref "C1") (pin "87") (pinfunction "GND_87") (pintype "output"))
      (node (ref "C1") (pin "88") (pinfunction "GND_88") (pintype "bidirectional"))
      (node (ref "C1") (pin "89") (pinfunction "GND_89") (pintype "unspecified"))
      (node (ref "C1") (pin "90") (pinfunction "GND_90") (pintype "bidirectional"))
      (node (ref "C1") (pin "99") (pinfunction "GND_99") (pintype "bidirectional"))
      (node (ref "C10") (pin "2") (pinfunction "2_2") (pintype "input"))
      (node (ref "C100A") (pin "2") (pinfunction "2_2") (pintype "input"))
      (node (ref "C101A") (pin "2") (pinfunction "2_2") (pintype "input"))
      (node (ref "C102A") (pin "2") (pinfunction "2_2") (pintype "input"))
      (node (ref "C103A") (pin "2") (pinfunction "2_2") (pintype "input"))
      (node (ref "C105A") (pin "2") (pinfunction "2_2") (pintype "input"))
      (node (ref "C106A") (pin "1") (pinfunction "1_1") (pintype "input"))
      (node (ref "C107A") (pin "2") (pinfunction "2_2") (pintype "input"))
      (node (ref "C108A") (pin "2") (pinfunction "2_2") (pintype "input"))
      (node (ref "C109A") (pin "2") (pinfunction "2_2") (pintype "input"))
      (node (ref "C11") (pin "2") (pinfunction "2_2") (pintype "input"))
      (node (ref "C12") (pin "2") (pinfunction "2_2") (pintype "input"))
      (node (ref "C13") (pin "2") (pinfunction "2_2") (pintype "input"))
      (node (ref "C1A") (pin "1") (pinfunction "1_1") (pintype "input"))
      (node (ref "C1B") (pin "2") (pinfunction "2_2") (pintype "input"))
      (node (ref "C1C") (pin "2") (pinfunction "2_2") (pintype "input"))
      (node (ref "C200A") (pin "1") (pinfunction "1_1") (pintype "input"))
      (node (ref "C201A") (pin "2") (pinfunction "2_2") (pintype "input"))
      (node (ref "C202A") (pin "2") (pinfunction "2_2") (pintype "input"))
      (node (ref "C203A") (pin "2") (pinfunction "2_2") (pintype "input"))
      (node (ref "C204A") (pin "1") (pinfunction "1_1") (pintype "input"))
      (node (ref "C205A") (pin "2") (pinfunction "2_2") (pintype "input"))
      (node (ref "C206A") (pin "1") (pinfunction "1_1") (pintype "input"))
      (node (ref "C207A") (pin "2") (pinfunction "2_2") (pintype "input"))
      (node (ref "C212A") (pin "2") (pinfunction "2_2") (pintype "input"))
      (node (ref "C300A") (pin "2") (pinfunction "2_2") (pintype "input"))
      (node (ref "C300B") (pin "2") (pinfunction "2_2") (pintype "input"))
      (node (ref "C300C") (pin "2") (pinfunction "2_2") (pintype "input"))
      (node (ref "C300D") (pin "1") (pinfunction "1_1") (pintype "input"))
      (node (ref "C300E") (pin "2") (pinfunction "2_2") (pintype "input"))
      (node (ref "C300F") (pin "2") (pinfunction "2_2") (pintype "input"))
      (node (ref "C300G") (pin "2") (pinfunction "2_2") (pintype "input"))
      (node (ref "C300H") (pin "1") (pinfunction "1_1") (pintype "input"))
      (node (ref "C300I") (pin "2") (pinfunction "2_2") (pintype "input"))
      (node (ref "C301A") (pin "1") (pinfunction "1_1") (pintype "input"))
      (node (ref "C302A") (pin "2") (pinfunction "2_2") (pintype "input"))
      (node (ref "C303A") (pin "1") (pinfunction "1_1") (pintype "input"))
      (node (ref "C304A") (pin "2") (pinfunction "2_2") (pintype "input"))
      (node (ref "C305A") (pin "2") (pinfunction "2_2") (pintype "input"))
      (node (ref "C306A") (pin "2") (pinfunction "2_2") (pintype "input"))
      (node (ref "C307A") (pin "1") (pinfunction "1_1") (pintype "input"))
      (node (ref "C310A") (pin "1") (pinfunction "1_1") (pintype "unspecified"))
      (node (ref "C310B") (pin "1") (pinfunction "1_1") (pintype "unspecified"))
      (node (ref "C310C") (pin "1") (pinfunction "1_1") (pintype "unspecified"))
      (node (ref "C310D") (pin "1") (pinfunction "1_1") (pintype "unspecified"))
      (node (ref "C310E") (pin "1") (pinfunction "1_1") (pintype "unspecified"))
      (node (ref "C310F") (pin "1") (pinfunction "1_1") (pintype "unspecified"))
      (node (ref "C310G") (pin "1") (pinfunction "1_1") (pintype "unspecified"))
      (node (ref "C310H") (pin "1") (pinfunction "1_1") (pintype "unspecified"))
      (node (ref "C310I") (pin "1") (pinfunction "1_1") (pintype "unspecified"))
      (node (ref "C310J") (pin "2") (pinfunction "2_2") (pintype "unspecified"))
      (node (ref "C310K") (pin "2") (pinfunction "2_2") (pintype "unspecified"))
      (node (ref "C310L") (pin "2") (pinfunction "2_2") (pintype "unspecified"))
      (node (ref "C310M") (pin "2") (pinfunction "2_2") (pintype "unspecified"))
      (node (ref "C310N") (pin "2") (pinfunction "2_2") (pintype "unspecified"))
      (node (ref "C310O") (pin "2") (pinfunction "2_2") (pintype "unspecified"))
      (node (ref "C310P") (pin "2") (pinfunction "2_2") (pintype "unspecified"))
      (node (ref "C310Q") (pin "2") (pinfunction "2_2") (pintype "unspecified"))
      (node (ref "C310R") (pin "2") (pinfunction "2_2") (pintype "unspecified"))
      (node (ref "C350A") (pin "2") (pinfunction "2_2") (pintype "unspecified"))
      (node (ref "C350B") (pin "1") (pinfunction "1_1") (pintype "input"))
      (node (ref "C351A") (pin "2") (pinfunction "2_2") (pintype "unspecified"))
      (node (ref "C351B") (pin "2") (pinfunction "2_2") (pintype "input"))
      (node (ref "CN2") (pin "2") (pinfunction "2_2") (pintype "unspecified"))
      (node (ref "CN2") (pin "3") (pinfunction "3_3") (pintype "unspecified"))
      (node (ref "CN309") (pin "1") (pinfunction "1_1") (pintype "input"))
      (node (ref "CN309") (pin "11") (pinfunction "11_11") (pintype "input"))
      (node (ref "CN309") (pin "13") (pinfunction "13_13") (pintype "input"))
      (node (ref "CN309") (pin "15") (pinfunction "15_15") (pintype "input"))
      (node (ref "CN309") (pin "17") (pinfunction "17_17") (pintype "input"))
      (node (ref "CN309") (pin "19") (pinfunction "19_19") (pintype "input"))
      (node (ref "CN309") (pin "20") (pinfunction "20_20") (pintype "input"))
      (node (ref "CN309") (pin "21") (pinfunction "21_21") (pintype "input"))
      (node (ref "CN309") (pin "22") (pinfunction "22_22") (pintype "input"))
      (node (ref "CN309") (pin "23") (pinfunction "23_23") (pintype "input"))
      (node (ref "CN309") (pin "24") (pinfunction "24_24") (pintype "input"))
      (node (ref "CN309") (pin "27") (pinfunction "27_27") (pintype "input"))
      (node (ref "CN309") (pin "28") (pinfunction "28_28") (pintype "input"))
      (node (ref "CN309") (pin "29") (pinfunction "29_29") (pintype "input"))
      (node (ref "CN309") (pin "3") (pinfunction "3_3") (pintype "input"))
      (node (ref "CN309") (pin "30") (pinfunction "30_30") (pintype "input"))
      (node (ref "CN309") (pin "31") (pinfunction "31_31") (pintype "input"))
      (node (ref "CN309") (pin "33") (pinfunction "33_33") (pintype "input"))
      (node (ref "CN309") (pin "35") (pinfunction "35_35") (pintype "input"))
      (node (ref "CN309") (pin "37") (pinfunction "37_37") (pintype "input"))
      (node (ref "CN309") (pin "39") (pinfunction "39_39") (pintype "input"))
      (node (ref "CN309") (pin "41") (pinfunction "41_41") (pintype "input"))
      (node (ref "CN309") (pin "43") (pinfunction "43_43") (pintype "input"))
      (node (ref "CN309") (pin "45") (pinfunction "45_45") (pintype "input"))
      (node (ref "CN309") (pin "47") (pinfunction "47_47") (pintype "input"))
      (node (ref "CN309") (pin "49") (pinfunction "49_49") (pintype "input"))
      (node (ref "CN309") (pin "5") (pinfunction "5_5") (pintype "input"))
      (node (ref "CN309") (pin "7") (pinfunction "7_7") (pintype "input"))
      (node (ref "CN309") (pin "9") (pinfunction "9_9") (pintype "input"))
      (node (ref "CN310") (pin "1") (pinfunction "1_1") (pintype "unspecified"))
      (node (ref "CN310") (pin "10") (pinfunction "10_10") (pintype "unspecified"))
      (node (ref "CN310") (pin "11") (pinfunction "11_11") (pintype "unspecified"))
      (node (ref "CN310") (pin "15") (pinfunction "15_15") (pintype "unspecified"))
      (node (ref "CN310") (pin "16") (pinfunction "16_16") (pintype "unspecified"))
      (node (ref "CN310") (pin "17") (pinfunction "17_17") (pintype "unspecified"))
      (node (ref "CN310") (pin "18") (pinfunction "18_18") (pintype "unspecified"))
      (node (ref "CN310") (pin "19") (pinfunction "19_19") (pintype "unspecified"))
      (node (ref "CN310") (pin "2") (pinfunction "2_2") (pintype "unspecified"))
      (node (ref "CN310") (pin "20") (pinfunction "20_20") (pintype "unspecified"))
      (node (ref "CN310") (pin "21") (pinfunction "21_21") (pintype "unspecified"))
      (node (ref "CN310") (pin "22") (pinfunction "22_22") (pintype "unspecified"))
      (node (ref "CN310") (pin "23") (pinfunction "23_23") (pintype "unspecified"))
      (node (ref "CN310") (pin "24") (pinfunction "24_24") (pintype "unspecified"))
      (node (ref "CN310") (pin "25") (pinfunction "25_25") (pintype "unspecified"))
      (node (ref "CN310") (pin "3") (pinfunction "3_3") (pintype "unspecified"))
      (node (ref "CN310") (pin "35") (pinfunction "35_35") (pintype "unspecified"))
      (node (ref "CN310") (pin "36") (pinfunction "36_36") (pintype "unspecified"))
      (node (ref "CN310") (pin "4") (pinfunction "4_4") (pintype "unspecified"))
      (node (ref "CN310") (pin "40") (pinfunction "40_40") (pintype "unspecified"))
      (node (ref "CN310") (pin "42") (pinfunction "42_42") (pintype "unspecified"))
      (node (ref "CN310") (pin "5") (pinfunction "5_5") (pintype "unspecified"))
      (node (ref "CN310") (pin "6") (pinfunction "6_6") (pintype "unspecified"))
      (node (ref "CN310") (pin "7") (pinfunction "7_7") (pintype "unspecified"))
      (node (ref "CN310") (pin "8") (pinfunction "8_8") (pintype "unspecified"))
      (node (ref "CN310") (pin "9") (pinfunction "9_9") (pintype "unspecified"))
      (node (ref "MH1") (pin "1") (pinfunction "1_1") (pintype "unspecified"))
      (node (ref "MH2") (pin "1") (pinfunction "1_1") (pintype "unspecified"))
      (node (ref "MH3") (pin "1") (pinfunction "1_1") (pintype "unspecified"))
      (node (ref "MH4") (pin "1") (pinfunction "1_1") (pintype "unspecified"))
      (node (ref "R109H") (pin "1") (pinfunction "1_1") (pintype "input"))
      (node (ref "RP300A") (pin "1") (pinfunction "COM1_1") (pintype "unspecified"))
      (node (ref "RP300B") (pin "1") (pinfunction "COM1_1") (pintype "unspecified"))
      (node (ref "RP300C") (pin "1") (pinfunction "COM1_1") (pintype "unspecified"))
      (node (ref "SW1") (pin "10") (pinfunction "PIN10_10") (pintype "unspecified"))
      (node (ref "SW1") (pin "11") (pinfunction "PIN11_11") (pintype "unspecified"))
      (node (ref "SW1") (pin "12") (pinfunction "PIN12_12") (pintype "unspecified"))
      (node (ref "SW1") (pin "13") (pinfunction "PIN13_13") (pintype "unspecified"))
      (node (ref "SW1") (pin "14") (pinfunction "PIN14_14") (pintype "unspecified"))
      (node (ref "SW1") (pin "15") (pinfunction "PIN15_15") (pintype "unspecified"))
      (node (ref "SW1") (pin "16") (pinfunction "PIN16_16") (pintype "unspecified"))
      (node (ref "SW1") (pin "9") (pinfunction "PIN9_9") (pintype "unspecified"))
      (node (ref "U100") (pin "12") (pinfunction "GND_12") (pintype "passive"))
      (node (ref "U100") (pin "14") (pinfunction "LEAB_14") (pintype "unspecified"))
      (node (ref "U101") (pin "12") (pinfunction "GND_12") (pintype "passive"))
      (node (ref "U101") (pin "14") (pinfunction "LEAB_14") (pintype "unspecified"))
      (node (ref "U102") (pin "12") (pinfunction "GND_12") (pintype "passive"))
      (node (ref "U102") (pin "14") (pinfunction "LEAB_14") (pintype "unspecified"))
      (node (ref "U103") (pin "10") (pinfunction "GND_10") (pintype "unspecified"))
      (node (ref "U105") (pin "12") (pinfunction "GND_12") (pintype "passive"))
      (node (ref "U106") (pin "12") (pinfunction "GND_12") (pintype "passive"))
      (node (ref "U107") (pin "12") (pinfunction "GND_12") (pintype "passive"))
      (node (ref "U108") (pin "12") (pinfunction "GND_12") (pintype "passive"))
      (node (ref "U109") (pin "10") (pinfunction "GND_10") (pintype "unspecified"))
      (node (ref "U200") (pin "10") (pinfunction "GND_10") (pintype "unspecified"))
      (node (ref "U201") (pin "1") (pinfunction "IA=B_1") (pintype "unspecified"))
      (node (ref "U201") (pin "10") (pinfunction "GND_10") (pintype "unspecified"))
      (node (ref "U202") (pin "14") (pinfunction "GND_14") (pintype "unspecified"))
      (node (ref "U203") (pin "14") (pinfunction "GND_14") (pintype "unspecified"))
      (node (ref "U204") (pin "10") (pinfunction "GND_10") (pintype "unspecified"))
      (node (ref "U205") (pin "14") (pinfunction "GND_14") (pintype "unspecified"))
      (node (ref "U206") (pin "14") (pinfunction "GND_14") (pintype "output"))
      (node (ref "U206") (pin "20") (pinfunction "CE#_20") (pintype "output"))
      (node (ref "U207") (pin "14") (pinfunction "GND_14") (pintype "unspecified"))
      (node (ref "U213") (pin "10") (pinfunction "GND_10") (pintype "unspecified"))
      (node (ref "U300") (pin "109") (pinfunction "Vss_109") (pintype "unspecified"))
      (node (ref "U300") (pin "113") (pinfunction "Vss_113") (pintype "unspecified"))
      (node (ref "U300") (pin "118") (pinfunction "Vss_118") (pintype "unspecified"))
      (node (ref "U300") (pin "123") (pinfunction "Vss_123") (pintype "unspecified"))
      (node (ref "U300") (pin "128") (pinfunction "Vss_128") (pintype "unspecified"))
      (node (ref "U300") (pin "136") (pinfunction "Vss_136") (pintype "unspecified"))
      (node (ref "U300") (pin "143") (pinfunction "Vss_143") (pintype "unspecified"))
      (node (ref "U300") (pin "149") (pinfunction "Vss_149") (pintype "unspecified"))
      (node (ref "U300") (pin "15") (pinfunction "Vss_15") (pintype "unspecified"))
      (node (ref "U300") (pin "156") (pinfunction "Vss_156") (pintype "unspecified"))
      (node (ref "U300") (pin "2") (pinfunction "Vss_2") (pintype "unspecified"))
      (node (ref "U300") (pin "22") (pinfunction "Vss_22") (pintype "unspecified"))
      (node (ref "U300") (pin "31") (pinfunction "Vss_31") (pintype "unspecified"))
      (node (ref "U300") (pin "46") (pinfunction "Vss_46") (pintype "unspecified"))
      (node (ref "U300") (pin "54") (pinfunction "Vss_54") (pintype "unspecified"))
      (node (ref "U300") (pin "61") (pinfunction "Vss_61") (pintype "unspecified"))
      (node (ref "U300") (pin "69") (pinfunction "Vss_69") (pintype "unspecified"))
      (node (ref "U300") (pin "75") (pinfunction "Vss_75") (pintype "unspecified"))
      (node (ref "U300") (pin "82") (pinfunction "Vss_82") (pintype "unspecified"))
      (node (ref "U300") (pin "9") (pinfunction "Vss_9") (pintype "unspecified"))
      (node (ref "U300") (pin "96") (pinfunction "Vss_96") (pintype "unspecified"))
      (node (ref "U301") (pin "7") (pinfunction "Gnd_7") (pintype "unspecified"))
      (node (ref "U302") (pin "7") (pinfunction "GND_7") (pintype "unspecified"))
      (node (ref "U303") (pin "14") (pinfunction "GND_14") (pintype "unspecified"))
      (node (ref "U304") (pin "14") (pinfunction "GND_14") (pintype "unspecified"))
      (node (ref "U305") (pin "14") (pinfunction "GND_14") (pintype "unspecified"))
      (node (ref "U306") (pin "14") (pinfunction "GND_14") (pintype "unspecified"))
      (node (ref "U307") (pin "11") (pinfunction "5A_11") (pintype "unspecified"))
      (node (ref "U307") (pin "13") (pinfunction "6A_13") (pintype "unspecified"))
      (node (ref "U307") (pin "7") (pinfunction "GND_7") (pintype "unspecified"))
      (node (ref "U310") (pin "8") (pinfunction "GND_8") (pintype "passive"))
      (node (ref "U311") (pin "8") (pinfunction "GND_8") (pintype "passive"))
    )
    (net (code "88") (name "IORST") (class "Default")
      (node (ref "R307A") (pin "1") (pinfunction "1_1") (pintype "input"))
      (node (ref "U202") (pin "19") (pinfunction "IOQ_19") (pintype "unspecified"))
      (node (ref "U203") (pin "27") (pinfunction "IOQ_27") (pintype "unspecified"))
      (node (ref "U207") (pin "9") (pinfunction "I_9") (pintype "unspecified"))
      (node (ref "U300") (pin "94") (pinfunction "RESET/_94") (pintype "unspecified"))
      (node (ref "U303") (pin "11") (pinfunction "I_11") (pintype "unspecified"))
      (node (ref "U306") (pin "12") (pinfunction "I_12") (pintype "unspecified"))
      (node (ref "U307") (pin "8") (pinfunction "4Y_8") (pintype "unspecified"))
    )
    (net (code "89") (name "LED") (class "Default")
      (node (ref "R398") (pin "2") (pinfunction "2_2") (pintype "unspecified"))
      (node (ref "U307") (pin "2") (pinfunction "1Y_2") (pintype "unspecified"))
      (node (ref "U307") (pin "4") (pinfunction "2Y_4") (pintype "unspecified"))
    )
    (net (code "90") (name "LEDR") (class "Default")
      (node (ref "CN308") (pin "1") (pinfunction "1_1") (pintype "input"))
      (node (ref "CN308") (pin "3") (pinfunction "3_3") (pintype "input"))
      (node (ref "CN351") (pin "1") (pinfunction "1_1") (pintype "input"))
      (node (ref "CN351") (pin "3") (pinfunction "3_3") (pintype "input"))
      (node (ref "R398") (pin "1") (pinfunction "1_1") (pintype "unspecified"))
    )
    (net (code "91") (name "M24") (class "Default")
      (node (ref "R200H") (pin "1") (pinfunction "1_1") (pintype "input"))
      (node (ref "U200") (pin "19") (pinfunction "Q7_19") (pintype "unspecified"))
      (node (ref "U201") (pin "18") (pinfunction "B7_18") (pintype "unspecified"))
    )
    (net (code "92") (name "M25") (class "Default")
      (node (ref "R200G") (pin "1") (pinfunction "1_1") (pintype "input"))
      (node (ref "U200") (pin "16") (pinfunction "Q6_16") (pintype "unspecified"))
      (node (ref "U201") (pin "16") (pinfunction "B6_16") (pintype "unspecified"))
    )
    (net (code "93") (name "M26") (class "Default")
      (node (ref "R200F") (pin "1") (pinfunction "1_1") (pintype "input"))
      (node (ref "U200") (pin "15") (pinfunction "Q5_15") (pintype "unspecified"))
      (node (ref "U201") (pin "14") (pinfunction "B5_14") (pintype "unspecified"))
    )
    (net (code "94") (name "M27") (class "Default")
      (node (ref "R200E") (pin "1") (pinfunction "1_1") (pintype "input"))
      (node (ref "U200") (pin "12") (pinfunction "Q4_12") (pintype "unspecified"))
      (node (ref "U201") (pin "12") (pinfunction "B4_12") (pintype "unspecified"))
    )
    (net (code "95") (name "M28") (class "Default")
      (node (ref "R200D") (pin "1") (pinfunction "1_1") (pintype "input"))
      (node (ref "U200") (pin "9") (pinfunction "Q3_9") (pintype "unspecified"))
      (node (ref "U201") (pin "9") (pinfunction "B3_9") (pintype "unspecified"))
    )
    (net (code "96") (name "M29") (class "Default")
      (node (ref "R200C") (pin "1") (pinfunction "1_1") (pintype "input"))
      (node (ref "U200") (pin "6") (pinfunction "Q2_6") (pintype "unspecified"))
      (node (ref "U201") (pin "7") (pinfunction "B2_7") (pintype "unspecified"))
    )
    (net (code "97") (name "M30") (class "Default")
      (node (ref "R200B") (pin "1") (pinfunction "1_1") (pintype "input"))
      (node (ref "U200") (pin "5") (pinfunction "Q1_5") (pintype "unspecified"))
      (node (ref "U201") (pin "5") (pinfunction "B1_5") (pintype "unspecified"))
    )
    (net (code "98") (name "M31") (class "Default")
      (node (ref "R200A") (pin "1") (pinfunction "1_1") (pintype "input"))
      (node (ref "U200") (pin "2") (pinfunction "Q0_2") (pintype "unspecified"))
      (node (ref "U201") (pin "3") (pinfunction "B0_3") (pintype "unspecified"))
    )
    (net (code "99") (name "MASTER") (class "Default")
      (node (ref "FB502") (pin "1") (pinfunction "1_1") (pintype "unspecified"))
      (node (ref "U100") (pin "11") (pinfunction "CEAB_11") (pintype "unspecified"))
      (node (ref "U101") (pin "11") (pinfunction "CEAB_11") (pintype "unspecified"))
      (node (ref "U102") (pin "11") (pinfunction "CEAB_11") (pintype "unspecified"))
      (node (ref "U205") (pin "18") (pinfunction "IOQ_18") (pintype "unspecified"))
      (node (ref "U303") (pin "3") (pinfunction "I_3") (pintype "unspecified"))
    )
    (net (code "100") (name "MATCH") (class "Default")
      (node (ref "U201") (pin "19") (pinfunction "OA=B_19") (pintype "unspecified"))
      (node (ref "U202") (pin "2") (pinfunction "CLK/I_2") (pintype "unspecified"))
    )
    (net (code "101") (name "NCR_INT") (class "Default")
      (node (ref "U207") (pin "10") (pinfunction "I_10") (pintype "unspecified"))
      (node (ref "U300") (pin "105") (pinfunction "IRQ/_105") (pintype "unspecified"))
    )
    (net (code "102") (name "Net-(C310A-Pad2)") (class "Default")
      (node (ref "C310A") (pin "2") (pinfunction "2_2") (pintype "unspecified"))
      (node (ref "CN310") (pin "50") (pinfunction "50_50") (pintype "unspecified"))
      (node (ref "FB310A") (pin "2") (pinfunction "2_2") (pintype "unspecified"))
    )
    (net (code "103") (name "Net-(C310B-Pad2)") (class "Default")
      (node (ref "C310B") (pin "2") (pinfunction "2_2") (pintype "unspecified"))
      (node (ref "CN310") (pin "49") (pinfunction "49_49") (pintype "unspecified"))
      (node (ref "FB310B") (pin "2") (pinfunction "2_2") (pintype "unspecified"))
    )
    (net (code "104") (name "Net-(C310C-Pad2)") (class "Default")
      (node (ref "C310C") (pin "2") (pinfunction "2_2") (pintype "unspecified"))
      (node (ref "CN310") (pin "48") (pinfunction "48_48") (pintype "unspecified"))
      (node (ref "FB310C") (pin "2") (pinfunction "2_2") (pintype "unspecified"))
    )
    (net (code "105") (name "Net-(C310D-Pad2)") (class "Default")
      (node (ref "C310D") (pin "2") (pinfunction "2_2") (pintype "unspecified"))
      (node (ref "CN310") (pin "47") (pinfunction "47_47") (pintype "unspecified"))
      (node (ref "FB310D") (pin "2") (pinfunction "2_2") (pintype "unspecified"))
    )
    (net (code "106") (name "Net-(C310E-Pad2)") (class "Default")
      (node (ref "C310E") (pin "2") (pinfunction "2_2") (pintype "unspecified"))
      (node (ref "CN310") (pin "46") (pinfunction "46_46") (pintype "unspecified"))
      (node (ref "FB310E") (pin "2") (pinfunction "2_2") (pintype "unspecified"))
    )
    (net (code "107") (name "Net-(C310F-Pad2)") (class "Default")
      (node (ref "C310F") (pin "2") (pinfunction "2_2") (pintype "unspecified"))
      (node (ref "CN310") (pin "45") (pinfunction "45_45") (pintype "unspecified"))
      (node (ref "FB310F") (pin "2") (pinfunction "2_2") (pintype "unspecified"))
    )
    (net (code "108") (name "Net-(C310G-Pad2)") (class "Default")
      (node (ref "C310G") (pin "2") (pinfunction "2_2") (pintype "unspecified"))
      (node (ref "CN310") (pin "44") (pinfunction "44_44") (pintype "unspecified"))
      (node (ref "FB310G") (pin "2") (pinfunction "2_2") (pintype "unspecified"))
    )
    (net (code "109") (name "Net-(C310H-Pad2)") (class "Default")
      (node (ref "C310H") (pin "2") (pinfunction "2_2") (pintype "unspecified"))
      (node (ref "CN310") (pin "43") (pinfunction "43_43") (pintype "unspecified"))
      (node (ref "FB310H") (pin "2") (pinfunction "2_2") (pintype "unspecified"))
    )
    (net (code "110") (name "Net-(C310I-Pad2)") (class "Default")
      (node (ref "C310I") (pin "2") (pinfunction "2_2") (pintype "unspecified"))
      (node (ref "CN310") (pin "41") (pinfunction "41_41") (pintype "unspecified"))
      (node (ref "FB310I") (pin "2") (pinfunction "2_2") (pintype "unspecified"))
    )
    (net (code "111") (name "Net-(C310J-Pad1)") (class "Default")
      (node (ref "C310J") (pin "1") (pinfunction "1_1") (pintype "unspecified"))
      (node (ref "CN310") (pin "34") (pinfunction "34_34") (pintype "unspecified"))
      (node (ref "FB310J") (pin "2") (pinfunction "2_2") (pintype "unspecified"))
    )
    (net (code "112") (name "Net-(C310K-Pad1)") (class "Default")
      (node (ref "C310K") (pin "1") (pinfunction "1_1") (pintype "unspecified"))
      (node (ref "CN310") (pin "26") (pinfunction "26_26") (pintype "unspecified"))
      (node (ref "FB310K") (pin "2") (pinfunction "2_2") (pintype "unspecified"))
    )
    (net (code "113") (name "Net-(C310L-Pad1)") (class "Default")
      (node (ref "C310L") (pin "1") (pinfunction "1_1") (pintype "unspecified"))
      (node (ref "CN310") (pin "27") (pinfunction "27_27") (pintype "unspecified"))
      (node (ref "FB310L") (pin "2") (pinfunction "2_2") (pintype "unspecified"))
    )
    (net (code "114") (name "Net-(C310M-Pad1)") (class "Default")
      (node (ref "C310M") (pin "1") (pinfunction "1_1") (pintype "unspecified"))
      (node (ref "CN310") (pin "28") (pinfunction "28_28") (pintype "unspecified"))
      (node (ref "FB310M") (pin "2") (pinfunction "2_2") (pintype "unspecified"))
    )
    (net (code "115") (name "Net-(C310N-Pad1)") (class "Default")
      (node (ref "C310N") (pin "1") (pinfunction "1_1") (pintype "unspecified"))
      (node (ref "CN310") (pin "29") (pinfunction "29_29") (pintype "unspecified"))
      (node (ref "FB310N") (pin "2") (pinfunction "2_2") (pintype "unspecified"))
    )
    (net (code "116") (name "Net-(C310O-Pad1)") (class "Default")
      (node (ref "C310O") (pin "1") (pinfunction "1_1") (pintype "unspecified"))
      (node (ref "CN310") (pin "30") (pinfunction "30_30") (pintype "unspecified"))
      (node (ref "FB310O") (pin "2") (pinfunction "2_2") (pintype "unspecified"))
    )
    (net (code "117") (name "Net-(C310P-Pad1)") (class "Default")
      (node (ref "C310P") (pin "1") (pinfunction "1_1") (pintype "unspecified"))
      (node (ref "CN310") (pin "31") (pinfunction "31_31") (pintype "unspecified"))
      (node (ref "FB310P") (pin "2") (pinfunction "2_2") (pintype "unspecified"))
    )
    (net (code "118") (name "Net-(C310Q-Pad1)") (class "Default")
      (node (ref "C310Q") (pin "1") (pinfunction "1_1") (pintype "unspecified"))
      (node (ref "CN310") (pin "32") (pinfunction "32_32") (pintype "unspecified"))
      (node (ref "FB310Q") (pin "2") (pinfunction "2_2") (pintype "unspecified"))
    )
    (net (code "119") (name "Net-(C310R-Pad1)") (class "Default")
      (node (ref "C310R") (pin "1") (pinfunction "1_1") (pintype "unspecified"))
      (node (ref "CN310") (pin "33") (pinfunction "33_33") (pintype "unspecified"))
      (node (ref "FB310R") (pin "2") (pinfunction "2_2") (pintype "unspecified"))
    )
    (net (code "120") (name "Net-(CN309-Pad2)") (class "Default")
      (node (ref "CN309") (pin "2") (pinfunction "2_2") (pintype "input"))
      (node (ref "FB311A") (pin "1") (pinfunction "1_1") (pintype "unspecified"))
    )
    (net (code "121") (name "Net-(CN309-Pad4)") (class "Default")
      (node (ref "CN309") (pin "4") (pinfunction "4_4") (pintype "input"))
      (node (ref "FB311B") (pin "1") (pinfunction "1_1") (pintype "unspecified"))
    )
    (net (code "122") (name "Net-(CN309-Pad6)") (class "Default")
      (node (ref "CN309") (pin "6") (pinfunction "6_6") (pintype "input"))
      (node (ref "FB311C") (pin "1") (pinfunction "1_1") (pintype "unspecified"))
    )
    (net (code "123") (name "Net-(CN309-Pad8)") (class "Default")
      (node (ref "CN309") (pin "8") (pinfunction "8_8") (pintype "input"))
      (node (ref "FB311D") (pin "1") (pinfunction "1_1") (pintype "unspecified"))
    )
    (net (code "124") (name "Net-(CN309-Pad10)") (class "Default")
      (node (ref "CN309") (pin "10") (pinfunction "10_10") (pintype "input"))
      (node (ref "FB311E") (pin "1") (pinfunction "1_1") (pintype "unspecified"))
    )
    (net (code "125") (name "Net-(CN309-Pad12)") (class "Default")
      (node (ref "CN309") (pin "12") (pinfunction "12_12") (pintype "input"))
      (node (ref "FB311F") (pin "1") (pinfunction "1_1") (pintype "unspecified"))
    )
    (net (code "126") (name "Net-(CN309-Pad14)") (class "Default")
      (node (ref "CN309") (pin "14") (pinfunction "14_14") (pintype "input"))
      (node (ref "FB311G") (pin "1") (pinfunction "1_1") (pintype "unspecified"))
    )
    (net (code "127") (name "Net-(CN309-Pad16)") (class "Default")
      (node (ref "CN309") (pin "16") (pinfunction "16_16") (pintype "input"))
      (node (ref "FB311H") (pin "1") (pinfunction "1_1") (pintype "unspecified"))
    )
    (net (code "128") (name "Net-(CN309-Pad18)") (class "Default")
      (node (ref "CN309") (pin "18") (pinfunction "18_18") (pintype "input"))
      (node (ref "FB311I") (pin "1") (pinfunction "1_1") (pintype "unspecified"))
    )
    (net (code "129") (name "Net-(CN309-Pad32)") (class "Default")
      (node (ref "CN309") (pin "32") (pinfunction "32_32") (pintype "input"))
      (node (ref "FB311J") (pin "1") (pinfunction "1_1") (pintype "unspecified"))
    )
    (net (code "130") (name "Net-(CN309-Pad38)") (class "Default")
      (node (ref "CN309") (pin "38") (pinfunction "38_38") (pintype "input"))
      (node (ref "FB311Q") (pin "1") (pinfunction "1_1") (pintype "unspecified"))
    )
    (net (code "131") (name "Net-(CN309-Pad40)") (class "Default")
      (node (ref "CN309") (pin "40") (pinfunction "40_40") (pintype "input"))
      (node (ref "FB311P") (pin "1") (pinfunction "1_1") (pintype "unspecified"))
    )
    (net (code "132") (name "Net-(CN309-Pad42)") (class "Default")
      (node (ref "CN309") (pin "42") (pinfunction "42_42") (pintype "input"))
      (node (ref "FB311O") (pin "1") (pinfunction "1_1") (pintype "unspecified"))
    )
    (net (code "133") (name "Net-(CN309-Pad44)") (class "Default")
      (node (ref "CN309") (pin "44") (pinfunction "44_44") (pintype "input"))
      (node (ref "FB311N") (pin "1") (pinfunction "1_1") (pintype "unspecified"))
    )
    (net (code "134") (name "Net-(CN309-Pad46)") (class "Default")
      (node (ref "CN309") (pin "46") (pinfunction "46_46") (pintype "input"))
      (node (ref "FB311M") (pin "1") (pinfunction "1_1") (pintype "unspecified"))
    )
    (net (code "135") (name "Net-(CN309-Pad48)") (class "Default")
      (node (ref "CN309") (pin "48") (pinfunction "48_48") (pintype "input"))
      (node (ref "FB311L") (pin "1") (pinfunction "1_1") (pintype "unspecified"))
    )
    (net (code "136") (name "Net-(CN309-Pad50)") (class "Default")
      (node (ref "CN309") (pin "50") (pinfunction "50_50") (pintype "input"))
      (node (ref "FB311K") (pin "1") (pinfunction "1_1") (pintype "unspecified"))
    )
    (net (code "137") (name "Net-(D309A-C)") (class "Default")
      (node (ref "D309A") (pin "1") (pinfunction "C_1") (pintype "unspecified"))
      (node (ref "F309A") (pin "1") (pinfunction "1_1") (pintype "unspecified"))
      (node (ref "F309B") (pin "1") (pinfunction "1_1") (pintype "unspecified"))
    )
    (net (code "138") (name "Net-(FB500-Pad1)") (class "Default")
      (node (ref "FB500") (pin "1") (pinfunction "1_1") (pintype "unspecified"))
      (node (ref "U305") (pin "19") (pinfunction "IOQ_19") (pintype "unspecified"))
    )
    (net (code "139") (name "Net-(FB501-Pad1)") (class "Default")
      (node (ref "FB501") (pin "1") (pinfunction "1_1") (pintype "unspecified"))
      (node (ref "U306") (pin "21") (pinfunction "IOQ_21") (pintype "unspecified"))
    )
    (net (code "140") (name "Net-(FB504-Pad1)") (class "Default")
      (node (ref "FB504") (pin "1") (pinfunction "1_1") (pintype "unspecified"))
      (node (ref "U205") (pin "23") (pinfunction "IOQ_23") (pintype "unspecified"))
    )
    (net (code "141") (name "Net-(FB505-Pad1)") (class "Default")
      (node (ref "FB505") (pin "1") (pinfunction "1_1") (pintype "unspecified"))
      (node (ref "U205") (pin "25") (pinfunction "IOQ_25") (pintype "unspecified"))
    )
    (net (code "142") (name "Net-(U109-B4)") (class "Default")
      (node (ref "FB507") (pin "1") (pinfunction "1_1") (pintype "unspecified"))
      (node (ref "U109") (pin "14") (pinfunction "B4_14") (pintype "unspecified"))
    )
    (net (code "143") (name "Net-(U109-B5)") (class "Default")
      (node (ref "FB508") (pin "1") (pinfunction "1_1") (pintype "unspecified"))
      (node (ref "U109") (pin "13") (pinfunction "B5_13") (pintype "unspecified"))
    )
    (net (code "144") (name "Net-(U300-BR{slash})") (class "Default")
      (node (ref "FB503") (pin "1") (pinfunction "1_1") (pintype "unspecified"))
      (node (ref "U300") (pin "101") (pinfunction "BR/_101") (pintype "unspecified"))
    )
    (net (code "145") (name "Net-(U300-DP0)") (class "Default")
      (node (ref "R300M") (pin "2") (pinfunction "2_2") (pintype "input"))
      (node (ref "U300") (pin "86") (pinfunction "DP0_86") (pintype "unspecified"))
    )
    (net (code "146") (name "Net-(U300-DP1)") (class "Default")
      (node (ref "R300N") (pin "1") (pinfunction "1_1") (pintype "input"))
      (node (ref "U300") (pin "74") (pinfunction "DP1_74") (pintype "unspecified"))
    )
    (net (code "147") (name "Net-(U300-DP2)") (class "Default")
      (node (ref "R300O") (pin "1") (pinfunction "1_1") (pintype "input"))
      (node (ref "U300") (pin "63") (pinfunction "DP2_63") (pintype "unspecified"))
    )
    (net (code "148") (name "Net-(U300-MASTER{slash})") (class "Default")
      (node (ref "FB502") (pin "2") (pinfunction "2_2") (pintype "unspecified"))
      (node (ref "U300") (pin "38") (pinfunction "MASTER/_38") (pintype "unspecified"))
    )
    (net (code "149") (name "Net-(U300-R_W{slash})") (class "Default")
      (node (ref "FB506") (pin "2") (pinfunction "2_2") (pintype "unspecified"))
      (node (ref "U300") (pin "32") (pinfunction "R_W/_32") (pintype "unspecified"))
    )
    (net (code "150") (name "Net-(U301-Out)") (class "Default")
      (node (ref "R301A") (pin "2") (pinfunction "2_2") (pintype "input"))
      (node (ref "U301") (pin "8") (pinfunction "Out_8") (pintype "unspecified"))
    )
    (net (code "151") (name "Net-(U302-Q0#)") (class "Default")
      (node (ref "R302A") (pin "2") (pinfunction "2_2") (pintype "input"))
      (node (ref "U302") (pin "6") (pinfunction "Q0#_6") (pintype "unspecified"))
    )
    (net (code "152") (name "Net-(U302-Q0)") (class "Default")
      (node (ref "R302B") (pin "2") (pinfunction "2_2") (pintype "input"))
      (node (ref "U302") (pin "5") (pinfunction "Q0_5") (pintype "unspecified"))
    )
    (net (code "153") (name "Net-(U310-VREF1)") (class "Default")
      (node (ref "C350A") (pin "1") (pinfunction "1_1") (pintype "unspecified"))
      (node (ref "C350B") (pin "2") (pinfunction "2_2") (pintype "input"))
      (node (ref "U310") (pin "15") (pinfunction "VREF2_15") (pintype "passive"))
      (node (ref "U310") (pin "7") (pinfunction "VREF1_7") (pintype "passive"))
    )
    (net (code "154") (name "Net-(U311-VREF1)") (class "Default")
      (node (ref "C351A") (pin "1") (pinfunction "1_1") (pintype "unspecified"))
      (node (ref "C351B") (pin "1") (pinfunction "1_1") (pintype "input"))
      (node (ref "U311") (pin "15") (pinfunction "VREF2_15") (pintype "passive"))
      (node (ref "U311") (pin "7") (pinfunction "VREF1_7") (pintype "passive"))
    )
    (net (code "155") (name "Net-(U400-VREF1)") (class "Default")
      (node (ref "C400A") (pin "1") (pinfunction "1_1") (pintype "unspecified"))
      (node (ref "C400B") (pin "2") (pinfunction "2_2") (pintype "input"))
      (node (ref "U400") (pin "15") (pinfunction "VREF2_15") (pintype "passive"))
      (node (ref "U400") (pin "7") (pinfunction "VREF1_7") (pintype "passive"))
    )
    (net (code "156") (name "Net-(U401-VREF1)") (class "Default")
      (node (ref "C401A") (pin "1") (pinfunction "1_1") (pintype "unspecified"))
      (node (ref "C401B") (pin "2") (pinfunction "2_2") (pintype "input"))
      (node (ref "U401") (pin "15") (pinfunction "VREF2_15") (pintype "passive"))
      (node (ref "U401") (pin "7") (pinfunction "VREF1_7") (pintype "passive"))
    )
    (net (code "157") (name "PLD_AS") (class "Default")
      (node (ref "R300H") (pin "1") (pinfunction "1_1") (pintype "input"))
      (node (ref "U300") (pin "25") (pinfunction "AS/-TS/_25") (pintype "unspecified"))
      (node (ref "U304") (pin "21") (pinfunction "IOQ_21") (pintype "unspecified"))
      (node (ref "U305") (pin "4") (pinfunction "I_4") (pintype "unspecified"))
    )
    (net (code "158") (name "PLD_ASQ") (class "Default")
      (node (ref "U305") (pin "20") (pinfunction "IOQ_20") (pintype "unspecified"))
      (node (ref "U306") (pin "13") (pinfunction "I_13") (pintype "unspecified"))
    )
    (net (code "159") (name "PLD_CFGLT") (class "Default")
      (node (ref "U200") (pin "11") (pinfunction "CP_11") (pintype "unspecified"))
      (node (ref "U202") (pin "23") (pinfunction "IOQ_23") (pintype "unspecified"))
    )
    (net (code "160") (name "PLD_DOE") (class "Default")
      (node (ref "R109H") (pin "2") (pinfunction "2_2") (pintype "input"))
      (node (ref "U109") (pin "4") (pinfunction "A2_4") (pintype "unspecified"))
      (node (ref "U205") (pin "5") (pinfunction "I_5") (pintype "unspecified"))
      (node (ref "U304") (pin "10") (pinfunction "I_10") (pintype "unspecified"))
      (node (ref "U305") (pin "27") (pinfunction "IOQ_27") (pintype "unspecified"))
      (node (ref "U306") (pin "23") (pinfunction "IOQ_23") (pintype "unspecified"))
    )
    (net (code "161") (name "PLD_DS") (class "Default")
      (node (ref "R300G") (pin "1") (pinfunction "1_1") (pintype "input"))
      (node (ref "U300") (pin "87") (pinfunction "DS/-DLE_87") (pintype "unspecified"))
      (node (ref "U304") (pin "20") (pinfunction "IOQ_20") (pintype "unspecified"))
    )
    (net (code "162") (name "PLD_DS0") (class "Default")
      (node (ref "R109A") (pin "1") (pinfunction "1_1") (pintype "input"))
      (node (ref "U109") (pin "9") (pinfunction "A7_9") (pintype "unspecified"))
      (node (ref "U203") (pin "10") (pinfunction "I_10") (pintype "unspecified"))
      (node (ref "U207") (pin "6") (pinfunction "I_6") (pintype "unspecified"))
      (node (ref "U304") (pin "9") (pinfunction "I_9") (pintype "unspecified"))
      (node (ref "U305") (pin "23") (pinfunction "IOQ_23") (pintype "unspecified"))
    )
    (net (code "163") (name "PLD_DS1") (class "Default")
      (node (ref "R109B") (pin "1") (pinfunction "1_1") (pintype "input"))
      (node (ref "U109") (pin "8") (pinfunction "A6_8") (pintype "unspecified"))
      (node (ref "U304") (pin "7") (pinfunction "I_7") (pintype "unspecified"))
      (node (ref "U305") (pin "24") (pinfunction "IOQ_24") (pintype "unspecified"))
    )
    (net (code "164") (name "PLD_DS2") (class "Default")
      (node (ref "R109C") (pin "1") (pinfunction "1_1") (pintype "input"))
      (node (ref "U109") (pin "7") (pinfunction "A5_7") (pintype "unspecified"))
      (node (ref "U304") (pin "6") (pinfunction "I_6") (pintype "unspecified"))
      (node (ref "U305") (pin "25") (pinfunction "IOQ_25") (pintype "unspecified"))
    )
    (net (code "165") (name "PLD_DS3") (class "Default")
      (node (ref "R109D") (pin "1") (pinfunction "1_1") (pintype "input"))
      (node (ref "U109") (pin "6") (pinfunction "A4_6") (pintype "unspecified"))
      (node (ref "U202") (pin "11") (pinfunction "I_11") (pintype "unspecified"))
      (node (ref "U304") (pin "5") (pinfunction "I_5") (pintype "unspecified"))
      (node (ref "U305") (pin "26") (pinfunction "IOQ_26") (pintype "unspecified"))
    )
    (net (code "166") (name "PLD_DTACK") (class "Default")
      (node (ref "U303") (pin "9") (pinfunction "I_9") (pintype "unspecified"))
      (node (ref "U304") (pin "11") (pinfunction "I_11") (pintype "unspecified"))
      (node (ref "U306") (pin "17") (pinfunction "IOQ_17") (pintype "unspecified"))
    )
    (net (code "167") (name "PLD_FC0") (class "Default")
      (node (ref "R109F") (pin "1") (pinfunction "1_1") (pintype "input"))
      (node (ref "U109") (pin "3") (pinfunction "A1_3") (pintype "unspecified"))
      (node (ref "U202") (pin "16") (pinfunction "I_16") (pintype "unspecified"))
      (node (ref "U300") (pin "30") (pinfunction "FC0-TM0_30") (pintype "unspecified"))
    )
    (net (code "168") (name "PLD_FC1") (class "Default")
      (node (ref "R109G") (pin "1") (pinfunction "1_1") (pintype "input"))
      (node (ref "U109") (pin "2") (pinfunction "A0_2") (pintype "unspecified"))
      (node (ref "U202") (pin "13") (pinfunction "I_13") (pintype "unspecified"))
      (node (ref "U300") (pin "29") (pinfunction "FC1-TM1_29") (pintype "unspecified"))
    )
    (net (code "169") (name "PLD_FC2") (class "Default")
      (node (ref "R103A") (pin "1") (pinfunction "1_1") (pintype "input"))
      (node (ref "U103") (pin "8") (pinfunction "A6_8") (pintype "unspecified"))
      (node (ref "U203") (pin "11") (pinfunction "I_11") (pintype "unspecified"))
      (node (ref "U300") (pin "28") (pinfunction "FC2-TM2_28") (pintype "unspecified"))
    )
    (net (code "170") (name "PLD_FCS") (class "Default")
      (node (ref "FB500") (pin "2") (pinfunction "2_2") (pintype "unspecified"))
      (node (ref "U100") (pin "1") (pinfunction "LEBA_1") (pintype "unspecified"))
      (node (ref "U101") (pin "1") (pinfunction "LEBA_1") (pintype "unspecified"))
      (node (ref "U102") (pin "1") (pinfunction "LEBA_1") (pintype "unspecified"))
      (node (ref "U202") (pin "12") (pinfunction "I_12") (pintype "unspecified"))
      (node (ref "U203") (pin "12") (pinfunction "I_12") (pintype "unspecified"))
      (node (ref "U205") (pin "6") (pinfunction "I_6") (pintype "unspecified"))
      (node (ref "U207") (pin "12") (pinfunction "I_12") (pintype "unspecified"))
      (node (ref "U303") (pin "6") (pinfunction "I_6") (pintype "unspecified"))
      (node (ref "U306") (pin "4") (pinfunction "I_4") (pintype "unspecified"))
    )
    (net (code "171") (name "PLD_INT") (class "Default")
      (node (ref "U203") (pin "7") (pinfunction "I_7") (pintype "unspecified"))
      (node (ref "U207") (pin "26") (pinfunction "IOQ_26") (pintype "unspecified"))
    )
    (net (code "172") (name "PLD_INTREG") (class "Default")
      (node (ref "U203") (pin "24") (pinfunction "IOQ_24") (pintype "unspecified"))
      (node (ref "U204") (pin "11") (pinfunction "CP_11") (pintype "unspecified"))
      (node (ref "U205") (pin "11") (pinfunction "I_11") (pintype "unspecified"))
    )
    (net (code "173") (name "PLD_INTSPC") (class "Default")
      (node (ref "U202") (pin "27") (pinfunction "IOQ_27") (pintype "unspecified"))
      (node (ref "U203") (pin "16") (pinfunction "I_16") (pintype "unspecified"))
    )
    (net (code "174") (name "PLD_INTVEC") (class "Default")
      (node (ref "U203") (pin "23") (pinfunction "IOQ_23") (pintype "unspecified"))
      (node (ref "U204") (pin "1") (pinfunction "OE#_1") (pintype "unspecified"))
      (node (ref "U205") (pin "12") (pinfunction "I_12") (pintype "unspecified"))
      (node (ref "U207") (pin "11") (pinfunction "I_11") (pintype "unspecified"))
    )
    (net (code "175") (name "PLD_MTCR") (class "Default")
      (node (ref "R109E") (pin "1") (pinfunction "1_1") (pintype "input"))
      (node (ref "U109") (pin "5") (pinfunction "A3_5") (pintype "unspecified"))
      (node (ref "U203") (pin "13") (pinfunction "I_13") (pintype "unspecified"))
      (node (ref "U205") (pin "17") (pinfunction "IOQ_17") (pintype "unspecified"))
      (node (ref "U305") (pin "10") (pinfunction "I_10") (pintype "unspecified"))
      (node (ref "U306") (pin "25") (pinfunction "IOQ_25") (pintype "unspecified"))
    )
    (net (code "176") (name "PLD_MYBUS") (class "Default")
      (node (ref "U205") (pin "4") (pinfunction "I_4") (pintype "unspecified"))
      (node (ref "U303") (pin "20") (pinfunction "IOQ_20") (pintype "unspecified"))
      (node (ref "U304") (pin "13") (pinfunction "I_13") (pintype "unspecified"))
      (node (ref "U305") (pin "3") (pinfunction "I_3") (pintype "unspecified"))
      (node (ref "U306") (pin "3") (pinfunction "I_3") (pintype "unspecified"))
    )
    (net (code "177") (name "PLD_NACK") (class "Default")
      (node (ref "U205") (pin "16") (pinfunction "I_16") (pintype "unspecified"))
      (node (ref "U207") (pin "24") (pinfunction "IOQ_24") (pintype "unspecified"))
    )
    (net (code "178") (name "PLD_NOZ3") (class "Default")
      (node (ref "U205") (pin "10") (pinfunction "I_10") (pintype "unspecified"))
      (node (ref "U305") (pin "9") (pinfunction "I_9") (pintype "unspecified"))
      (node (ref "U306") (pin "20") (pinfunction "IOQ_20") (pintype "unspecified"))
    )
    (net (code "179") (name "PLD_READ") (class "Default")
      (node (ref "FB506") (pin "1") (pinfunction "1_1") (pintype "unspecified"))
      (node (ref "R103B") (pin "1") (pinfunction "1_1") (pintype "input"))
      (node (ref "U103") (pin "9") (pinfunction "A7_9") (pintype "unspecified"))
      (node (ref "U202") (pin "10") (pinfunction "I_10") (pintype "unspecified"))
      (node (ref "U203") (pin "9") (pinfunction "I_9") (pintype "unspecified"))
      (node (ref "U205") (pin "7") (pinfunction "I_7") (pintype "unspecified"))
      (node (ref "U207") (pin "7") (pinfunction "I_7") (pintype "unspecified"))
      (node (ref "U304") (pin "4") (pinfunction "I_4") (pintype "unspecified"))
      (node (ref "U305") (pin "5") (pinfunction "I_5") (pintype "unspecified"))
    )
    (net (code "180") (name "PLD_SCSI") (class "Default")
      (node (ref "U203") (pin "26") (pinfunction "IOQ_26") (pintype "unspecified"))
      (node (ref "U304") (pin "3") (pinfunction "I_3") (pintype "unspecified"))
      (node (ref "U306") (pin "7") (pinfunction "I_7") (pintype "unspecified"))
    )
    (net (code "181") (name "PLD_SID") (class "Default")
      (node (ref "U203") (pin "17") (pinfunction "IOQ_17") (pintype "unspecified"))
      (node (ref "U205") (pin "19") (pinfunction "IOQ_19") (pintype "unspecified"))
      (node (ref "U213") (pin "1") (pinfunction "OE1#_1") (pintype "unspecified"))
      (node (ref "U213") (pin "19") (pinfunction "OE2#_19") (pintype "unspecified"))
    )
    (net (code "182") (name "PLD_SIZ0") (class "Default")
      (node (ref "R300E") (pin "1") (pinfunction "1_1") (pintype "input"))
      (node (ref "U300") (pin "27") (pinfunction "SIZ0_27") (pintype "unspecified"))
      (node (ref "U304") (pin "24") (pinfunction "IOQ_24") (pintype "unspecified"))
      (node (ref "U305") (pin "7") (pinfunction "I_7") (pintype "unspecified"))
    )
    (net (code "183") (name "PLD_SIZ1") (class "Default")
      (node (ref "R300F") (pin "1") (pinfunction "1_1") (pintype "input"))
      (node (ref "U300") (pin "26") (pinfunction "SIZ1_26") (pintype "unspecified"))
      (node (ref "U304") (pin "25") (pinfunction "IOQ_25") (pintype "unspecified"))
      (node (ref "U305") (pin "6") (pinfunction "I_6") (pintype "unspecified"))
    )
    (net (code "184") (name "ROM_A15") (class "Default")
      (node (ref "J100") (pin "2") (pinfunction "2_2") (pintype "input"))
      (node (ref "U206") (pin "1") (pinfunction "VPP_1") (pintype "input"))
    )
    (net (code "185") (name "ROM_OE") (class "Default")
      (node (ref "U203") (pin "25") (pinfunction "IOQ_25") (pintype "unspecified"))
      (node (ref "U206") (pin "22") (pinfunction "OE#_22") (pintype "passive"))
      (node (ref "U207") (pin "19") (pinfunction "IOQ_19") (pintype "unspecified"))
    )
    (net (code "186") (name "SBG") (class "Default")
      (node (ref "U300") (pin "100") (pinfunction "BG/_100") (pintype "unspecified"))
      (node (ref "U303") (pin "21") (pinfunction "IOQ_21") (pintype "unspecified"))
    )
    (net (code "187") (name "SBR") (class "Default")
      (node (ref "FB503") (pin "2") (pinfunction "2_2") (pintype "unspecified"))
      (node (ref "U303") (pin "4") (pinfunction "I_4") (pintype "unspecified"))
    )
    (net (code "188") (name "SCDAT0") (class "Default")
      (node (ref "FB310K") (pin "1") (pinfunction "1_1") (pintype "unspecified"))
      (node (ref "FB311A") (pin "2") (pinfunction "2_2") (pintype "unspecified"))
      (node (ref "RP300B") (pin "5") (pinfunction "R4_5") (pintype "unspecified"))
      (node (ref "U300") (pin "131") (pinfunction "SD0/_131") (pintype "unspecified"))
      (node (ref "U311") (pin "3") (pinfunction "R2_3") (pintype "unspecified"))
    )
    (net (code "189") (name "SCDAT1") (class "Default")
      (node (ref "FB310L") (pin "1") (pinfunction "1_1") (pintype "unspecified"))
      (node (ref "FB311B") (pin "2") (pinfunction "2_2") (pintype "unspecified"))
      (node (ref "RP300B") (pin "6") (pinfunction "R5_6") (pintype "unspecified"))
      (node (ref "U300") (pin "130") (pinfunction "SD1/_130") (pintype "unspecified"))
      (node (ref "U311") (pin "4") (pinfunction "R3_4") (pintype "unspecified"))
    )
    (net (code "190") (name "SCDAT2") (class "Default")
      (node (ref "FB310M") (pin "1") (pinfunction "1_1") (pintype "unspecified"))
      (node (ref "FB311C") (pin "2") (pinfunction "2_2") (pintype "unspecified"))
      (node (ref "RP300B") (pin "7") (pinfunction "R6_7") (pintype "unspecified"))
      (node (ref "U300") (pin "129") (pinfunction "SD2/_129") (pintype "unspecified"))
      (node (ref "U311") (pin "5") (pinfunction "R4_5") (pintype "unspecified"))
    )
    (net (code "191") (name "SCDAT3") (class "Default")
      (node (ref "FB310N") (pin "1") (pinfunction "1_1") (pintype "unspecified"))
      (node (ref "FB311D") (pin "2") (pinfunction "2_2") (pintype "unspecified"))
      (node (ref "RP300A") (pin "7") (pinfunction "R6_7") (pintype "unspecified"))
      (node (ref "U300") (pin "127") (pinfunction "SD3/_127") (pintype "unspecified"))
      (node (ref "U311") (pin "6") (pinfunction "R5_6") (pintype "unspecified"))
    )
    (net (code "192") (name "SCDAT4") (class "Default")
      (node (ref "FB310O") (pin "1") (pinfunction "1_1") (pintype "unspecified"))
      (node (ref "FB311E") (pin "2") (pinfunction "2_2") (pintype "unspecified"))
      (node (ref "RP300A") (pin "6") (pinfunction "R5_6") (pintype "unspecified"))
      (node (ref "U300") (pin "126") (pinfunction "SD4/_126") (pintype "unspecified"))
      (node (ref "U310") (pin "5") (pinfunction "R4_5") (pintype "unspecified"))
    )
    (net (code "193") (name "SCDAT5") (class "Default")
      (node (ref "FB310P") (pin "1") (pinfunction "1_1") (pintype "unspecified"))
      (node (ref "FB311F") (pin "2") (pinfunction "2_2") (pintype "unspecified"))
      (node (ref "RP300A") (pin "5") (pinfunction "R4_5") (pintype "unspecified"))
      (node (ref "U300") (pin "125") (pinfunction "SD5/_125") (pintype "unspecified"))
      (node (ref "U311") (pin "10") (pinfunction "R6_10") (pintype "unspecified"))
    )
    (net (code "194") (name "SCDAT6") (class "Default")
      (node (ref "FB310Q") (pin "1") (pinfunction "1_1") (pintype "unspecified"))
      (node (ref "FB311G") (pin "2") (pinfunction "2_2") (pintype "unspecified"))
      (node (ref "RP300A") (pin "4") (pinfunction "R3_4") (pintype "unspecified"))
      (node (ref "U300") (pin "124") (pinfunction "SD6/_124") (pintype "unspecified"))
      (node (ref "U311") (pin "11") (pinfunction "R7_11") (pintype "unspecified"))
    )
    (net (code "195") (name "SCDAT7") (class "Default")
      (node (ref "FB310R") (pin "1") (pinfunction "1_1") (pintype "unspecified"))
      (node (ref "FB311H") (pin "2") (pinfunction "2_2") (pintype "unspecified"))
      (node (ref "RP300A") (pin "3") (pinfunction "R2_3") (pintype "unspecified"))
      (node (ref "U300") (pin "122") (pinfunction "SD7/_122") (pintype "unspecified"))
      (node (ref "U311") (pin "12") (pinfunction "R8_12") (pintype "unspecified"))
    )
    (net (code "196") (name "SCDATP") (class "Default")
      (node (ref "FB310J") (pin "1") (pinfunction "1_1") (pintype "unspecified"))
      (node (ref "FB311I") (pin "2") (pinfunction "2_2") (pintype "unspecified"))
      (node (ref "RP300A") (pin "2") (pinfunction "R1_2") (pintype "unspecified"))
      (node (ref "U300") (pin "121") (pinfunction "SDP/_121") (pintype "unspecified"))
      (node (ref "U311") (pin "13") (pinfunction "R9_13") (pintype "unspecified"))
    )
    (net (code "197") (name "SCSI_BUSY") (class "Default")
      (node (ref "CN309") (pin "36") (pinfunction "36_36") (pintype "input"))
      (node (ref "FB311R") (pin "1") (pinfunction "1_1") (pintype "unspecified"))
      (node (ref "U307") (pin "1") (pinfunction "1A_1") (pintype "unspecified"))
      (node (ref "U307") (pin "3") (pinfunction "2A_3") (pintype "unspecified"))
    )
    (net (code "198") (name "SCSI_TERMPWR") (class "Default")
      (node (ref "CN309") (pin "26") (pinfunction "26_26") (pintype "input"))
      (node (ref "CN310") (pin "38") (pinfunction "38_38") (pintype "unspecified"))
      (node (ref "F309A") (pin "2") (pinfunction "2_2") (pintype "unspecified"))
      (node (ref "F309B") (pin "2") (pinfunction "2_2") (pintype "unspecified"))
      (node (ref "U310") (pin "1") (pinfunction "TPWR1_1") (pintype "passive"))
      (node (ref "U310") (pin "9") (pinfunction "TPWR2_9") (pintype "passive"))
      (node (ref "U311") (pin "1") (pinfunction "TPWR1_1") (pintype "passive"))
      (node (ref "U311") (pin "9") (pinfunction "TPWR2_9") (pintype "passive"))
    )
    (net (code "199") (name "SCTRL_ACK") (class "Default")
      (node (ref "FB310G") (pin "1") (pinfunction "1_1") (pintype "unspecified"))
      (node (ref "FB311Q") (pin "2") (pinfunction "2_2") (pintype "unspecified"))
      (node (ref "RP300C") (pin "7") (pinfunction "R6_7") (pintype "unspecified"))
      (node (ref "U300") (pin "117") (pinfunction "ACK/_117") (pintype "unspecified"))
      (node (ref "U310") (pin "10") (pinfunction "R6_10") (pintype "unspecified"))
    )
    (net (code "200") (name "SCTRL_ATN") (class "Default")
      (node (ref "FB310I") (pin "1") (pinfunction "1_1") (pintype "unspecified"))
      (node (ref "FB311J") (pin "2") (pinfunction "2_2") (pintype "unspecified"))
      (node (ref "RP300C") (pin "6") (pinfunction "R5_6") (pintype "unspecified"))
      (node (ref "U300") (pin "120") (pinfunction "ATN/_120") (pintype "unspecified"))
      (node (ref "U310") (pin "6") (pinfunction "R5_6") (pintype "unspecified"))
    )
    (net (code "201") (name "SCTRL_BSY") (class "Default")
      (node (ref "FB310H") (pin "1") (pinfunction "1_1") (pintype "unspecified"))
      (node (ref "FB311R") (pin "2") (pinfunction "2_2") (pintype "unspecified"))
      (node (ref "RP300C") (pin "3") (pinfunction "R2_3") (pintype "unspecified"))
      (node (ref "U300") (pin "119") (pinfunction "BSY/_119") (pintype "unspecified"))
      (node (ref "U310") (pin "2") (pinfunction "R1_2") (pintype "unspecified"))
    )
    (net (code "202") (name "SCTRL_CD") (class "Default")
      (node (ref "FB310C") (pin "1") (pinfunction "1_1") (pintype "unspecified"))
      (node (ref "FB311M") (pin "2") (pinfunction "2_2") (pintype "unspecified"))
      (node (ref "RP300B") (pin "2") (pinfunction "R1_2") (pintype "unspecified"))
      (node (ref "U300") (pin "112") (pinfunction "C/D_112") (pintype "unspecified"))
      (node (ref "U311") (pin "2") (pinfunction "R1_2") (pintype "unspecified"))
    )
    (net (code "203") (name "SCTRL_IO") (class "Default")
      (node (ref "FB310A") (pin "1") (pinfunction "1_1") (pintype "unspecified"))
      (node (ref "FB311K") (pin "2") (pinfunction "2_2") (pintype "unspecified"))
      (node (ref "RP300B") (pin "3") (pinfunction "R2_3") (pintype "unspecified"))
      (node (ref "U300") (pin "110") (pinfunction "I/O_110") (pintype "unspecified"))
      (node (ref "U310") (pin "13") (pinfunction "R9_13") (pintype "unspecified"))
    )
    (net (code "204") (name "SCTRL_MSG") (class "Default")
      (node (ref "FB310E") (pin "1") (pinfunction "1_1") (pintype "unspecified"))
      (node (ref "FB311O") (pin "2") (pinfunction "2_2") (pintype "unspecified"))
      (node (ref "RP300B") (pin "4") (pinfunction "R3_4") (pintype "unspecified"))
      (node (ref "U300") (pin "115") (pinfunction "MSG/_115") (pintype "unspecified"))
      (node (ref "U310") (pin "12") (pinfunction "R8_12") (pintype "unspecified"))
    )
    (net (code "205") (name "SCTRL_REQ") (class "Default")
      (node (ref "FB310B") (pin "1") (pinfunction "1_1") (pintype "unspecified"))
      (node (ref "FB311L") (pin "2") (pinfunction "2_2") (pintype "unspecified"))
      (node (ref "RP300C") (pin "2") (pinfunction "R1_2") (pintype "unspecified"))
      (node (ref "U300") (pin "111") (pinfunction "REQ/_111") (pintype "unspecified"))
      (node (ref "U310") (pin "11") (pinfunction "R7_11") (pintype "unspecified"))
    )
    (net (code "206") (name "SCTRL_RST") (class "Default")
      (node (ref "FB310F") (pin "1") (pinfunction "1_1") (pintype "unspecified"))
      (node (ref "FB311P") (pin "2") (pinfunction "2_2") (pintype "unspecified"))
      (node (ref "RP300C") (pin "5") (pinfunction "R4_5") (pintype "unspecified"))
      (node (ref "U300") (pin "116") (pinfunction "RST/_116") (pintype "unspecified"))
      (node (ref "U310") (pin "4") (pinfunction "R3_4") (pintype "unspecified"))
    )
    (net (code "207") (name "SCTRL_SEL") (class "Default")
      (node (ref "FB310D") (pin "1") (pinfunction "1_1") (pintype "unspecified"))
      (node (ref "FB311N") (pin "2") (pinfunction "2_2") (pintype "unspecified"))
      (node (ref "RP300C") (pin "4") (pinfunction "R3_4") (pintype "unspecified"))
      (node (ref "U300") (pin "114") (pinfunction "SEL/_114") (pintype "unspecified"))
      (node (ref "U310") (pin "3") (pinfunction "R2_3") (pintype "unspecified"))
    )
    (net (code "208") (name "SLACK") (class "Default")
      (node (ref "U205") (pin "9") (pinfunction "I_9") (pintype "unspecified"))
      (node (ref "U300") (pin "92") (pinfunction "SLACK/_92") (pintype "unspecified"))
    )
    (net (code "209") (name "SREG") (class "Default")
      (node (ref "U300") (pin "93") (pinfunction "CS/_93") (pintype "unspecified"))
      (node (ref "U304") (pin "19") (pinfunction "IOQ_19") (pintype "unspecified"))
    )
    (net (code "210") (name "STERM") (class "Default")
      (node (ref "R300D") (pin "2") (pinfunction "2_2") (pintype "input"))
      (node (ref "U300") (pin "36") (pinfunction "STERM/-TA/_36") (pintype "unspecified"))
      (node (ref "U304") (pin "12") (pinfunction "I_12") (pintype "unspecified"))
      (node (ref "U306") (pin "19") (pinfunction "IOQ_19") (pintype "unspecified"))
    )
    (net (code "211") (name "T_GND") (class "Default")
      (node (ref "C400A") (pin "2") (pinfunction "2_2") (pintype "unspecified"))
      (node (ref "C400B") (pin "1") (pinfunction "1_1") (pintype "input"))
      (node (ref "C401A") (pin "2") (pinfunction "2_2") (pintype "unspecified"))
      (node (ref "C401B") (pin "1") (pinfunction "1_1") (pintype "input"))
      (node (ref "C402") (pin "1") (pinfunction "1_1") (pintype "input"))
      (node (ref "C403") (pin "2") (pinfunction "2_2") (pintype "unspecified"))
      (node (ref "CN400") (pin "1") (pinfunction "1_1") (pintype "unspecified"))
      (node (ref "CN400") (pin "11") (pinfunction "11_11") (pintype "unspecified"))
      (node (ref "CN400") (pin "13") (pinfunction "13_13") (pintype "unspecified"))
      (node (ref "CN400") (pin "15") (pinfunction "15_15") (pintype "unspecified"))
      (node (ref "CN400") (pin "17") (pinfunction "17_17") (pintype "unspecified"))
      (node (ref "CN400") (pin "19") (pinfunction "19_19") (pintype "unspecified"))
      (node (ref "CN400") (pin "20") (pinfunction "20_20") (pintype "unspecified"))
      (node (ref "CN400") (pin "21") (pinfunction "21_21") (pintype "unspecified"))
      (node (ref "CN400") (pin "22") (pinfunction "22_22") (pintype "unspecified"))
      (node (ref "CN400") (pin "23") (pinfunction "23_23") (pintype "unspecified"))
      (node (ref "CN400") (pin "24") (pinfunction "24_24") (pintype "unspecified"))
      (node (ref "CN400") (pin "27") (pinfunction "27_27") (pintype "unspecified"))
      (node (ref "CN400") (pin "28") (pinfunction "28_28") (pintype "unspecified"))
      (node (ref "CN400") (pin "29") (pinfunction "29_29") (pintype "unspecified"))
      (node (ref "CN400") (pin "3") (pinfunction "3_3") (pintype "unspecified"))
      (node (ref "CN400") (pin "30") (pinfunction "30_30") (pintype "unspecified"))
      (node (ref "CN400") (pin "31") (pinfunction "31_31") (pintype "unspecified"))
      (node (ref "CN400") (pin "33") (pinfunction "33_33") (pintype "unspecified"))
      (node (ref "CN400") (pin "34") (pinfunction "34_34") (pintype "unspecified"))
      (node (ref "CN400") (pin "35") (pinfunction "35_35") (pintype "unspecified"))
      (node (ref "CN400") (pin "37") (pinfunction "37_37") (pintype "unspecified"))
      (node (ref "CN400") (pin "39") (pinfunction "39_39") (pintype "unspecified"))
      (node (ref "CN400") (pin "41") (pinfunction "41_41") (pintype "unspecified"))
      (node (ref "CN400") (pin "43") (pinfunction "43_43") (pintype "unspecified"))
      (node (ref "CN400") (pin "45") (pinfunction "45_45") (pintype "unspecified"))
      (node (ref "CN400") (pin "47") (pinfunction "47_47") (pintype "unspecified"))
      (node (ref "CN400") (pin "49") (pinfunction "49_49") (pintype "unspecified"))
      (node (ref "CN400") (pin "5") (pinfunction "5_5") (pintype "unspecified"))
      (node (ref "CN400") (pin "7") (pinfunction "7_7") (pintype "unspecified"))
      (node (ref "CN400") (pin "9") (pinfunction "9_9") (pintype "unspecified"))
      (node (ref "U400") (pin "8") (pinfunction "GND_8") (pintype "passive"))
      (node (ref "U401") (pin "8") (pinfunction "GND_8") (pintype "passive"))
    )
    (net (code "212") (name "T_SCDAT0") (class "Default")
      (node (ref "CN400") (pin "2") (pinfunction "2_2") (pintype "unspecified"))
      (node (ref "U401") (pin "13") (pinfunction "R9_13") (pintype "unspecified"))
    )
    (net (code "213") (name "T_SCDAT1") (class "Default")
      (node (ref "CN400") (pin "4") (pinfunction "4_4") (pintype "unspecified"))
      (node (ref "U401") (pin "12") (pinfunction "R8_12") (pintype "unspecified"))
    )
    (net (code "214") (name "T_SCDAT2") (class "Default")
      (node (ref "CN400") (pin "6") (pinfunction "6_6") (pintype "unspecified"))
      (node (ref "U401") (pin "11") (pinfunction "R7_11") (pintype "unspecified"))
    )
    (net (code "215") (name "T_SCDAT3") (class "Default")
      (node (ref "CN400") (pin "8") (pinfunction "8_8") (pintype "unspecified"))
      (node (ref "U401") (pin "10") (pinfunction "R6_10") (pintype "unspecified"))
    )
    (net (code "216") (name "T_SCDAT4") (class "Default")
      (node (ref "CN400") (pin "10") (pinfunction "10_10") (pintype "unspecified"))
      (node (ref "U401") (pin "6") (pinfunction "R5_6") (pintype "unspecified"))
    )
    (net (code "217") (name "T_SCDAT5") (class "Default")
      (node (ref "CN400") (pin "12") (pinfunction "12_12") (pintype "unspecified"))
      (node (ref "U401") (pin "5") (pinfunction "R4_5") (pintype "unspecified"))
    )
    (net (code "218") (name "T_SCDAT6") (class "Default")
      (node (ref "CN400") (pin "14") (pinfunction "14_14") (pintype "unspecified"))
      (node (ref "U401") (pin "4") (pinfunction "R3_4") (pintype "unspecified"))
    )
    (net (code "219") (name "T_SCDAT7") (class "Default")
      (node (ref "CN400") (pin "16") (pinfunction "16_16") (pintype "unspecified"))
      (node (ref "U401") (pin "3") (pinfunction "R2_3") (pintype "unspecified"))
    )
    (net (code "220") (name "T_SCDATP") (class "Default")
      (node (ref "CN400") (pin "18") (pinfunction "18_18") (pintype "unspecified"))
      (node (ref "U401") (pin "2") (pinfunction "R1_2") (pintype "unspecified"))
    )
    (net (code "221") (name "T_SCSI_TERMPWR") (class "Default")
      (node (ref "C402") (pin "2") (pinfunction "2_2") (pintype "input"))
      (node (ref "C403") (pin "1") (pinfunction "1_1") (pintype "unspecified"))
      (node (ref "CN400") (pin "26") (pinfunction "26_26") (pintype "unspecified"))
      (node (ref "U400") (pin "1") (pinfunction "TPWR1_1") (pintype "passive"))
      (node (ref "U400") (pin "9") (pinfunction "TPWR2_9") (pintype "passive"))
      (node (ref "U401") (pin "1") (pinfunction "TPWR1_1") (pintype "passive"))
      (node (ref "U401") (pin "9") (pinfunction "TPWR2_9") (pintype "passive"))
    )
    (net (code "222") (name "T_SCTRL_ACK") (class "Default")
      (node (ref "CN400") (pin "38") (pinfunction "38_38") (pintype "unspecified"))
      (node (ref "U400") (pin "11") (pinfunction "R7_11") (pintype "unspecified"))
    )
    (net (code "223") (name "T_SCTRL_ATN") (class "Default")
      (node (ref "CN400") (pin "32") (pinfunction "32_32") (pintype "unspecified"))
      (node (ref "U400") (pin "13") (pinfunction "R9_13") (pintype "unspecified"))
    )
    (net (code "224") (name "T_SCTRL_BSY") (class "Default")
      (node (ref "CN400") (pin "36") (pinfunction "36_36") (pintype "unspecified"))
      (node (ref "U400") (pin "12") (pinfunction "R8_12") (pintype "unspecified"))
    )
    (net (code "225") (name "T_SCTRL_CD") (class "Default")
      (node (ref "CN400") (pin "46") (pinfunction "46_46") (pintype "unspecified"))
      (node (ref "U400") (pin "4") (pinfunction "R3_4") (pintype "unspecified"))
    )
    (net (code "226") (name "T_SCTRL_IO") (class "Default")
      (node (ref "CN400") (pin "50") (pinfunction "50_50") (pintype "unspecified"))
      (node (ref "U400") (pin "2") (pinfunction "R1_2") (pintype "unspecified"))
    )
    (net (code "227") (name "T_SCTRL_MSG") (class "Default")
      (node (ref "CN400") (pin "42") (pinfunction "42_42") (pintype "unspecified"))
      (node (ref "U400") (pin "6") (pinfunction "R5_6") (pintype "unspecified"))
    )
    (net (code "228") (name "T_SCTRL_REQ") (class "Default")
      (node (ref "CN400") (pin "48") (pinfunction "48_48") (pintype "unspecified"))
      (node (ref "U400") (pin "3") (pinfunction "R2_3") (pintype "unspecified"))
    )
    (net (code "229") (name "T_SCTRL_RST") (class "Default")
      (node (ref "CN400") (pin "40") (pinfunction "40_40") (pintype "unspecified"))
      (node (ref "U400") (pin "10") (pinfunction "R6_10") (pintype "unspecified"))
    )
    (net (code "230") (name "T_SCTRL_SEL") (class "Default")
      (node (ref "CN400") (pin "44") (pinfunction "44_44") (pintype "unspecified"))
      (node (ref "U400") (pin "5") (pinfunction "R4_5") (pintype "unspecified"))
    )
    (net (code "231") (name "V5") (class "Default")
      (node (ref "C1") (pin "05") (pinfunction "+5V_05") (pintype "bidirectional"))
      (node (ref "C1") (pin "06") (pinfunction "+5V_06") (pintype "bidirectional"))
      (node (ref "C10") (pin "1") (pinfunction "1_1") (pintype "input"))
      (node (ref "C100A") (pin "1") (pinfunction "1_1") (pintype "input"))
      (node (ref "C101A") (pin "1") (pinfunction "1_1") (pintype "input"))
      (node (ref "C102A") (pin "1") (pinfunction "1_1") (pintype "input"))
      (node (ref "C103A") (pin "1") (pinfunction "1_1") (pintype "input"))
      (node (ref "C105A") (pin "1") (pinfunction "1_1") (pintype "input"))
      (node (ref "C106A") (pin "2") (pinfunction "2_2") (pintype "input"))
      (node (ref "C107A") (pin "1") (pinfunction "1_1") (pintype "input"))
      (node (ref "C108A") (pin "1") (pinfunction "1_1") (pintype "input"))
      (node (ref "C109A") (pin "1") (pinfunction "1_1") (pintype "input"))
      (node (ref "C11") (pin "1") (pinfunction "1_1") (pintype "input"))
      (node (ref "C12") (pin "1") (pinfunction "1_1") (pintype "input"))
      (node (ref "C13") (pin "1") (pinfunction "1_1") (pintype "input"))
      (node (ref "C1A") (pin "2") (pinfunction "2_2") (pintype "input"))
      (node (ref "C1B") (pin "1") (pinfunction "1_1") (pintype "input"))
      (node (ref "C200A") (pin "2") (pinfunction "2_2") (pintype "input"))
      (node (ref "C201A") (pin "1") (pinfunction "1_1") (pintype "input"))
      (node (ref "C202A") (pin "1") (pinfunction "1_1") (pintype "input"))
      (node (ref "C203A") (pin "1") (pinfunction "1_1") (pintype "input"))
      (node (ref "C204A") (pin "2") (pinfunction "2_2") (pintype "input"))
      (node (ref "C205A") (pin "1") (pinfunction "1_1") (pintype "input"))
      (node (ref "C206A") (pin "2") (pinfunction "2_2") (pintype "input"))
      (node (ref "C207A") (pin "1") (pinfunction "1_1") (pintype "input"))
      (node (ref "C212A") (pin "1") (pinfunction "1_1") (pintype "input"))
      (node (ref "C300A") (pin "1") (pinfunction "1_1") (pintype "input"))
      (node (ref "C300B") (pin "1") (pinfunction "1_1") (pintype "input"))
      (node (ref "C300C") (pin "1") (pinfunction "1_1") (pintype "input"))
      (node (ref "C300D") (pin "2") (pinfunction "2_2") (pintype "input"))
      (node (ref "C300E") (pin "1") (pinfunction "1_1") (pintype "input"))
      (node (ref "C300F") (pin "1") (pinfunction "1_1") (pintype "input"))
      (node (ref "C300G") (pin "1") (pinfunction "1_1") (pintype "input"))
      (node (ref "C300H") (pin "2") (pinfunction "2_2") (pintype "input"))
      (node (ref "C300I") (pin "1") (pinfunction "1_1") (pintype "input"))
      (node (ref "C301A") (pin "2") (pinfunction "2_2") (pintype "input"))
      (node (ref "C302A") (pin "1") (pinfunction "1_1") (pintype "input"))
      (node (ref "C303A") (pin "2") (pinfunction "2_2") (pintype "input"))
      (node (ref "C304A") (pin "1") (pinfunction "1_1") (pintype "input"))
      (node (ref "C305A") (pin "1") (pinfunction "1_1") (pintype "input"))
      (node (ref "C306A") (pin "1") (pinfunction "1_1") (pintype "input"))
      (node (ref "C307A") (pin "2") (pinfunction "2_2") (pintype "input"))
      (node (ref "CN2") (pin "4") (pinfunction "4_4") (pintype "unspecified"))
      (node (ref "CN308") (pin "2") (pinfunction "2_2") (pintype "input"))
      (node (ref "CN351") (pin "2") (pinfunction "2_2") (pintype "input"))
      (node (ref "D309A") (pin "2") (pinfunction "A_2") (pintype "unspecified"))
      (node (ref "J100") (pin "1") (pinfunction "1_1") (pintype "input"))
      (node (ref "R100A") (pin "2") (pinfunction "2_2") (pintype "input"))
      (node (ref "R103A") (pin "2") (pinfunction "2_2") (pintype "input"))
      (node (ref "R103B") (pin "2") (pinfunction "2_2") (pintype "input"))
      (node (ref "R109A") (pin "2") (pinfunction "2_2") (pintype "input"))
      (node (ref "R109B") (pin "2") (pinfunction "2_2") (pintype "input"))
      (node (ref "R109C") (pin "2") (pinfunction "2_2") (pintype "input"))
      (node (ref "R109D") (pin "2") (pinfunction "2_2") (pintype "input"))
      (node (ref "R109E") (pin "2") (pinfunction "2_2") (pintype "input"))
      (node (ref "R109F") (pin "2") (pinfunction "2_2") (pintype "input"))
      (node (ref "R109G") (pin "2") (pinfunction "2_2") (pintype "input"))
      (node (ref "R200A") (pin "2") (pinfunction "2_2") (pintype "input"))
      (node (ref "R200B") (pin "2") (pinfunction "2_2") (pintype "input"))
      (node (ref "R200C") (pin "2") (pinfunction "2_2") (pintype "input"))
      (node (ref "R200D") (pin "2") (pinfunction "2_2") (pintype "input"))
      (node (ref "R200E") (pin "2") (pinfunction "2_2") (pintype "input"))
      (node (ref "R200F") (pin "2") (pinfunction "2_2") (pintype "input"))
      (node (ref "R200G") (pin "2") (pinfunction "2_2") (pintype "input"))
      (node (ref "R200H") (pin "2") (pinfunction "2_2") (pintype "input"))
      (node (ref "R212A") (pin "1") (pinfunction "1_1") (pintype "input"))
      (node (ref "R212B") (pin "2") (pinfunction "2_2") (pintype "input"))
      (node (ref "R212C") (pin "2") (pinfunction "2_2") (pintype "input"))
      (node (ref "R212D") (pin "2") (pinfunction "2_2") (pintype "input"))
      (node (ref "R212E") (pin "1") (pinfunction "1_1") (pintype "input"))
      (node (ref "R212F") (pin "1") (pinfunction "1_1") (pintype "input"))
      (node (ref "R212G") (pin "1") (pinfunction "1_1") (pintype "input"))
      (node (ref "R212H") (pin "1") (pinfunction "1_1") (pintype "input"))
      (node (ref "R300A") (pin "2") (pinfunction "2_2") (pintype "input"))
      (node (ref "R300B") (pin "1") (pinfunction "1_1") (pintype "input"))
      (node (ref "R300C") (pin "2") (pinfunction "2_2") (pintype "input"))
      (node (ref "R300D") (pin "1") (pinfunction "1_1") (pintype "input"))
      (node (ref "R300E") (pin "2") (pinfunction "2_2") (pintype "input"))
      (node (ref "R300F") (pin "2") (pinfunction "2_2") (pintype "input"))
      (node (ref "R300G") (pin "2") (pinfunction "2_2") (pintype "input"))
      (node (ref "R300H") (pin "2") (pinfunction "2_2") (pintype "input"))
      (node (ref "R300I") (pin "2") (pinfunction "2_2") (pintype "input"))
      (node (ref "R300J") (pin "2") (pinfunction "2_2") (pintype "input"))
      (node (ref "R300K") (pin "2") (pinfunction "2_2") (pintype "input"))
      (node (ref "R300L") (pin "2") (pinfunction "2_2") (pintype "input"))
      (node (ref "R300M") (pin "1") (pinfunction "1_1") (pintype "input"))
      (node (ref "R300N") (pin "2") (pinfunction "2_2") (pintype "input"))
      (node (ref "R300O") (pin "2") (pinfunction "2_2") (pintype "input"))
      (node (ref "R300P") (pin "2") (pinfunction "2_2") (pintype "input"))
      (node (ref "R307A") (pin "2") (pinfunction "2_2") (pintype "input"))
      (node (ref "R307B") (pin "1") (pinfunction "1_1") (pintype "input"))
      (node (ref "RP300A") (pin "8") (pinfunction "COM2_8") (pintype "unspecified"))
      (node (ref "RP300B") (pin "8") (pinfunction "COM2_8") (pintype "unspecified"))
      (node (ref "RP300C") (pin "8") (pinfunction "COM2_8") (pintype "unspecified"))
      (node (ref "U100") (pin "24") (pinfunction "VCC_24") (pintype "passive"))
      (node (ref "U101") (pin "24") (pinfunction "VCC_24") (pintype "passive"))
      (node (ref "U102") (pin "24") (pinfunction "VCC_24") (pintype "passive"))
      (node (ref "U103") (pin "20") (pinfunction "VCC_20") (pintype "unspecified"))
      (node (ref "U105") (pin "24") (pinfunction "VCC_24") (pintype "passive"))
      (node (ref "U106") (pin "24") (pinfunction "VCC_24") (pintype "passive"))
      (node (ref "U107") (pin "24") (pinfunction "VCC_24") (pintype "passive"))
      (node (ref "U108") (pin "24") (pinfunction "VCC_24") (pintype "passive"))
      (node (ref "U109") (pin "20") (pinfunction "VCC_20") (pintype "unspecified"))
      (node (ref "U200") (pin "20") (pinfunction "VCC_20") (pintype "unspecified"))
      (node (ref "U201") (pin "20") (pinfunction "VCC_20") (pintype "unspecified"))
      (node (ref "U202") (pin "28") (pinfunction "VCC_28") (pintype "unspecified"))
      (node (ref "U203") (pin "28") (pinfunction "VCC_28") (pintype "unspecified"))
      (node (ref "U204") (pin "20") (pinfunction "VCC_20") (pintype "unspecified"))
      (node (ref "U205") (pin "28") (pinfunction "VCC_28") (pintype "unspecified"))
      (node (ref "U206") (pin "28") (pinfunction "VCC_28") (pintype "output"))
      (node (ref "U207") (pin "28") (pinfunction "VCC_28") (pintype "unspecified"))
      (node (ref "U213") (pin "20") (pinfunction "VCC_20") (pintype "unspecified"))
      (node (ref "U300") (pin "139") (pinfunction "Vdd_139") (pintype "unspecified"))
      (node (ref "U300") (pin "153") (pinfunction "Vdd_153") (pintype "unspecified"))
      (node (ref "U300") (pin "19") (pinfunction "Vdd_19") (pintype "unspecified"))
      (node (ref "U300") (pin "39") (pinfunction "Vdd_39") (pintype "unspecified"))
      (node (ref "U300") (pin "40") (pinfunction "HALT/-TIP/_40") (pintype "unspecified"))
      (node (ref "U300") (pin "49") (pinfunction "Vdd_49") (pintype "unspecified"))
      (node (ref "U300") (pin "6") (pinfunction "Vdd_6") (pintype "unspecified"))
      (node (ref "U300") (pin "64") (pinfunction "Vdd_64") (pintype "unspecified"))
      (node (ref "U300") (pin "79") (pinfunction "Vdd_79") (pintype "unspecified"))
      (node (ref "U300") (pin "90") (pinfunction "BIG_LIT/_90") (pintype "unspecified"))
      (node (ref "U300") (pin "91") (pinfunction "BS_91") (pintype "unspecified"))
      (node (ref "U300") (pin "95") (pinfunction "BOFF/_95") (pintype "unspecified"))
      (node (ref "U300") (pin "99") (pinfunction "Vdd_99") (pintype "unspecified"))
      (node (ref "U301") (pin "14") (pinfunction "Vcc_14") (pintype "unspecified"))
      (node (ref "U302") (pin "1") (pinfunction "RD0#_1") (pintype "unspecified"))
      (node (ref "U302") (pin "10") (pinfunction "SD1#_10") (pintype "unspecified"))
      (node (ref "U302") (pin "11") (pinfunction "CP1_11") (pintype "unspecified"))
      (node (ref "U302") (pin "12") (pinfunction "D1_12") (pintype "unspecified"))
      (node (ref "U302") (pin "13") (pinfunction "RD1#_13") (pintype "unspecified"))
      (node (ref "U302") (pin "14") (pinfunction "VCC_14") (pintype "unspecified"))
      (node (ref "U302") (pin "4") (pinfunction "SD0#_4") (pintype "unspecified"))
      (node (ref "U303") (pin "28") (pinfunction "VCC_28") (pintype "unspecified"))
      (node (ref "U304") (pin "28") (pinfunction "VCC_28") (pintype "unspecified"))
      (node (ref "U305") (pin "28") (pinfunction "VCC_28") (pintype "unspecified"))
      (node (ref "U306") (pin "28") (pinfunction "VCC_28") (pintype "unspecified"))
      (node (ref "U307") (pin "14") (pinfunction "VCC_14") (pintype "unspecified"))
    )
    (net (code "232") (name "V12") (class "Default")
      (node (ref "C1") (pin "10") (pinfunction "+12V_10") (pintype "bidirectional"))
      (node (ref "C1C") (pin "1") (pinfunction "1_1") (pintype "input"))
      (node (ref "CN2") (pin "1") (pinfunction "1_1") (pintype "unspecified"))
    )
    (net (code "233") (name "Z2D") (class "Default")
      (node (ref "FB504") (pin "2") (pinfunction "2_2") (pintype "unspecified"))
      (node (ref "U105") (pin "23") (pinfunction "CEBA_23") (pintype "unspecified"))
      (node (ref "U106") (pin "23") (pinfunction "CEBA_23") (pintype "unspecified"))
      (node (ref "U107") (pin "23") (pinfunction "CEBA_23") (pintype "unspecified"))
      (node (ref "U108") (pin "23") (pinfunction "CEBA_23") (pintype "unspecified"))
    )
    (net (code "234") (name "Z_7M") (class "Default")
      (node (ref "C1") (pin "92") (pinfunction "7M_Clock_92") (pintype "bidirectional"))
      (node (ref "U303") (pin "2") (pinfunction "CLK/I_2") (pintype "unspecified"))
    )
    (net (code "235") (name "Z_A2") (class "Default")
      (node (ref "C1") (pin "27") (pinfunction "A2_27") (pintype "output"))
      (node (ref "U103") (pin "13") (pinfunction "B5_13") (pintype "unspecified"))
    )
    (net (code "236") (name "Z_A3") (class "Default")
      (node (ref "C1") (pin "26") (pinfunction "A3_26") (pintype "bidirectional"))
      (node (ref "U103") (pin "14") (pinfunction "B4_14") (pintype "unspecified"))
    )
    (net (code "237") (name "Z_A4") (class "Default")
      (node (ref "C1") (pin "24") (pinfunction "A4_24") (pintype "bidirectional"))
      (node (ref "U103") (pin "15") (pinfunction "B3_15") (pintype "unspecified"))
    )
    (net (code "238") (name "Z_A5") (class "Default")
      (node (ref "C1") (pin "21") (pinfunction "A5_21") (pintype "output"))
      (node (ref "U103") (pin "16") (pinfunction "B2_16") (pintype "unspecified"))
    )
    (net (code "239") (name "Z_A6") (class "Default")
      (node (ref "C1") (pin "23") (pinfunction "A6_23") (pintype "output"))
      (node (ref "U103") (pin "17") (pinfunction "B1_17") (pintype "unspecified"))
    )
    (net (code "240") (name "Z_A7") (class "Default")
      (node (ref "C1") (pin "28") (pinfunction "A7_28") (pintype "bidirectional"))
      (node (ref "U103") (pin "18") (pinfunction "B0_18") (pintype "unspecified"))
    )
    (net (code "241") (name "Z_A8D0") (class "Default")
      (node (ref "C1") (pin "30") (pinfunction "A8+D0,A8_30") (pintype "bidirectional"))
      (node (ref "U102") (pin "15") (pinfunction "B7_15") (pintype "bidirectional"))
      (node (ref "U107") (pin "15") (pinfunction "B7_15") (pintype "bidirectional"))
    )
    (net (code "242") (name "Z_A9D1") (class "Default")
      (node (ref "C1") (pin "32") (pinfunction "A9+D1,A9_32") (pintype "bidirectional"))
      (node (ref "U102") (pin "16") (pinfunction "B6_16") (pintype "bidirectional"))
      (node (ref "U107") (pin "16") (pinfunction "B6_16") (pintype "bidirectional"))
    )
    (net (code "243") (name "Z_A10D2") (class "Default")
      (node (ref "C1") (pin "34") (pinfunction "A10+D2,A10_34") (pintype "bidirectional"))
      (node (ref "U102") (pin "17") (pinfunction "B5_17") (pintype "bidirectional"))
      (node (ref "U107") (pin "17") (pinfunction "B5_17") (pintype "bidirectional"))
    )
    (net (code "244") (name "Z_A11D3") (class "Default")
      (node (ref "C1") (pin "36") (pinfunction "A11+D3,A11_36") (pintype "bidirectional"))
      (node (ref "U102") (pin "18") (pinfunction "B4_18") (pintype "bidirectional"))
      (node (ref "U107") (pin "18") (pinfunction "B4_18") (pintype "bidirectional"))
    )
    (net (code "245") (name "Z_A12D4") (class "Default")
      (node (ref "C1") (pin "38") (pinfunction "A12+D4,A12_38") (pintype "bidirectional"))
      (node (ref "U102") (pin "19") (pinfunction "B3_19") (pintype "bidirectional"))
      (node (ref "U107") (pin "19") (pinfunction "B3_19") (pintype "bidirectional"))
    )
    (net (code "246") (name "Z_A13D5") (class "Default")
      (node (ref "C1") (pin "39") (pinfunction "A13+D5,A13_39") (pintype "unspecified"))
      (node (ref "U102") (pin "20") (pinfunction "B2_20") (pintype "bidirectional"))
      (node (ref "U107") (pin "20") (pinfunction "B2_20") (pintype "bidirectional"))
    )
    (net (code "247") (name "Z_A14D6") (class "Default")
      (node (ref "C1") (pin "41") (pinfunction "A14+D6,A14_41") (pintype "unspecified"))
      (node (ref "U102") (pin "21") (pinfunction "B1_21") (pintype "bidirectional"))
      (node (ref "U107") (pin "21") (pinfunction "B1_21") (pintype "bidirectional"))
    )
    (net (code "248") (name "Z_A15D7") (class "Default")
      (node (ref "C1") (pin "43") (pinfunction "A15+D7,A15_43") (pintype "unspecified"))
      (node (ref "U102") (pin "22") (pinfunction "B0_22") (pintype "bidirectional"))
      (node (ref "U107") (pin "22") (pinfunction "B0_22") (pintype "bidirectional"))
    )
    (net (code "249") (name "Z_A16D8") (class "Default")
      (node (ref "C1") (pin "45") (pinfunction "A16+D8,A16_45") (pintype "unspecified"))
      (node (ref "U101") (pin "15") (pinfunction "B7_15") (pintype "bidirectional"))
      (node (ref "U106") (pin "15") (pinfunction "B7_15") (pintype "bidirectional"))
    )
    (net (code "250") (name "Z_A17D9") (class "Default")
      (node (ref "C1") (pin "47") (pinfunction "A17+D9,A17_47") (pintype "unspecified"))
      (node (ref "U101") (pin "16") (pinfunction "B6_16") (pintype "bidirectional"))
      (node (ref "U106") (pin "16") (pinfunction "B6_16") (pintype "bidirectional"))
    )
    (net (code "251") (name "Z_A18D10") (class "Default")
      (node (ref "C1") (pin "52") (pinfunction "A18+D10,A18_52") (pintype "bidirectional"))
      (node (ref "U101") (pin "17") (pinfunction "B5_17") (pintype "bidirectional"))
      (node (ref "U106") (pin "17") (pinfunction "B5_17") (pintype "bidirectional"))
    )
    (net (code "252") (name "Z_A19D11") (class "Default")
      (node (ref "C1") (pin "54") (pinfunction "A19+D11,A19_54") (pintype "bidirectional"))
      (node (ref "U101") (pin "18") (pinfunction "B4_18") (pintype "bidirectional"))
      (node (ref "U106") (pin "18") (pinfunction "B4_18") (pintype "bidirectional"))
    )
    (net (code "253") (name "Z_A20D12") (class "Default")
      (node (ref "C1") (pin "56") (pinfunction "A20+D12,A20_56") (pintype "bidirectional"))
      (node (ref "U101") (pin "19") (pinfunction "B3_19") (pintype "bidirectional"))
      (node (ref "U106") (pin "19") (pinfunction "B3_19") (pintype "bidirectional"))
    )
    (net (code "254") (name "Z_A21D13") (class "Default")
      (node (ref "C1") (pin "58") (pinfunction "A21+D13,A21_58") (pintype "bidirectional"))
      (node (ref "U101") (pin "20") (pinfunction "B2_20") (pintype "bidirectional"))
      (node (ref "U106") (pin "20") (pinfunction "B2_20") (pintype "bidirectional"))
    )
    (net (code "255") (name "Z_A22D14") (class "Default")
      (node (ref "C1") (pin "57") (pinfunction "A22+D14,A22_57") (pintype "bidirectional"))
      (node (ref "U101") (pin "21") (pinfunction "B1_21") (pintype "bidirectional"))
      (node (ref "U106") (pin "21") (pinfunction "B1_21") (pintype "bidirectional"))
    )
    (net (code "256") (name "Z_A23D15") (class "Default")
      (node (ref "C1") (pin "59") (pinfunction "A23+D15,A23_59") (pintype "output"))
      (node (ref "U101") (pin "22") (pinfunction "B0_22") (pintype "bidirectional"))
      (node (ref "U106") (pin "22") (pinfunction "B0_22") (pintype "bidirectional"))
    )
    (net (code "257") (name "Z_A24D24") (class "Default")
      (node (ref "C1") (pin "80") (pinfunction "A24+D24,D8_80") (pintype "unspecified"))
      (node (ref "U100") (pin "15") (pinfunction "B7_15") (pintype "bidirectional"))
      (node (ref "U105") (pin "22") (pinfunction "B0_22") (pintype "bidirectional"))
    )
    (net (code "258") (name "Z_A25D25") (class "Default")
      (node (ref "C1") (pin "78") (pinfunction "A25+D25,D9_78") (pintype "unspecified"))
      (node (ref "U100") (pin "16") (pinfunction "B6_16") (pintype "bidirectional"))
      (node (ref "U105") (pin "21") (pinfunction "B1_21") (pintype "bidirectional"))
    )
    (net (code "259") (name "Z_A26D26") (class "Default")
      (node (ref "C1") (pin "76") (pinfunction "A26+D26,D10_76") (pintype "unspecified"))
      (node (ref "U100") (pin "17") (pinfunction "B5_17") (pintype "bidirectional"))
      (node (ref "U105") (pin "20") (pinfunction "B2_20") (pintype "bidirectional"))
    )
    (net (code "260") (name "Z_A27D27") (class "Default")
      (node (ref "C1") (pin "71") (pinfunction "A27+D27,D11_71") (pintype "unspecified"))
      (node (ref "U100") (pin "18") (pinfunction "B4_18") (pintype "bidirectional"))
      (node (ref "U105") (pin "19") (pinfunction "B3_19") (pintype "bidirectional"))
    )
    (net (code "261") (name "Z_A28D28") (class "Default")
      (node (ref "C1") (pin "69") (pinfunction "A28+D28,D12_69") (pintype "unspecified"))
      (node (ref "U100") (pin "19") (pinfunction "B3_19") (pintype "bidirectional"))
      (node (ref "U105") (pin "18") (pinfunction "B4_18") (pintype "bidirectional"))
    )
    (net (code "262") (name "Z_A29D29") (class "Default")
      (node (ref "C1") (pin "67") (pinfunction "A29+D29,D13_67") (pintype "unspecified"))
      (node (ref "U100") (pin "20") (pinfunction "B2_20") (pintype "bidirectional"))
      (node (ref "U105") (pin "17") (pinfunction "B5_17") (pintype "bidirectional"))
    )
    (net (code "263") (name "Z_A30D30") (class "Default")
      (node (ref "C1") (pin "65") (pinfunction "A30+D30,D14_65") (pintype "unspecified"))
      (node (ref "U100") (pin "21") (pinfunction "B1_21") (pintype "bidirectional"))
      (node (ref "U105") (pin "16") (pinfunction "B6_16") (pintype "bidirectional"))
    )
    (net (code "264") (name "Z_A31D31") (class "Default")
      (node (ref "C1") (pin "63") (pinfunction "A31+D31,D15_63") (pintype "bidirectional"))
      (node (ref "U100") (pin "22") (pinfunction "B0_22") (pintype "bidirectional"))
      (node (ref "U105") (pin "15") (pinfunction "B7_15") (pintype "bidirectional"))
    )
    (net (code "265") (name "Z_BERR") (class "Default")
      (node (ref "C1") (pin "46") (pinfunction "/BERR_46") (pintype "bidirectional"))
      (node (ref "U307") (pin "5") (pinfunction "3A_5") (pintype "unspecified"))
    )
    (net (code "266") (name "Z_BGn") (class "Default")
      (node (ref "C1") (pin "64") (pinfunction "/BGn_64") (pintype "bidirectional"))
      (node (ref "U303") (pin "5") (pinfunction "I_5") (pintype "unspecified"))
    )
    (net (code "267") (name "Z_BRn") (class "Default")
      (node (ref "C1") (pin "60") (pinfunction "/BRn_60") (pintype "bidirectional"))
      (node (ref "U303") (pin "25") (pinfunction "IOQ_25") (pintype "unspecified"))
    )
    (net (code "268") (name "Z_CFGIN") (class "Default")
      (node (ref "C1") (pin "12") (pinfunction "/CFGINn_12") (pintype "bidirectional"))
      (node (ref "U202") (pin "18") (pinfunction "IOQ_18") (pintype "unspecified"))
    )
    (net (code "269") (name "Z_CFGOUT") (class "Default")
      (node (ref "C1") (pin "11") (pinfunction "/CFGOUTn_11") (pintype "unspecified"))
      (node (ref "U200") (pin "1") (pinfunction "OE#_1") (pintype "unspecified"))
      (node (ref "U202") (pin "21") (pinfunction "IOQ_21") (pintype "unspecified"))
      (node (ref "U205") (pin "13") (pinfunction "I_13") (pintype "unspecified"))
      (node (ref "U207") (pin "16") (pinfunction "I_16") (pintype "unspecified"))
    )
    (net (code "270") (name "Z_CINH") (class "Default")
      (node (ref "C1") (pin "17") (pinfunction "/CINH,/OVR_17") (pintype "bidirectional"))
      (node (ref "U202") (pin "24") (pinfunction "IOQ_24") (pintype "unspecified"))
    )
    (net (code "271") (name "Z_D16") (class "Default")
      (node (ref "C1") (pin "75") (pinfunction "RSVD+D16,D0_75") (pintype "unspecified"))
      (node (ref "U108") (pin "22") (pinfunction "B0_22") (pintype "bidirectional"))
    )
    (net (code "272") (name "Z_D17") (class "Default")
      (node (ref "C1") (pin "77") (pinfunction "RSVD+D17,D1_77") (pintype "unspecified"))
      (node (ref "U108") (pin "21") (pinfunction "B1_21") (pintype "bidirectional"))
    )
    (net (code "273") (name "Z_D18") (class "Default")
      (node (ref "C1") (pin "79") (pinfunction "RSVD+D18,D2_79") (pintype "output"))
      (node (ref "U108") (pin "20") (pinfunction "B2_20") (pintype "bidirectional"))
    )
    (net (code "274") (name "Z_D19") (class "Default")
      (node (ref "C1") (pin "81") (pinfunction "RSVD+D19,D3_81") (pintype "unspecified"))
      (node (ref "U108") (pin "19") (pinfunction "B3_19") (pintype "bidirectional"))
    )
    (net (code "275") (name "Z_D20") (class "Default")
      (node (ref "C1") (pin "83") (pinfunction "RSVD+D20,D4_83") (pintype "output"))
      (node (ref "U108") (pin "18") (pinfunction "B4_18") (pintype "bidirectional"))
    )
    (net (code "276") (name "Z_D21") (class "Default")
      (node (ref "C1") (pin "86") (pinfunction "RSVD+D21,D5_86") (pintype "bidirectional"))
      (node (ref "U108") (pin "17") (pinfunction "B5_17") (pintype "bidirectional"))
    )
    (net (code "277") (name "Z_D22") (class "Default")
      (node (ref "C1") (pin "84") (pinfunction "RSVD+D22,D6_84") (pintype "output"))
      (node (ref "U108") (pin "16") (pinfunction "B6_16") (pintype "bidirectional"))
    )
    (net (code "278") (name "Z_D23") (class "Default")
      (node (ref "C1") (pin "82") (pinfunction "RSVD+D23,D7_82") (pintype "bidirectional"))
      (node (ref "U108") (pin "15") (pinfunction "B7_15") (pintype "bidirectional"))
    )
    (net (code "279") (name "Z_DOE") (class "Default")
      (node (ref "C1") (pin "93") (pinfunction "DOE_93") (pintype "unspecified"))
      (node (ref "U109") (pin "16") (pinfunction "B2_16") (pintype "unspecified"))
    )
    (net (code "280") (name "Z_DS0") (class "Default")
      (node (ref "C1") (pin "51") (pinfunction "/DS0,/VMA_51") (pintype "unspecified"))
      (node (ref "U109") (pin "11") (pinfunction "B7_11") (pintype "unspecified"))
    )
    (net (code "281") (name "Z_DS1") (class "Default")
      (node (ref "C1") (pin "98") (pinfunction "/DS1,NC_98") (pintype "bidirectional"))
      (node (ref "U109") (pin "12") (pinfunction "B6_12") (pintype "unspecified"))
    )
    (net (code "282") (name "Z_DS2") (class "Default")
      (node (ref "C1") (pin "70") (pinfunction "/DS2,/LDS_70") (pintype "unspecified"))
      (node (ref "FB508") (pin "2") (pinfunction "2_2") (pintype "unspecified"))
    )
    (net (code "283") (name "Z_DS3") (class "Default")
      (node (ref "C1") (pin "72") (pinfunction "/DS3,/UDS_72") (pintype "unspecified"))
      (node (ref "FB507") (pin "2") (pinfunction "2_2") (pintype "unspecified"))
    )
    (net (code "284") (name "Z_DTACK") (class "Default")
      (node (ref "C1") (pin "66") (pinfunction "/DTACK_66") (pintype "unspecified"))
      (node (ref "U205") (pin "20") (pinfunction "IOQ_20") (pintype "unspecified"))
      (node (ref "U306") (pin "9") (pinfunction "I_9") (pintype "unspecified"))
    )
    (net (code "285") (name "Z_FC0") (class "Default")
      (node (ref "C1") (pin "31") (pinfunction "FC0_31") (pintype "unspecified"))
      (node (ref "U109") (pin "17") (pinfunction "B1_17") (pintype "unspecified"))
    )
    (net (code "286") (name "Z_FC1") (class "Default")
      (node (ref "C1") (pin "33") (pinfunction "FC1_33") (pintype "unspecified"))
      (node (ref "U109") (pin "18") (pinfunction "B0_18") (pintype "unspecified"))
    )
    (net (code "287") (name "Z_FC2") (class "Default")
      (node (ref "C1") (pin "35") (pinfunction "FC2_35") (pintype "unspecified"))
      (node (ref "U103") (pin "12") (pinfunction "B6_12") (pintype "unspecified"))
    )
    (net (code "288") (name "Z_FCS") (class "Default")
      (node (ref "C1") (pin "97") (pinfunction "/FCS,NC_97") (pintype "unspecified"))
      (node (ref "FB501") (pin "2") (pinfunction "2_2") (pintype "unspecified"))
      (node (ref "U305") (pin "21") (pinfunction "IOQ_21") (pintype "unspecified"))
    )
    (net (code "289") (name "Z_INT2") (class "Default")
      (node (ref "C1") (pin "19") (pinfunction "/INT2_19") (pintype "bidirectional"))
      (node (ref "U207") (pin "27") (pinfunction "IOQ_27") (pintype "unspecified"))
    )
    (net (code "290") (name "Z_IORST") (class "Default")
      (node (ref "C1") (pin "94") (pinfunction "/IORST,/BUSRST_94") (pintype "bidirectional"))
      (node (ref "U307") (pin "9") (pinfunction "4A_9") (pintype "unspecified"))
    )
    (net (code "291") (name "Z_LOCK") (class "Default")
      (node (ref "C1") (pin "29") (pinfunction "/LOCK,A1_29") (pintype "unspecified"))
      (node (ref "U203") (pin "6") (pinfunction "I_6") (pintype "unspecified"))
    )
    (net (code "292") (name "Z_MTACK") (class "Default")
      (node (ref "C1") (pin "48") (pinfunction "/MTACK,/VPA_48") (pintype "bidirectional"))
      (node (ref "U306") (pin "5") (pinfunction "I_5") (pintype "unspecified"))
    )
    (net (code "293") (name "Z_MTCR") (class "Default")
      (node (ref "C1") (pin "18") (pinfunction "/MTCR,XRDY_18") (pintype "bidirectional"))
      (node (ref "U109") (pin "15") (pinfunction "B3_15") (pintype "unspecified"))
    )
    (net (code "294") (name "Z_READ") (class "Default")
      (node (ref "C1") (pin "68") (pinfunction "READ_68") (pintype "unspecified"))
      (node (ref "U103") (pin "11") (pinfunction "B7_11") (pintype "unspecified"))
    )
    (net (code "295") (name "Z_SENSEZ3") (class "Default")
      (node (ref "C1") (pin "91") (pinfunction "SenseZ3,GND_91") (pintype "output"))
      (node (ref "R100A") (pin "1") (pinfunction "1_1") (pintype "input"))
      (node (ref "U202") (pin "20") (pinfunction "IOQ_20") (pintype "unspecified"))
    )
    (net (code "296") (name "Z_SLAVE") (class "Default")
      (node (ref "C1") (pin "09") (pinfunction "/SLAVEn_09") (pintype "bidirectional"))
      (node (ref "U202") (pin "26") (pinfunction "IOQ_26") (pintype "unspecified"))
      (node (ref "U203") (pin "20") (pinfunction "IOQ_20") (pintype "unspecified"))
      (node (ref "U205") (pin "3") (pinfunction "I_3") (pintype "unspecified"))
      (node (ref "U207") (pin "13") (pinfunction "I_13") (pintype "unspecified"))
      (node (ref "U303") (pin "7") (pinfunction "I_7") (pintype "unspecified"))
    )
    (net (code "297") (name "unconnected-(C1--5V-Pad08)") (class "Default")
      (node (ref "C1") (pin "08") (pinfunction "-5V_08") (pintype "bidirectional+no_connect"))
    )
    (net (code "298") (name "unconnected-(C1--12V-Pad20)") (class "Default")
      (node (ref "C1") (pin "20") (pinfunction "-12V_20") (pintype "unspecified+no_connect"))
    )
    (net (code "299") (name "unconnected-(C1-CDAC_Clock-Pad15)") (class "Default")
      (node (ref "C1") (pin "15") (pinfunction "CDAC_Clock_15") (pintype "unspecified+no_connect"))
    )
    (net (code "300") (name "unconnected-(C1-E_Clock-Pad50)") (class "Default")
      (node (ref "C1") (pin "50") (pinfunction "E_Clock_50") (pintype "bidirectional+no_connect"))
    )
    (net (code "301") (name "unconnected-(C1-RSVD,{slash}EINT1-Pad96)") (class "Default")
      (node (ref "C1") (pin "96") (pinfunction "RSVD,/EINT1_96") (pintype "bidirectional+no_connect"))
    )
    (net (code "302") (name "unconnected-(C1-RSVD,{slash}EINT4-Pad44)") (class "Default")
      (node (ref "C1") (pin "44") (pinfunction "RSVD,/EINT4_44") (pintype "bidirectional+no_connect"))
    )
    (net (code "303") (name "unconnected-(C1-RSVD,{slash}EINT5-Pad42)") (class "Default")
      (node (ref "C1") (pin "42") (pinfunction "RSVD,/EINT5_42") (pintype "bidirectional+no_connect"))
    )
    (net (code "304") (name "unconnected-(C1-RSVD,{slash}EINT7-Pad40)") (class "Default")
      (node (ref "C1") (pin "40") (pinfunction "RSVD,/EINT7_40") (pintype "bidirectional+no_connect"))
    )
    (net (code "305") (name "unconnected-(C1-{slash}BCLR,{slash}GBG-Pad95)") (class "Default")
      (node (ref "C1") (pin "95") (pinfunction "/BCLR,/GBG_95") (pintype "bidirectional+no_connect"))
    )
    (net (code "306") (name "unconnected-(C1-{slash}BGACK-Pad62)") (class "Default")
      (node (ref "C1") (pin "62") (pinfunction "/BGACK_62") (pintype "bidirectional+no_connect"))
    )
    (net (code "307") (name "unconnected-(C1-{slash}C1_Clock-Pad16)") (class "Default")
      (node (ref "C1") (pin "16") (pinfunction "/C1_Clock_16") (pintype "bidirectional+no_connect"))
    )
    (net (code "308") (name "unconnected-(C1-{slash}C3_Clock-Pad14)") (class "Default")
      (node (ref "C1") (pin "14") (pinfunction "/C3_Clock_14") (pintype "bidirectional+no_connect"))
    )
    (net (code "309") (name "unconnected-(C1-{slash}CCS,{slash}AS-Pad74)") (class "Default")
      (node (ref "C1") (pin "74") (pinfunction "/CCS,/AS_74") (pintype "unspecified+no_connect"))
    )
    (net (code "310") (name "unconnected-(C1-{slash}HLT-Pad55)") (class "Default")
      (node (ref "C1") (pin "55") (pinfunction "/HLT_55") (pintype "output+no_connect"))
    )
    (net (code "311") (name "unconnected-(C1-{slash}INT6-Pad22)") (class "Default")
      (node (ref "C1") (pin "22") (pinfunction "/INT6_22") (pintype "output+no_connect"))
    )
    (net (code "312") (name "unconnected-(C1-{slash}OWN-Pad07)") (class "Default")
      (node (ref "C1") (pin "07") (pinfunction "/OWN_07") (pintype "unspecified+no_connect"))
    )
    (net (code "313") (name "unconnected-(C1-{slash}RST-Pad53)") (class "Default")
      (node (ref "C1") (pin "53") (pinfunction "/RST_53") (pintype "unspecified+no_connect"))
    )
    (net (code "314") (name "unconnected-(CN309-Pad25)") (class "Default")
      (node (ref "CN309") (pin "25") (pinfunction "25_25") (pintype "input+no_connect"))
    )
    (net (code "315") (name "unconnected-(CN309-Pad34)") (class "Default")
      (node (ref "CN309") (pin "34") (pinfunction "34_34") (pintype "input+no_connect"))
    )
    (net (code "316") (name "unconnected-(CN310-Pad12)") (class "Default")
      (node (ref "CN310") (pin "12") (pinfunction "12_12") (pintype "unspecified+no_connect"))
    )
    (net (code "317") (name "unconnected-(CN310-Pad13)") (class "Default")
      (node (ref "CN310") (pin "13") (pinfunction "13_13") (pintype "unspecified+no_connect"))
    )
    (net (code "318") (name "unconnected-(CN310-Pad14)") (class "Default")
      (node (ref "CN310") (pin "14") (pinfunction "14_14") (pintype "unspecified+no_connect"))
    )
    (net (code "319") (name "unconnected-(CN310-Pad37)") (class "Default")
      (node (ref "CN310") (pin "37") (pinfunction "37_37") (pintype "unspecified+no_connect"))
    )
    (net (code "320") (name "unconnected-(CN310-Pad39)") (class "Default")
      (node (ref "CN310") (pin "39") (pinfunction "39_39") (pintype "unspecified+no_connect"))
    )
    (net (code "321") (name "unconnected-(CN400-Pad25)") (class "Default")
      (node (ref "CN400") (pin "25") (pinfunction "25_25") (pintype "unspecified+no_connect"))
    )
    (net (code "322") (name "unconnected-(U202-IOQ-Pad25)") (class "Default")
      (node (ref "U202") (pin "25") (pinfunction "IOQ_25") (pintype "unspecified+no_connect"))
    )
    (net (code "323") (name "unconnected-(U202-NC-Pad1)") (class "Default")
      (node (ref "U202") (pin "1") (pinfunction "NC_1") (pintype "unspecified+no_connect"))
    )
    (net (code "324") (name "unconnected-(U202-NC-Pad8)") (class "Default")
      (node (ref "U202") (pin "8") (pinfunction "NC_8") (pintype "unspecified+no_connect"))
    )
    (net (code "325") (name "unconnected-(U202-NC-Pad15)") (class "Default")
      (node (ref "U202") (pin "15") (pinfunction "NC_15") (pintype "unspecified+no_connect"))
    )
    (net (code "326") (name "unconnected-(U202-NC-Pad22)") (class "Default")
      (node (ref "U202") (pin "22") (pinfunction "NC_22") (pintype "unspecified+no_connect"))
    )
    (net (code "327") (name "unconnected-(U203-IOQ-Pad18)") (class "Default")
      (node (ref "U203") (pin "18") (pinfunction "IOQ_18") (pintype "unspecified+no_connect"))
    )
    (net (code "328") (name "unconnected-(U203-IOQ-Pad19)") (class "Default")
      (node (ref "U203") (pin "19") (pinfunction "IOQ_19") (pintype "unspecified+no_connect"))
    )
    (net (code "329") (name "unconnected-(U203-IOQ-Pad21)") (class "Default")
      (node (ref "U203") (pin "21") (pinfunction "IOQ_21") (pintype "unspecified+no_connect"))
    )
    (net (code "330") (name "unconnected-(U203-NC-Pad1)") (class "Default")
      (node (ref "U203") (pin "1") (pinfunction "NC_1") (pintype "unspecified+no_connect"))
    )
    (net (code "331") (name "unconnected-(U203-NC-Pad8)") (class "Default")
      (node (ref "U203") (pin "8") (pinfunction "NC_8") (pintype "unspecified+no_connect"))
    )
    (net (code "332") (name "unconnected-(U203-NC-Pad15)") (class "Default")
      (node (ref "U203") (pin "15") (pinfunction "NC_15") (pintype "unspecified+no_connect"))
    )
    (net (code "333") (name "unconnected-(U203-NC-Pad22)") (class "Default")
      (node (ref "U203") (pin "22") (pinfunction "NC_22") (pintype "unspecified+no_connect"))
    )
    (net (code "334") (name "unconnected-(U205-NC-Pad1)") (class "Default")
      (node (ref "U205") (pin "1") (pinfunction "NC_1") (pintype "unspecified+no_connect"))
    )
    (net (code "335") (name "unconnected-(U205-NC-Pad8)") (class "Default")
      (node (ref "U205") (pin "8") (pinfunction "NC_8") (pintype "unspecified+no_connect"))
    )
    (net (code "336") (name "unconnected-(U205-NC-Pad15)") (class "Default")
      (node (ref "U205") (pin "15") (pinfunction "NC_15") (pintype "unspecified+no_connect"))
    )
    (net (code "337") (name "unconnected-(U205-NC-Pad22)") (class "Default")
      (node (ref "U205") (pin "22") (pinfunction "NC_22") (pintype "unspecified+no_connect"))
    )
    (net (code "338") (name "unconnected-(U207-I-Pad3)") (class "Default")
      (node (ref "U207") (pin "3") (pinfunction "I_3") (pintype "unspecified+no_connect"))
    )
    (net (code "339") (name "unconnected-(U207-I-Pad4)") (class "Default")
      (node (ref "U207") (pin "4") (pinfunction "I_4") (pintype "unspecified+no_connect"))
    )
    (net (code "340") (name "unconnected-(U207-I-Pad5)") (class "Default")
      (node (ref "U207") (pin "5") (pinfunction "I_5") (pintype "unspecified+no_connect"))
    )
    (net (code "341") (name "unconnected-(U207-IOQ-Pad17)") (class "Default")
      (node (ref "U207") (pin "17") (pinfunction "IOQ_17") (pintype "unspecified+no_connect"))
    )
    (net (code "342") (name "unconnected-(U207-IOQ-Pad18)") (class "Default")
      (node (ref "U207") (pin "18") (pinfunction "IOQ_18") (pintype "unspecified+no_connect"))
    )
    (net (code "343") (name "unconnected-(U207-IOQ-Pad20)") (class "Default")
      (node (ref "U207") (pin "20") (pinfunction "IOQ_20") (pintype "unspecified+no_connect"))
    )
    (net (code "344") (name "unconnected-(U207-IOQ-Pad21)") (class "Default")
      (node (ref "U207") (pin "21") (pinfunction "IOQ_21") (pintype "unspecified+no_connect"))
    )
    (net (code "345") (name "unconnected-(U207-IOQ-Pad23)") (class "Default")
      (node (ref "U207") (pin "23") (pinfunction "IOQ_23") (pintype "unspecified+no_connect"))
    )
    (net (code "346") (name "unconnected-(U207-IOQ-Pad25)") (class "Default")
      (node (ref "U207") (pin "25") (pinfunction "IOQ_25") (pintype "unspecified+no_connect"))
    )
    (net (code "347") (name "unconnected-(U207-NC-Pad1)") (class "Default")
      (node (ref "U207") (pin "1") (pinfunction "NC_1") (pintype "unspecified+no_connect"))
    )
    (net (code "348") (name "unconnected-(U207-NC-Pad8)") (class "Default")
      (node (ref "U207") (pin "8") (pinfunction "NC_8") (pintype "unspecified+no_connect"))
    )
    (net (code "349") (name "unconnected-(U207-NC-Pad15)") (class "Default")
      (node (ref "U207") (pin "15") (pinfunction "NC_15") (pintype "unspecified+no_connect"))
    )
    (net (code "350") (name "unconnected-(U207-NC-Pad22)") (class "Default")
      (node (ref "U207") (pin "22") (pinfunction "NC_22") (pintype "unspecified+no_connect"))
    )
    (net (code "351") (name "unconnected-(U300-BSYDIR-Pad108)") (class "Default")
      (node (ref "U300") (pin "108") (pinfunction "BSYDIR_108") (pintype "unspecified+no_connect"))
    )
    (net (code "352") (name "unconnected-(U300-FETCH{slash}-Pad97)") (class "Default")
      (node (ref "U300") (pin "97") (pinfunction "FETCH/_97") (pintype "unspecified+no_connect"))
    )
    (net (code "353") (name "unconnected-(U300-IGS-Pad104)") (class "Default")
      (node (ref "U300") (pin "104") (pinfunction "IGS_104") (pintype "unspecified+no_connect"))
    )
    (net (code "354") (name "unconnected-(U300-RSTDIR-Pad107)") (class "Default")
      (node (ref "U300") (pin "107") (pinfunction "RSTDIR_107") (pintype "unspecified+no_connect"))
    )
    (net (code "355") (name "unconnected-(U300-SC0-Pad88)") (class "Default")
      (node (ref "U300") (pin "88") (pinfunction "SC0_88") (pintype "unspecified+no_connect"))
    )
    (net (code "356") (name "unconnected-(U300-SC1-Pad89)") (class "Default")
      (node (ref "U300") (pin "89") (pinfunction "SC1_89") (pintype "unspecified+no_connect"))
    )
    (net (code "357") (name "unconnected-(U300-SDIR0-Pad142)") (class "Default")
      (node (ref "U300") (pin "142") (pinfunction "SDIR0_142") (pintype "unspecified+no_connect"))
    )
    (net (code "358") (name "unconnected-(U300-SDIR1-Pad141)") (class "Default")
      (node (ref "U300") (pin "141") (pinfunction "SDIR1_141") (pintype "unspecified+no_connect"))
    )
    (net (code "359") (name "unconnected-(U300-SDIR2-Pad140)") (class "Default")
      (node (ref "U300") (pin "140") (pinfunction "SDIR2_140") (pintype "unspecified+no_connect"))
    )
    (net (code "360") (name "unconnected-(U300-SDIR3-Pad138)") (class "Default")
      (node (ref "U300") (pin "138") (pinfunction "SDIR3_138") (pintype "unspecified+no_connect"))
    )
    (net (code "361") (name "unconnected-(U300-SDIR4-Pad137)") (class "Default")
      (node (ref "U300") (pin "137") (pinfunction "SDIR4_137") (pintype "unspecified+no_connect"))
    )
    (net (code "362") (name "unconnected-(U300-SDIR5-Pad135)") (class "Default")
      (node (ref "U300") (pin "135") (pinfunction "SDIR5_135") (pintype "unspecified+no_connect"))
    )
    (net (code "363") (name "unconnected-(U300-SDIR6-Pad134)") (class "Default")
      (node (ref "U300") (pin "134") (pinfunction "SDIR6_134") (pintype "unspecified+no_connect"))
    )
    (net (code "364") (name "unconnected-(U300-SDIR7-Pad133)") (class "Default")
      (node (ref "U300") (pin "133") (pinfunction "SDIR7_133") (pintype "unspecified+no_connect"))
    )
    (net (code "365") (name "unconnected-(U300-SDIRP-Pad132)") (class "Default")
      (node (ref "U300") (pin "132") (pinfunction "SDIRP_132") (pintype "unspecified+no_connect"))
    )
    (net (code "366") (name "unconnected-(U300-SELDIR-Pad106)") (class "Default")
      (node (ref "U300") (pin "106") (pinfunction "SELDIR_106") (pintype "unspecified+no_connect"))
    )
    (net (code "367") (name "unconnected-(U300-TGS-Pad103)") (class "Default")
      (node (ref "U300") (pin "103") (pinfunction "TGS_103") (pintype "unspecified+no_connect"))
    )
    (net (code "368") (name "unconnected-(U300-UPS0-TT0{slash}-Pad34)") (class "Default")
      (node (ref "U300") (pin "34") (pinfunction "UPS0-TT0/_34") (pintype "unspecified+no_connect"))
    )
    (net (code "369") (name "unconnected-(U301-N.C-Pad1)") (class "Default")
      (node (ref "U301") (pin "1") (pinfunction "N.C_1") (pintype "unspecified+no_connect"))
    )
    (net (code "370") (name "unconnected-(U302-Q1#-Pad8)") (class "Default")
      (node (ref "U302") (pin "8") (pinfunction "Q1#_8") (pintype "unspecified+no_connect"))
    )
    (net (code "371") (name "unconnected-(U302-Q1-Pad9)") (class "Default")
      (node (ref "U302") (pin "9") (pinfunction "Q1_9") (pintype "unspecified+no_connect"))
    )
    (net (code "372") (name "unconnected-(U303-I-Pad13)") (class "Default")
      (node (ref "U303") (pin "13") (pinfunction "I_13") (pintype "unspecified+no_connect"))
    )
    (net (code "373") (name "unconnected-(U303-I-Pad16)") (class "Default")
      (node (ref "U303") (pin "16") (pinfunction "I_16") (pintype "unspecified+no_connect"))
    )
    (net (code "374") (name "unconnected-(U303-IOQ-Pad17)") (class "Default")
      (node (ref "U303") (pin "17") (pinfunction "IOQ_17") (pintype "unspecified+no_connect"))
    )
    (net (code "375") (name "unconnected-(U303-IOQ-Pad18)") (class "Default")
      (node (ref "U303") (pin "18") (pinfunction "IOQ_18") (pintype "unspecified+no_connect"))
    )
    (net (code "376") (name "unconnected-(U303-IOQ-Pad19)") (class "Default")
      (node (ref "U303") (pin "19") (pinfunction "IOQ_19") (pintype "unspecified+no_connect"))
    )
    (net (code "377") (name "unconnected-(U303-IOQ-Pad23)") (class "Default")
      (node (ref "U303") (pin "23") (pinfunction "IOQ_23") (pintype "unspecified+no_connect"))
    )
    (net (code "378") (name "unconnected-(U303-IOQ-Pad24)") (class "Default")
      (node (ref "U303") (pin "24") (pinfunction "IOQ_24") (pintype "unspecified+no_connect"))
    )
    (net (code "379") (name "unconnected-(U303-IOQ-Pad26)") (class "Default")
      (node (ref "U303") (pin "26") (pinfunction "IOQ_26") (pintype "unspecified+no_connect"))
    )
    (net (code "380") (name "unconnected-(U303-NC-Pad1)") (class "Default")
      (node (ref "U303") (pin "1") (pinfunction "NC_1") (pintype "unspecified+no_connect"))
    )
    (net (code "381") (name "unconnected-(U303-NC-Pad8)") (class "Default")
      (node (ref "U303") (pin "8") (pinfunction "NC_8") (pintype "unspecified+no_connect"))
    )
    (net (code "382") (name "unconnected-(U303-NC-Pad15)") (class "Default")
      (node (ref "U303") (pin "15") (pinfunction "NC_15") (pintype "unspecified+no_connect"))
    )
    (net (code "383") (name "unconnected-(U303-NC-Pad22)") (class "Default")
      (node (ref "U303") (pin "22") (pinfunction "NC_22") (pintype "unspecified+no_connect"))
    )
    (net (code "384") (name "unconnected-(U304-I-Pad16)") (class "Default")
      (node (ref "U304") (pin "16") (pinfunction "I_16") (pintype "unspecified+no_connect"))
    )
    (net (code "385") (name "unconnected-(U304-IOQ-Pad17)") (class "Default")
      (node (ref "U304") (pin "17") (pinfunction "IOQ_17") (pintype "unspecified+no_connect"))
    )
    (net (code "386") (name "unconnected-(U304-IOQ-Pad18)") (class "Default")
      (node (ref "U304") (pin "18") (pinfunction "IOQ_18") (pintype "unspecified+no_connect"))
    )
    (net (code "387") (name "unconnected-(U304-IOQ-Pad23)") (class "Default")
      (node (ref "U304") (pin "23") (pinfunction "IOQ_23") (pintype "unspecified+no_connect"))
    )
    (net (code "388") (name "unconnected-(U304-NC-Pad1)") (class "Default")
      (node (ref "U304") (pin "1") (pinfunction "NC_1") (pintype "unspecified+no_connect"))
    )
    (net (code "389") (name "unconnected-(U304-NC-Pad8)") (class "Default")
      (node (ref "U304") (pin "8") (pinfunction "NC_8") (pintype "unspecified+no_connect"))
    )
    (net (code "390") (name "unconnected-(U304-NC-Pad15)") (class "Default")
      (node (ref "U304") (pin "15") (pinfunction "NC_15") (pintype "unspecified+no_connect"))
    )
    (net (code "391") (name "unconnected-(U304-NC-Pad22)") (class "Default")
      (node (ref "U304") (pin "22") (pinfunction "NC_22") (pintype "unspecified+no_connect"))
    )
    (net (code "392") (name "unconnected-(U305-I-Pad11)") (class "Default")
      (node (ref "U305") (pin "11") (pinfunction "I_11") (pintype "unspecified+no_connect"))
    )
    (net (code "393") (name "unconnected-(U305-I-Pad12)") (class "Default")
      (node (ref "U305") (pin "12") (pinfunction "I_12") (pintype "unspecified+no_connect"))
    )
    (net (code "394") (name "unconnected-(U305-IOQ-Pad17)") (class "Default")
      (node (ref "U305") (pin "17") (pinfunction "IOQ_17") (pintype "unspecified+no_connect"))
    )
    (net (code "395") (name "unconnected-(U305-IOQ-Pad18)") (class "Default")
      (node (ref "U305") (pin "18") (pinfunction "IOQ_18") (pintype "unspecified+no_connect"))
    )
    (net (code "396") (name "unconnected-(U305-NC-Pad1)") (class "Default")
      (node (ref "U305") (pin "1") (pinfunction "NC_1") (pintype "unspecified+no_connect"))
    )
    (net (code "397") (name "unconnected-(U305-NC-Pad8)") (class "Default")
      (node (ref "U305") (pin "8") (pinfunction "NC_8") (pintype "unspecified+no_connect"))
    )
    (net (code "398") (name "unconnected-(U305-NC-Pad15)") (class "Default")
      (node (ref "U305") (pin "15") (pinfunction "NC_15") (pintype "unspecified+no_connect"))
    )
    (net (code "399") (name "unconnected-(U305-NC-Pad22)") (class "Default")
      (node (ref "U305") (pin "22") (pinfunction "NC_22") (pintype "unspecified+no_connect"))
    )
    (net (code "400") (name "unconnected-(U306-I-Pad16)") (class "Default")
      (node (ref "U306") (pin "16") (pinfunction "I_16") (pintype "unspecified+no_connect"))
    )
    (net (code "401") (name "unconnected-(U306-IOQ-Pad18)") (class "Default")
      (node (ref "U306") (pin "18") (pinfunction "IOQ_18") (pintype "unspecified+no_connect"))
    )
    (net (code "402") (name "unconnected-(U306-IOQ-Pad24)") (class "Default")
      (node (ref "U306") (pin "24") (pinfunction "IOQ_24") (pintype "unspecified+no_connect"))
    )
    (net (code "403") (name "unconnected-(U306-IOQ-Pad26)") (class "Default")
      (node (ref "U306") (pin "26") (pinfunction "IOQ_26") (pintype "unspecified+no_connect"))
    )
    (net (code "404") (name "unconnected-(U306-NC-Pad1)") (class "Default")
      (node (ref "U306") (pin "1") (pinfunction "NC_1") (pintype "unspecified+no_connect"))
    )
    (net (code "405") (name "unconnected-(U306-NC-Pad8)") (class "Default")
      (node (ref "U306") (pin "8") (pinfunction "NC_8") (pintype "unspecified+no_connect"))
    )
    (net (code "406") (name "unconnected-(U306-NC-Pad15)") (class "Default")
      (node (ref "U306") (pin "15") (pinfunction "NC_15") (pintype "unspecified+no_connect"))
    )
    (net (code "407") (name "unconnected-(U306-NC-Pad22)") (class "Default")
      (node (ref "U306") (pin "22") (pinfunction "NC_22") (pintype "unspecified+no_connect"))
    )
    (net (code "408") (name "unconnected-(U307-5Y-Pad10)") (class "Default")
      (node (ref "U307") (pin "10") (pinfunction "5Y_10") (pintype "unspecified+no_connect"))
    )
    (net (code "409") (name "unconnected-(U307-6Y-Pad12)") (class "Default")
      (node (ref "U307") (pin "12") (pinfunction "6Y_12") (pintype "unspecified+no_connect"))
    )
    (net (code "410") (name "unconnected-(U310-NC-Pad14)") (class "Default")
      (node (ref "U310") (pin "14") (pinfunction "NC_14") (pintype "unspecified+no_connect"))
    )
    (net (code "411") (name "unconnected-(U311-NC-Pad14)") (class "Default")
      (node (ref "U311") (pin "14") (pinfunction "NC_14") (pintype "unspecified+no_connect"))
    )
    (net (code "412") (name "unconnected-(U400-NC-Pad14)") (class "Default")
      (node (ref "U400") (pin "14") (pinfunction "NC_14") (pintype "unspecified+no_connect"))
    )
    (net (code "413") (name "unconnected-(U400-PD#-Pad16)") (class "Default")
      (node (ref "U400") (pin "16") (pinfunction "PD#_16") (pintype "unspecified+no_connect"))
    )
    (net (code "414") (name "unconnected-(U401-NC-Pad14)") (class "Default")
      (node (ref "U401") (pin "14") (pinfunction "NC_14") (pintype "unspecified+no_connect"))
    )
    (net (code "415") (name "unconnected-(U401-PD#-Pad16)") (class "Default")
      (node (ref "U401") (pin "16") (pinfunction "PD#_16") (pintype "unspecified+no_connect"))
    )
  )
)
